# SCH__Atlas_2026-06-27.net
KiCad netlist of a schematic drawn in EasyEDA
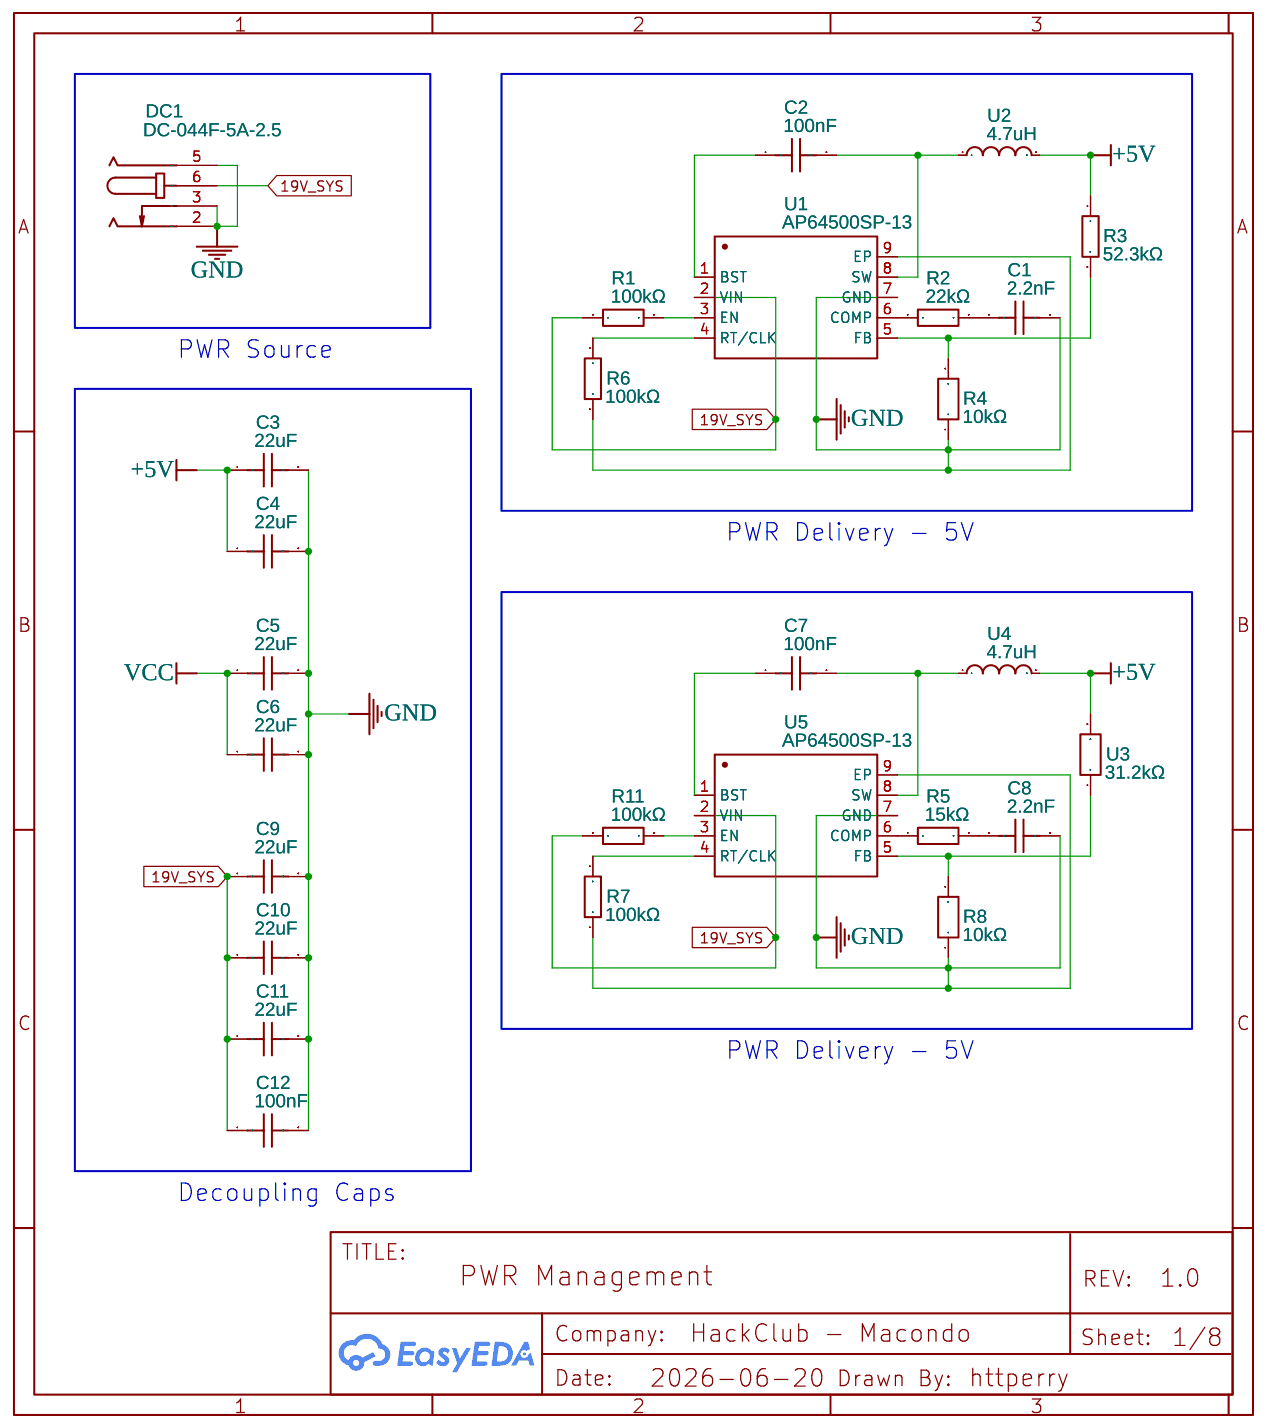
[diagram p0: PWR_Management]
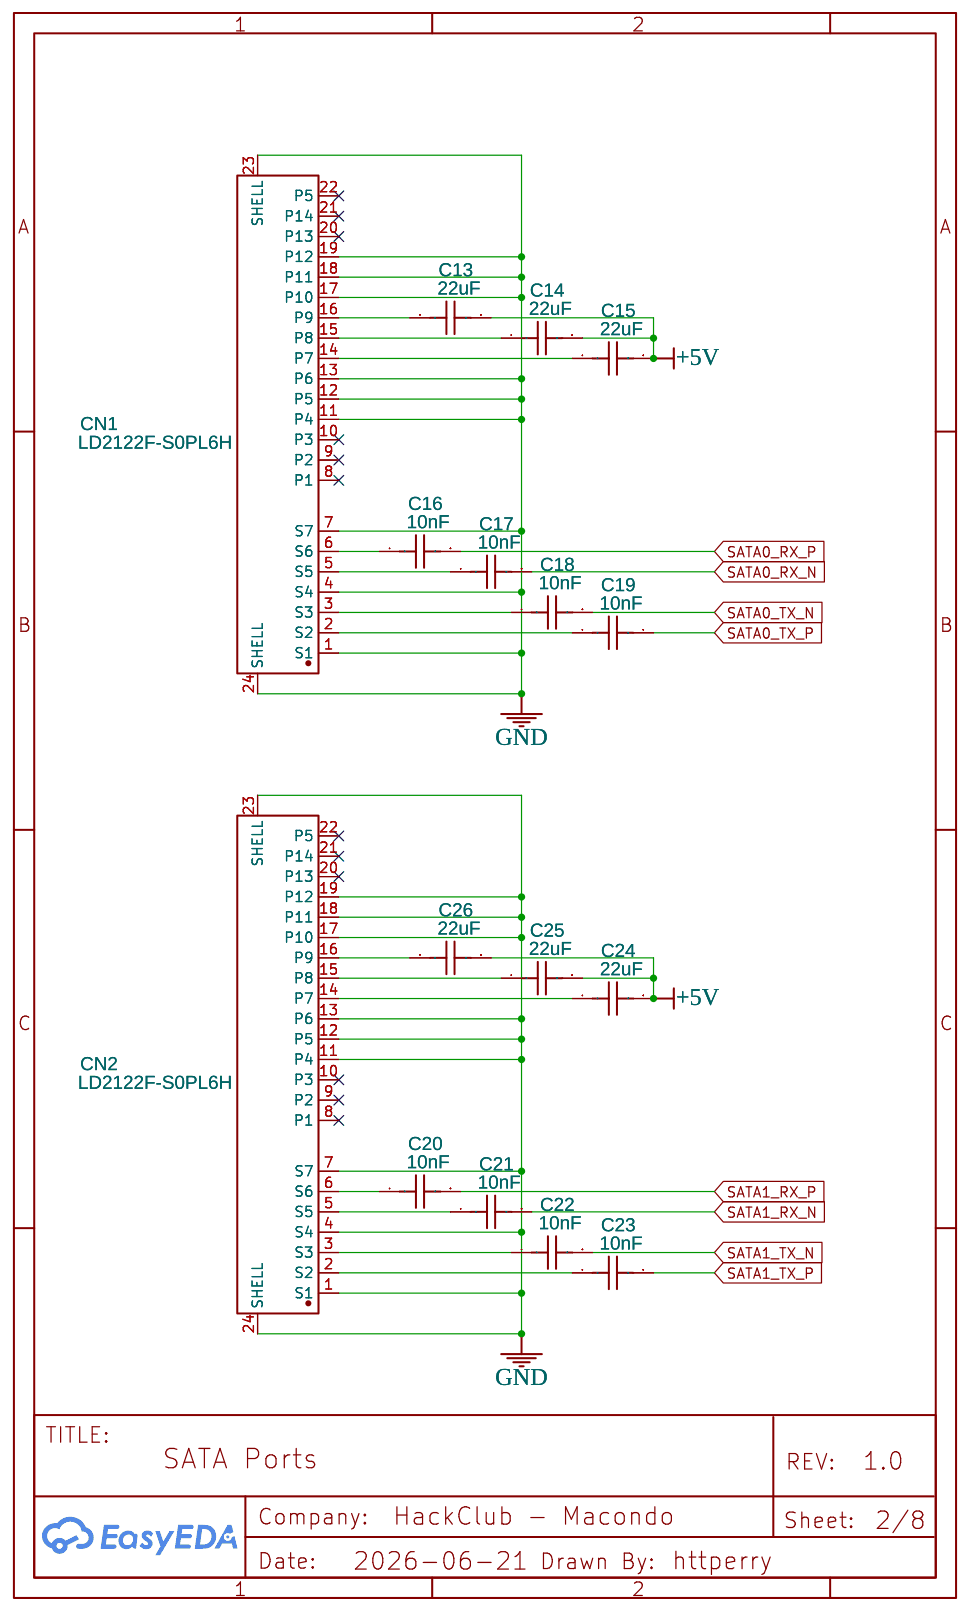
[diagram p1: SATA_Ports]
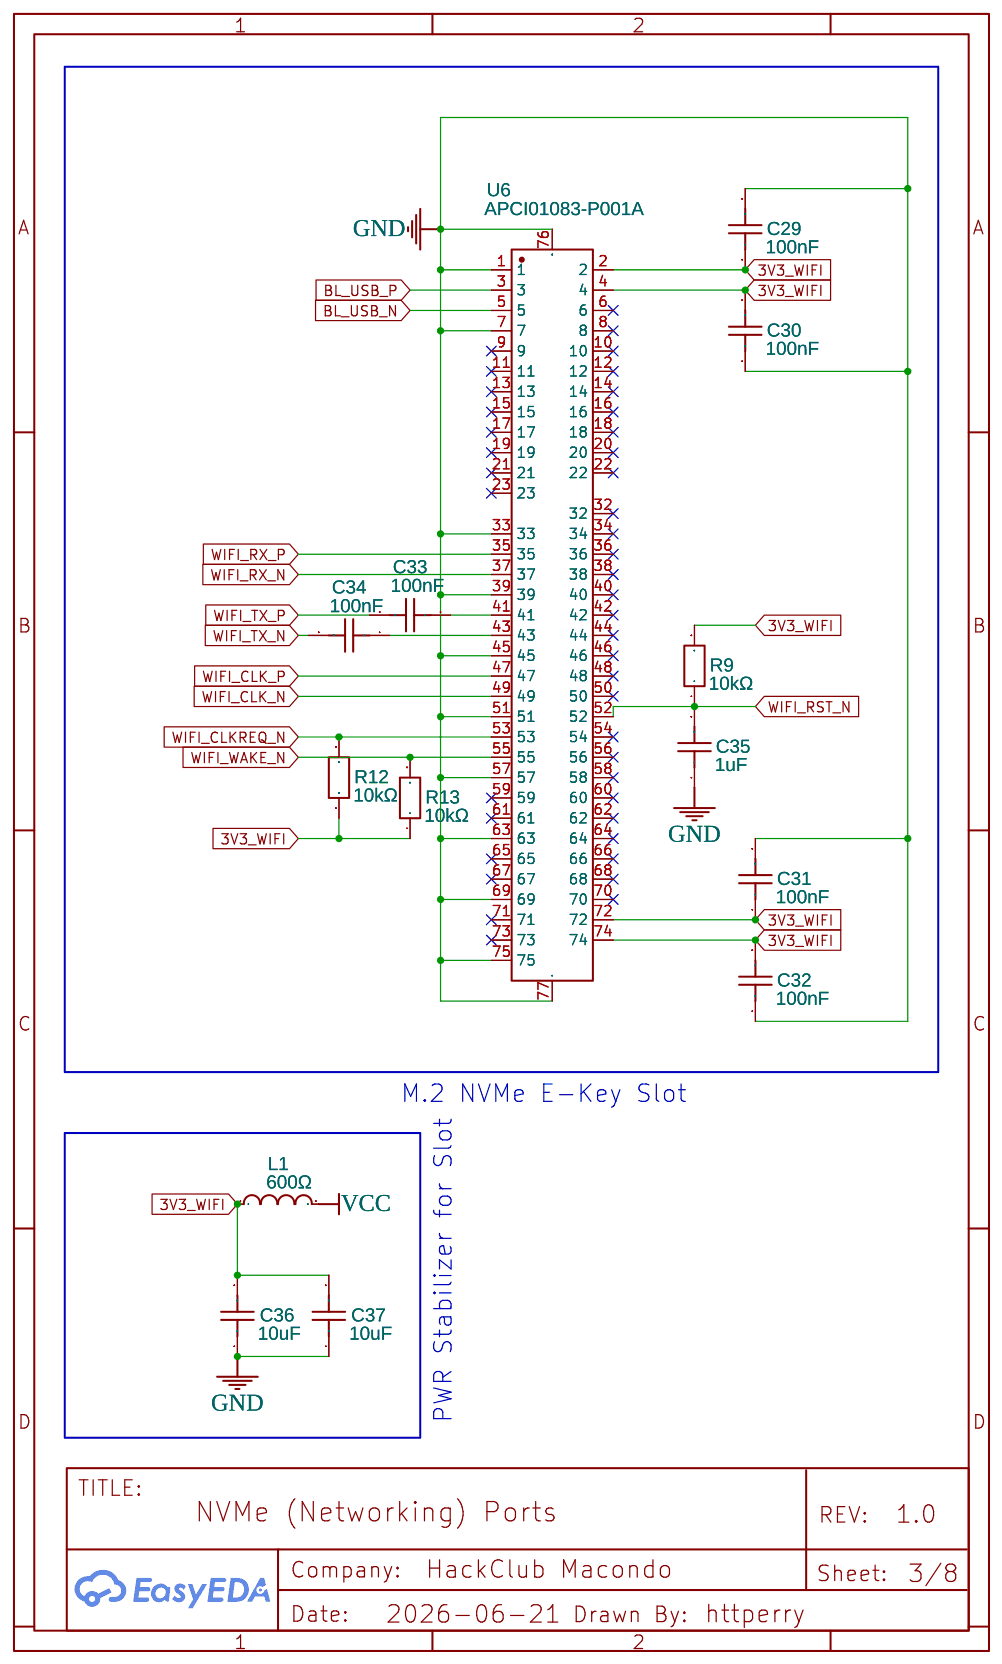
[diagram p2: NVMe_(Networking)_Ports]
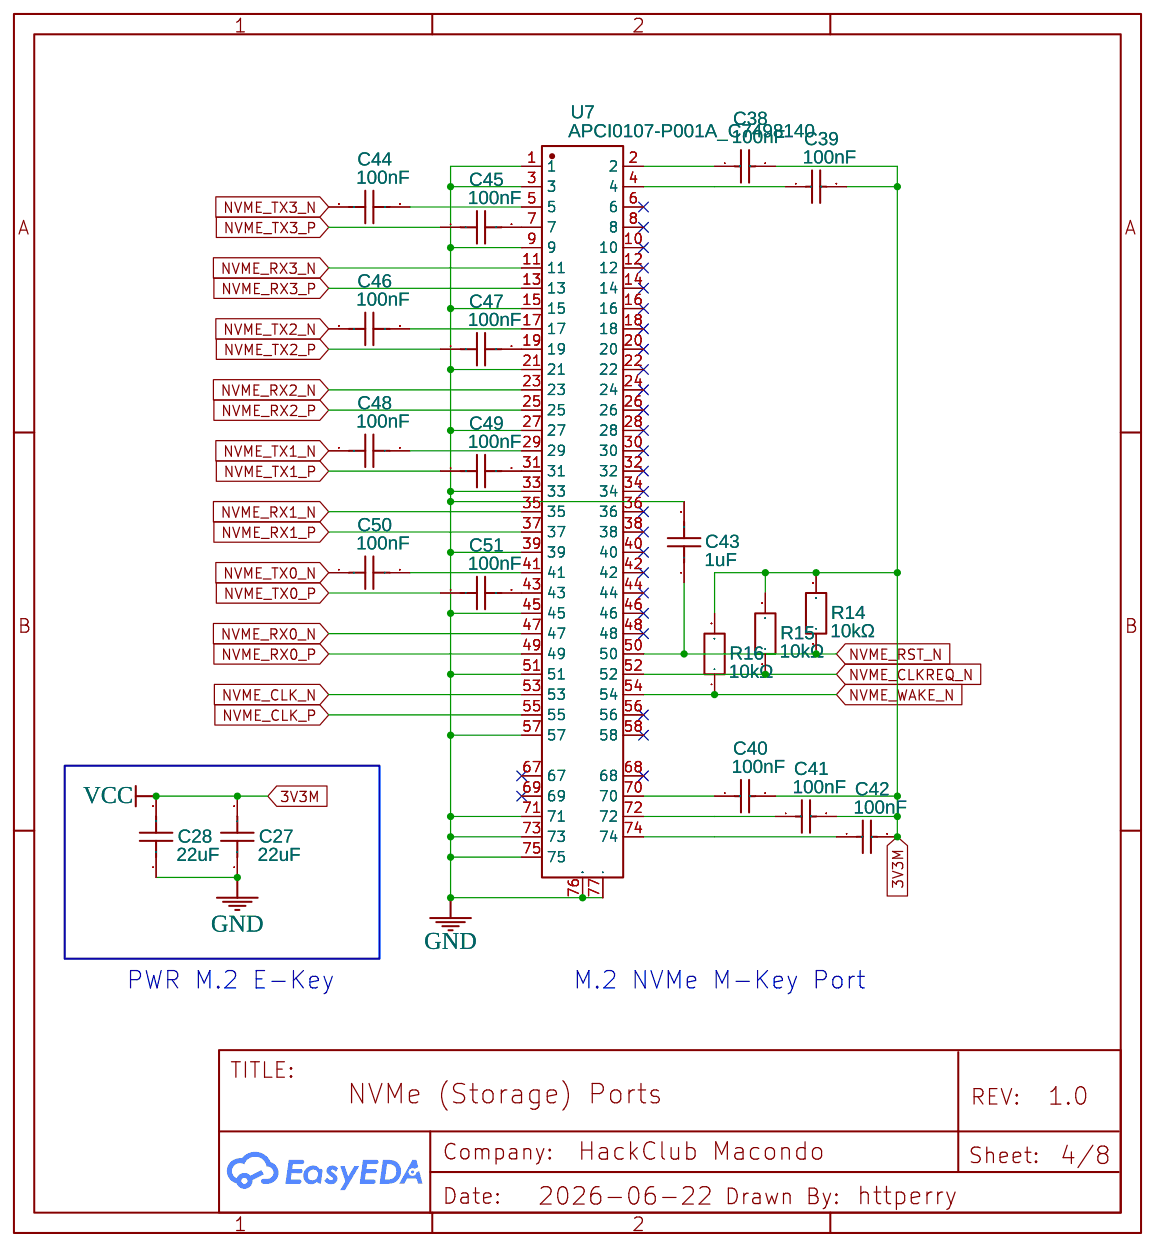
[diagram p3: NVMe_(Storage)_Ports]
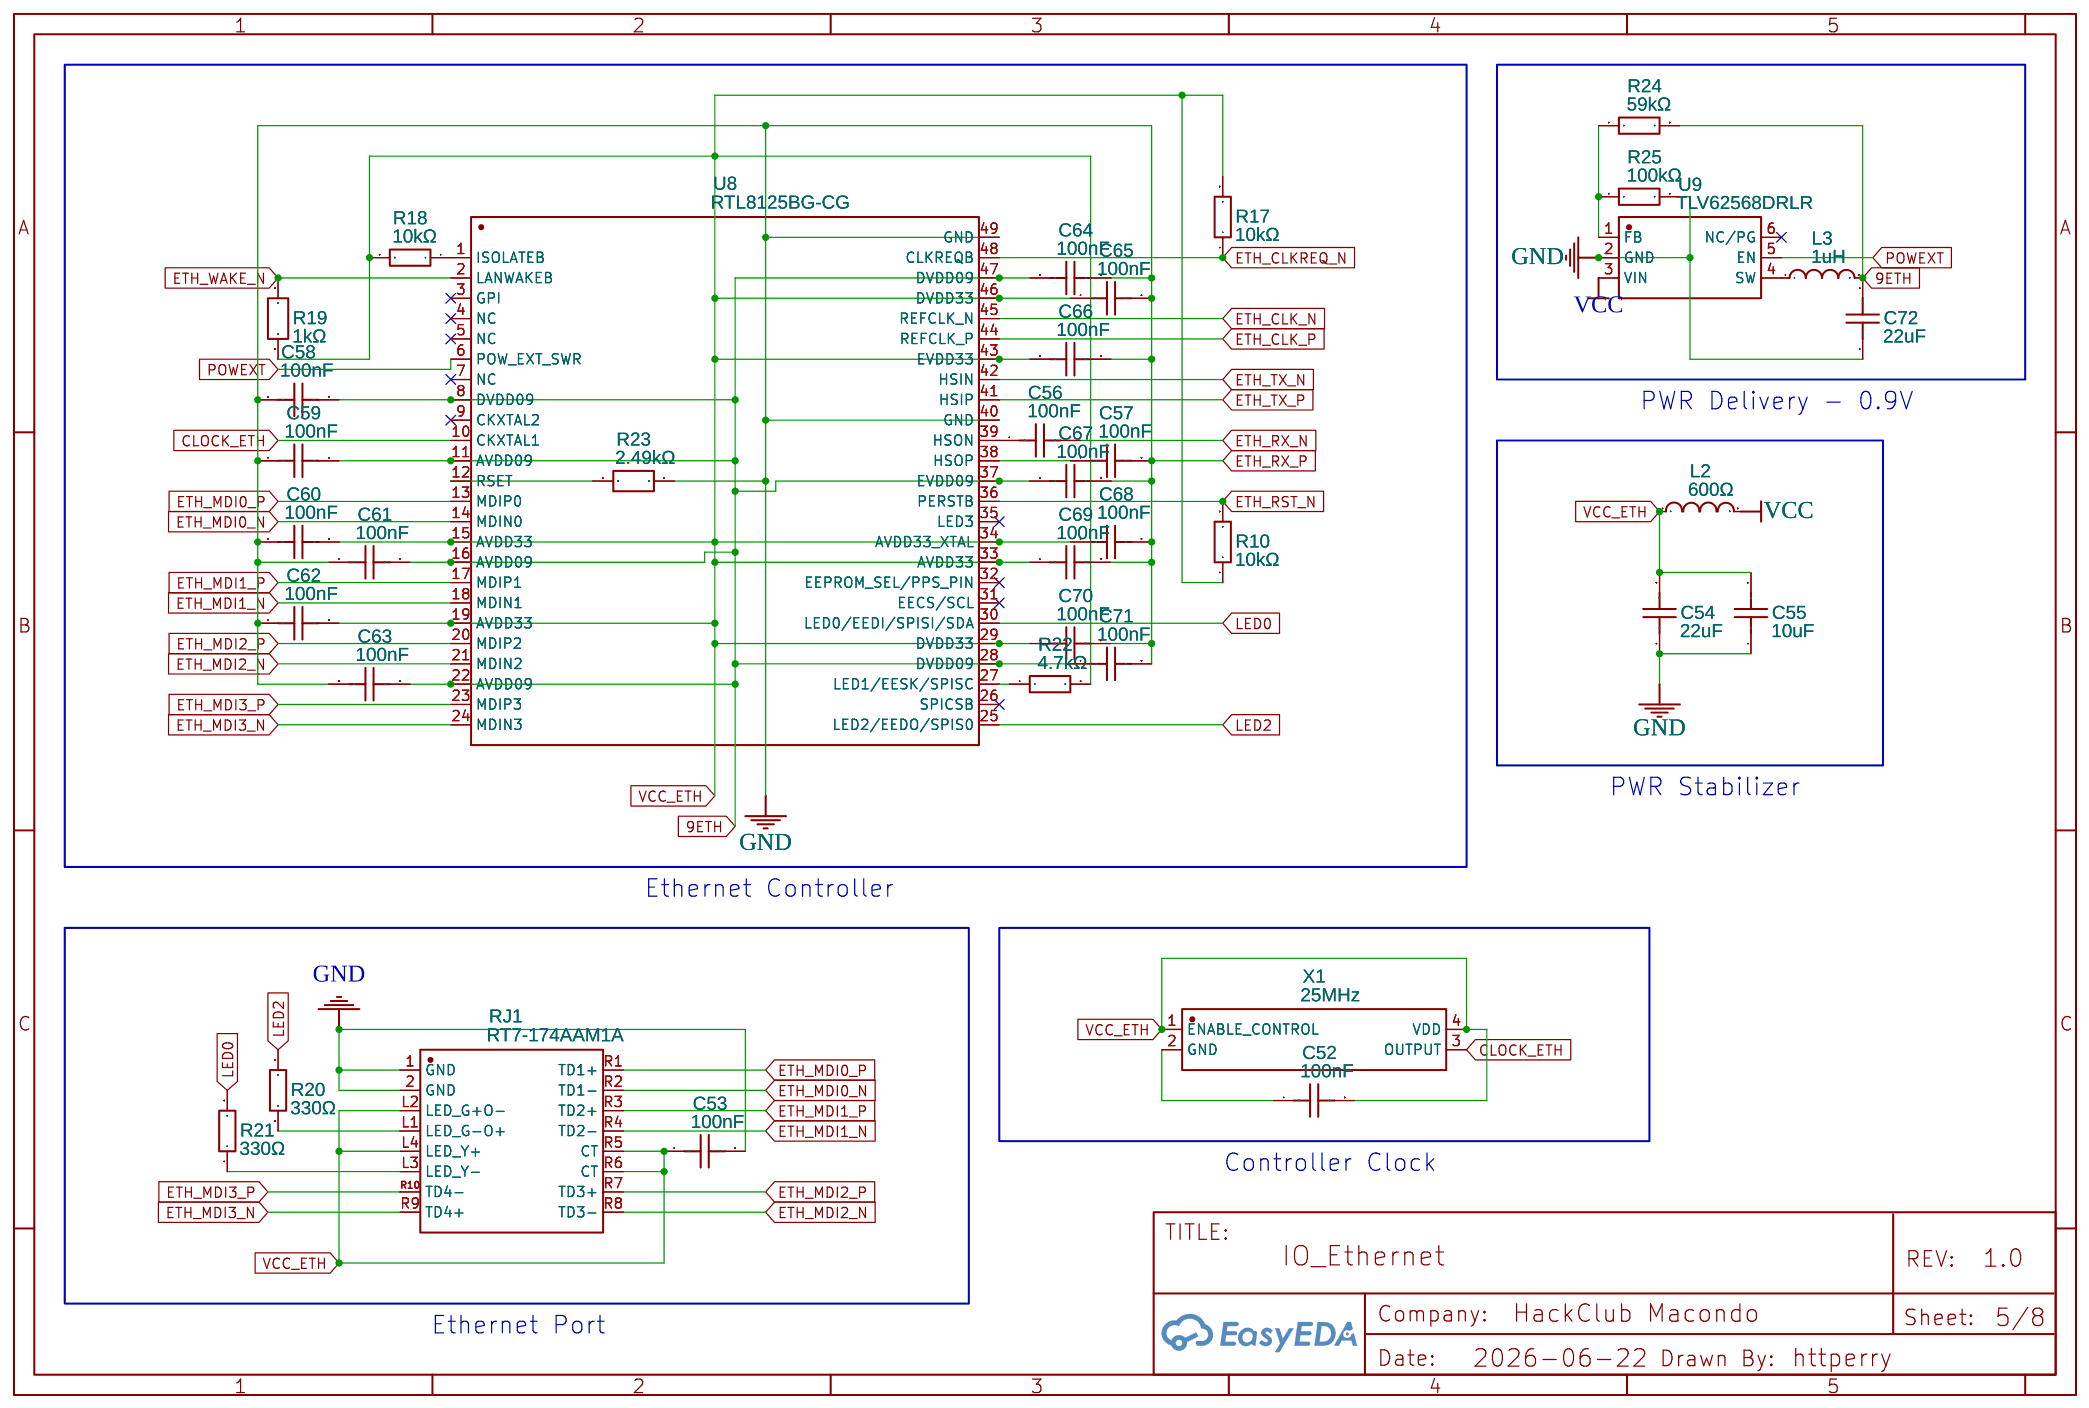
[diagram p4: IO_Ethernet]
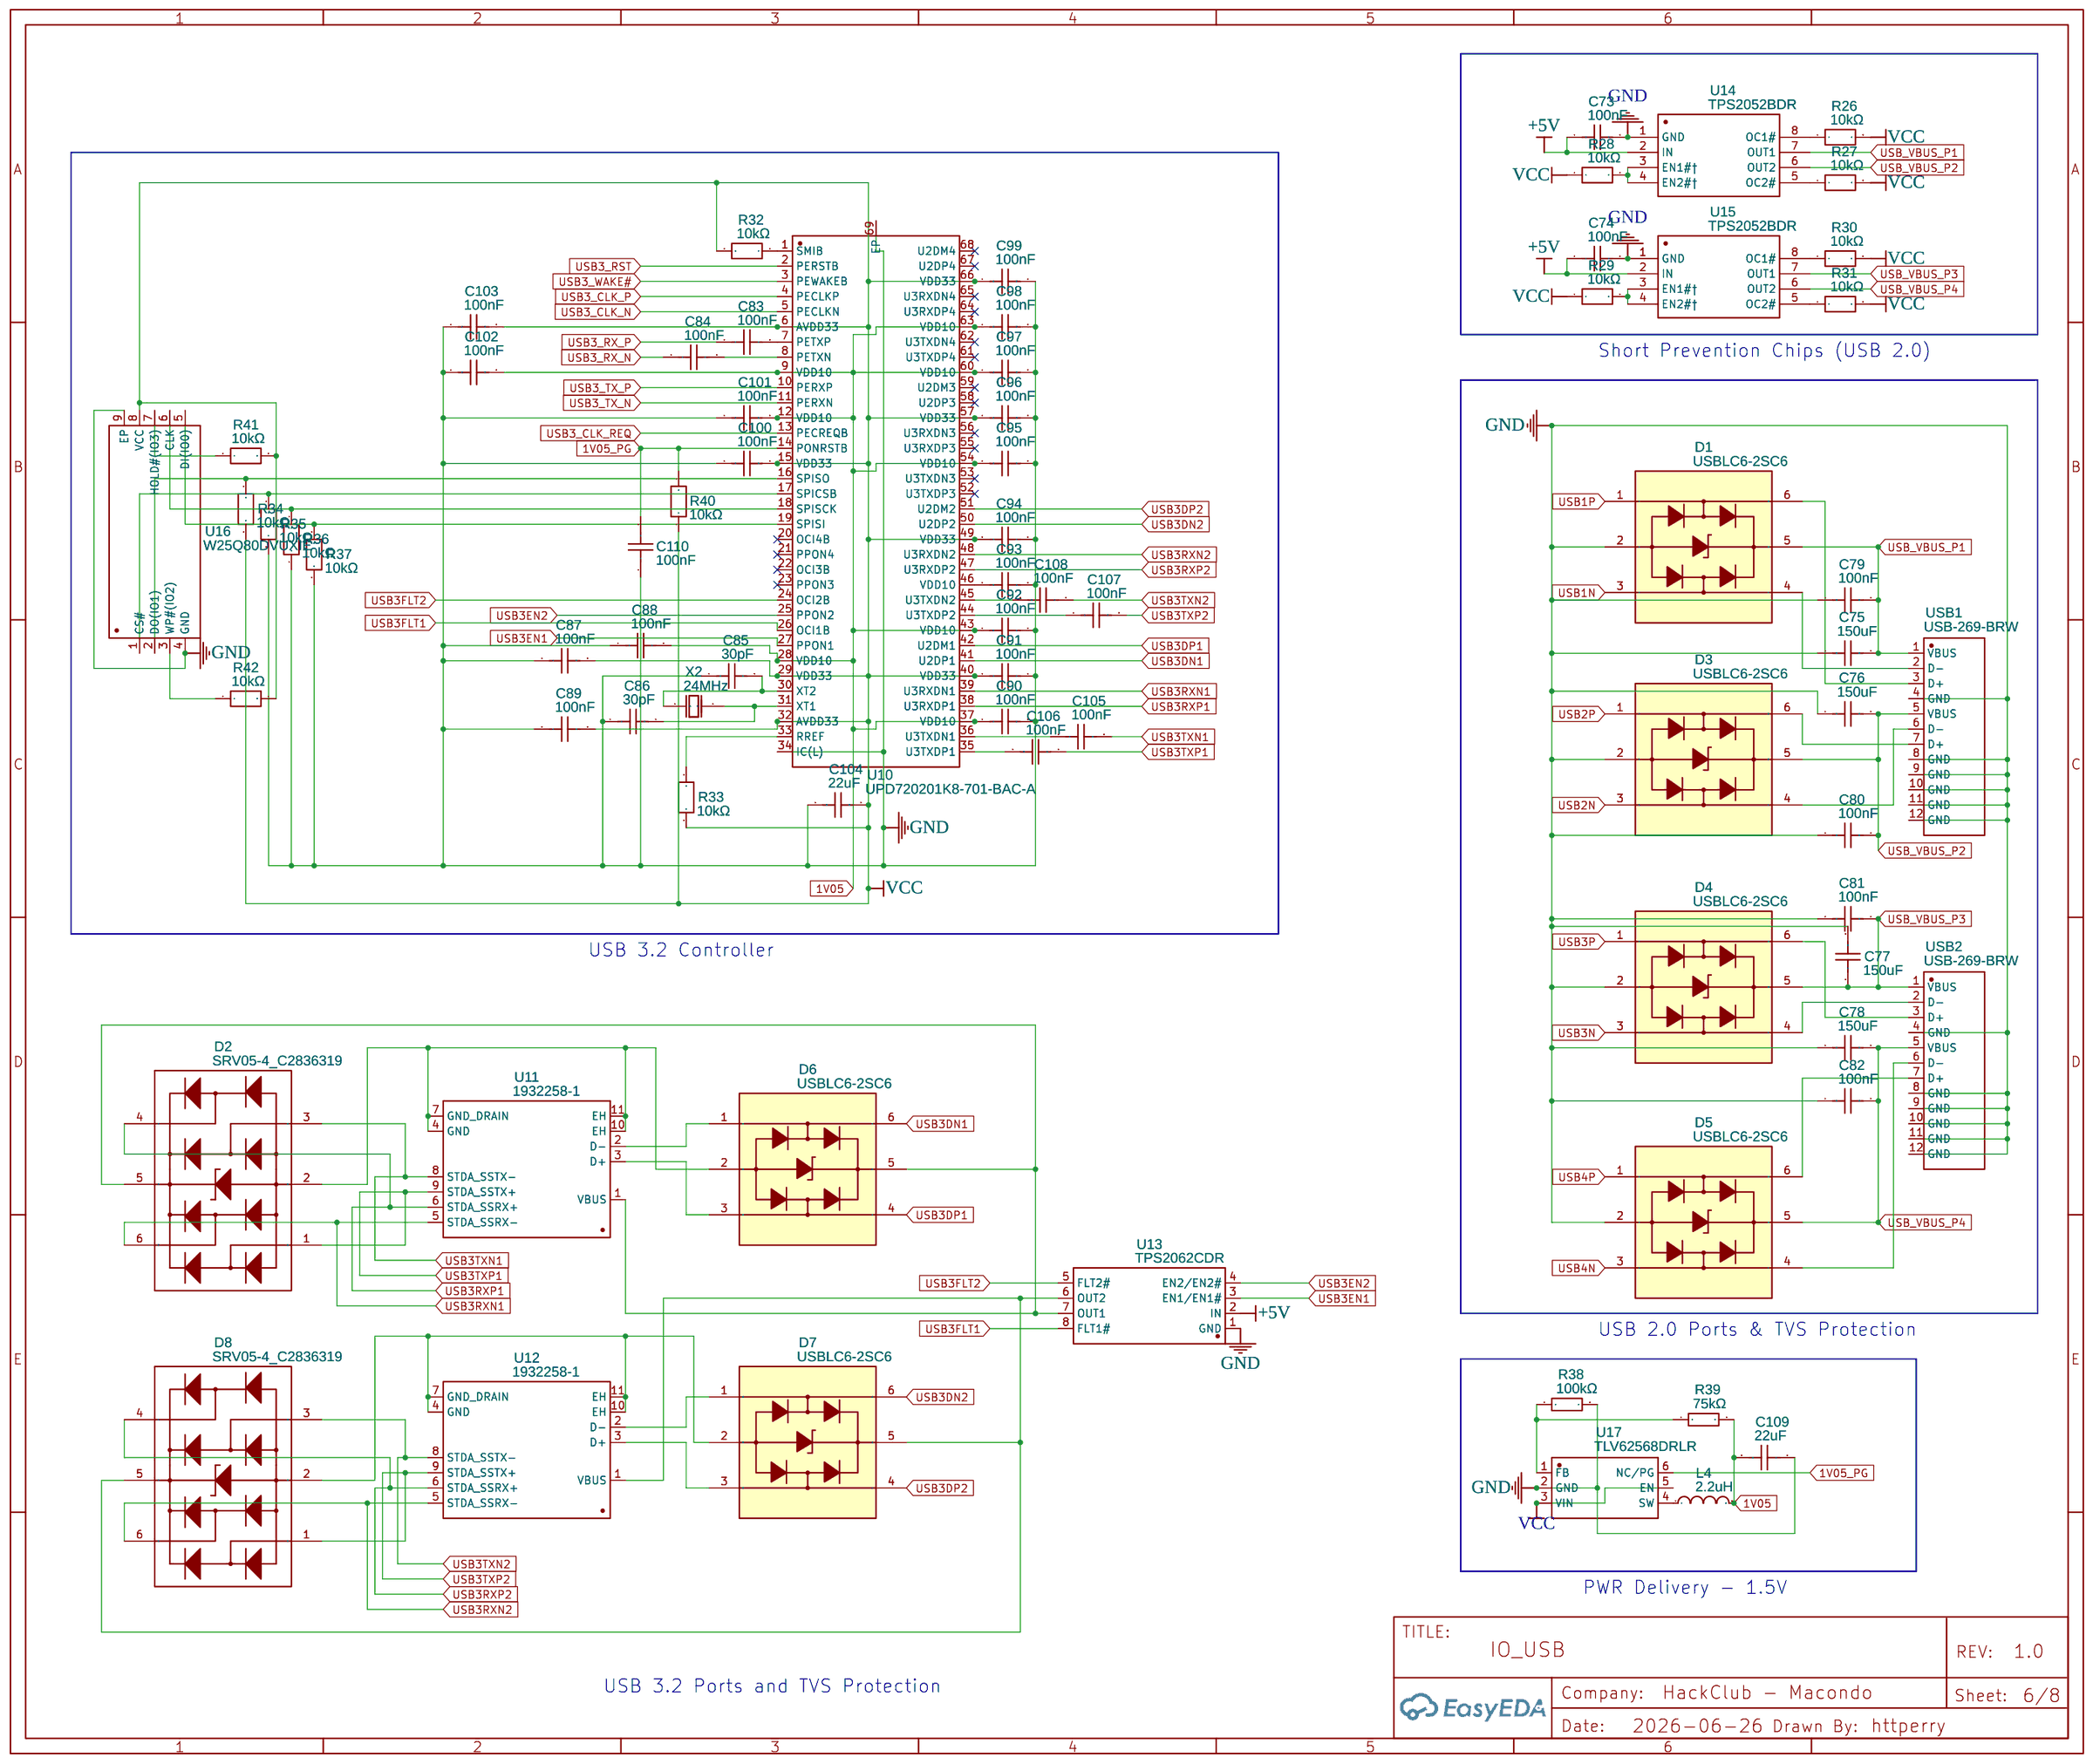
[diagram p5: IO_USB]
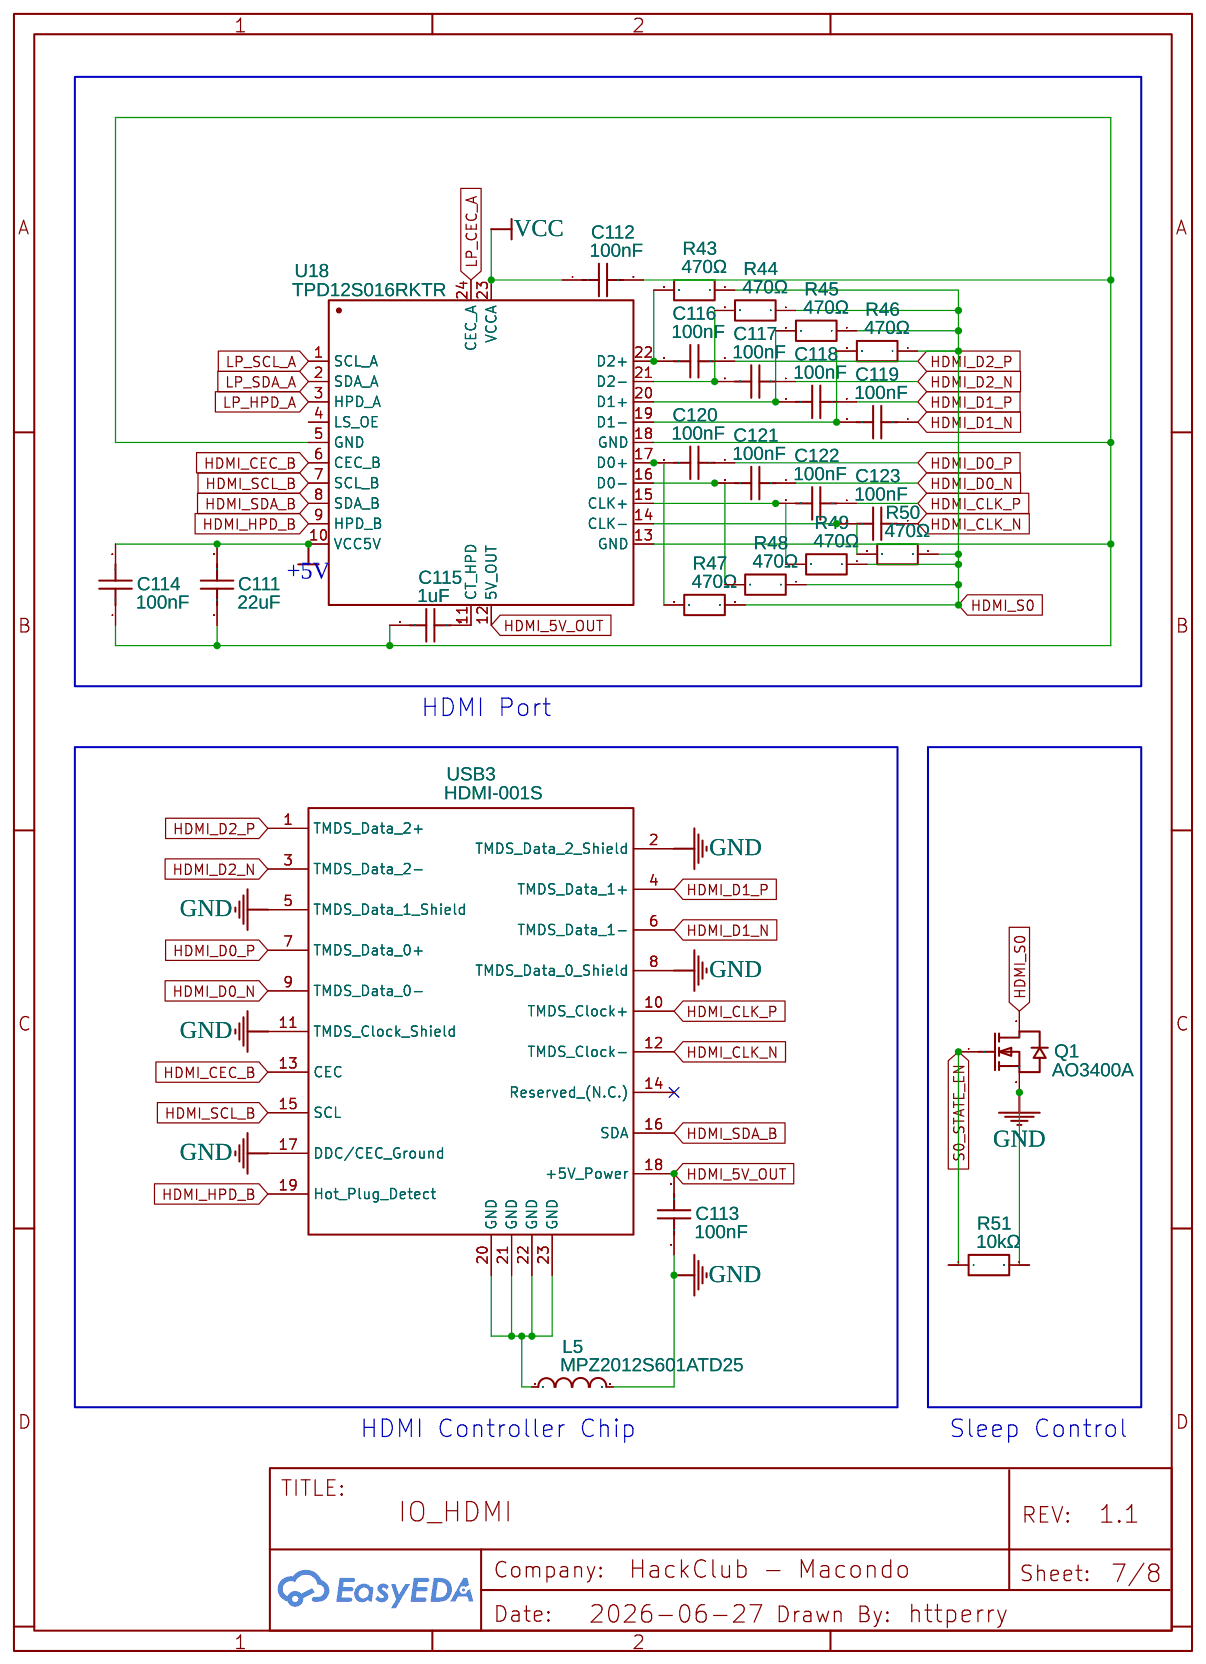
[diagram p6: IO_HDMI]
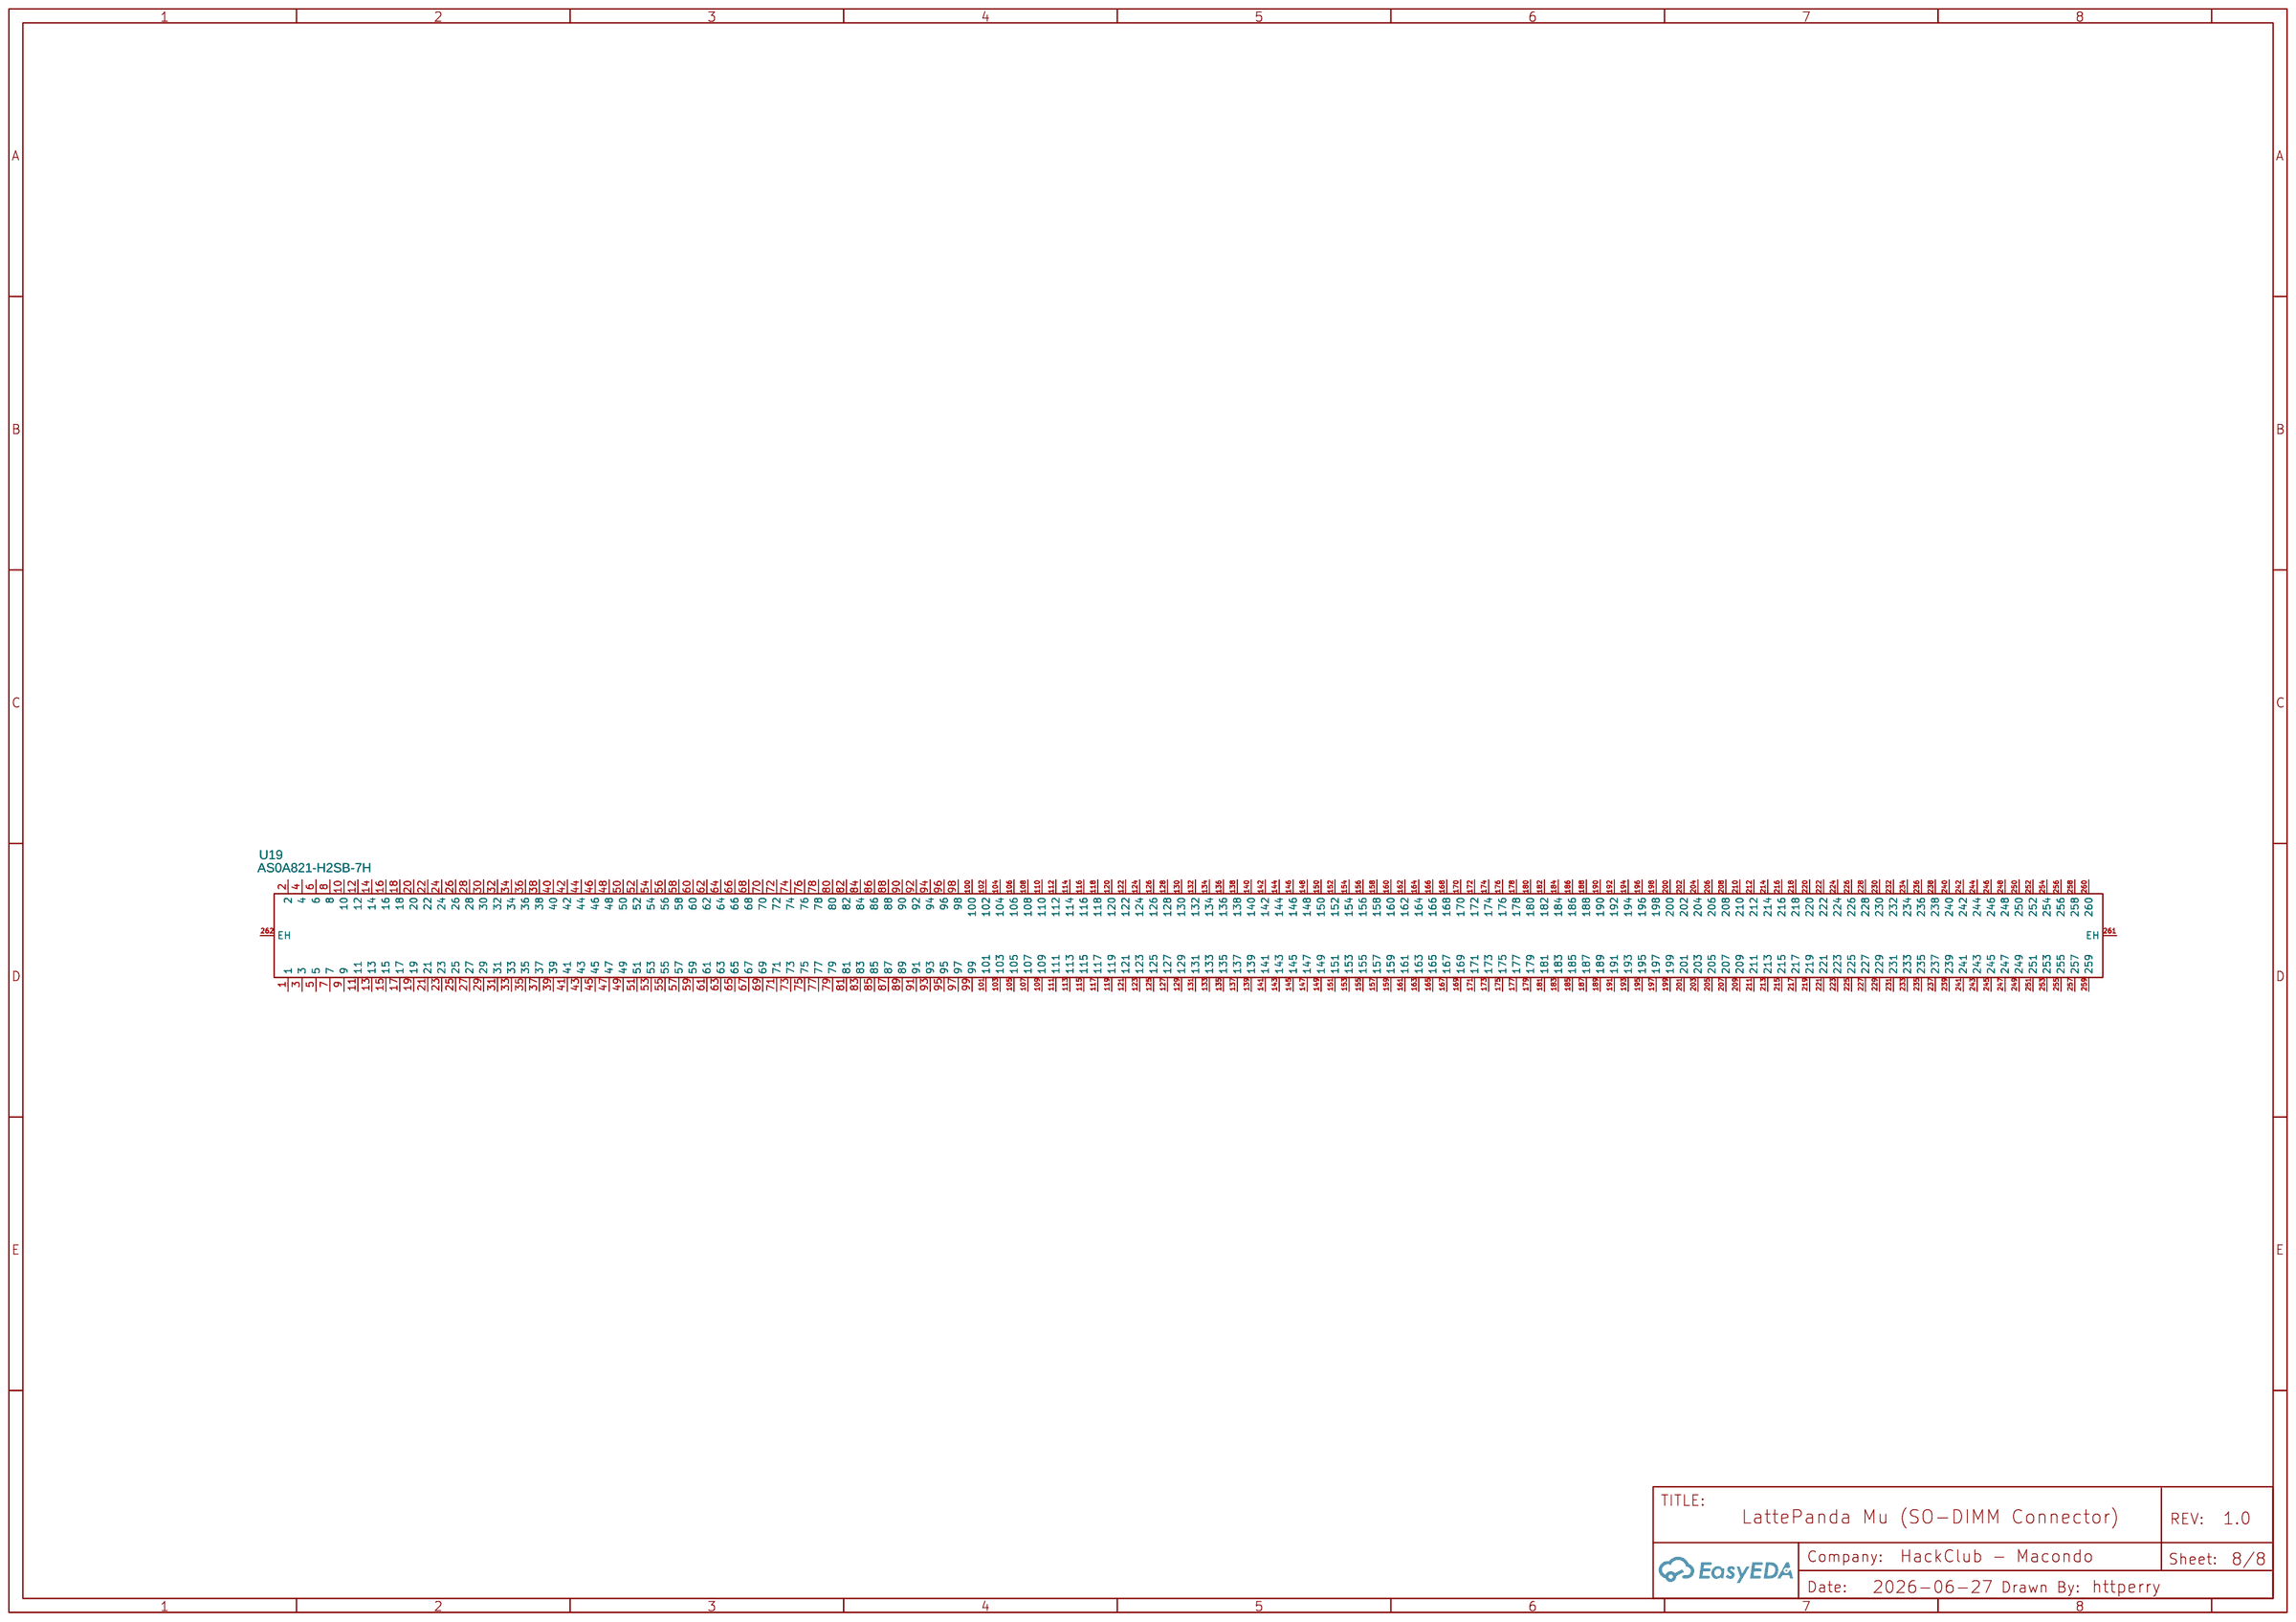
[diagram p7: SoM_SODIMM]

(export (version "E")
  (design (tool "Eeschema 10.0.6"))
  (components
    (comp (ref "C1")
      (value "2.2nF")
      (fields
        (field (name "Manufacturer Part") "FCC0603B222K500CT")
        (field (name "Manufacturer") "FOJAN(富捷)")
      )
      (libsource (lib "") (part "FCC0603B222K500CT"))
    )
    (comp (ref "C2")
      (value "100nF")
      (fields
        (field (name "Manufacturer Part") "GRM188R71H104KA93D")
        (field (name "Manufacturer") "muRata(村田)")
      )
      (libsource (lib "") (part "GRM188R71H104KA93D"))
    )
    (comp (ref "C3")
      (value "22uF")
      (fields
        (field (name "Manufacturer Part") "HGC0603R5226M160NTHJ")
        (field (name "Manufacturer") "Chinocera(华瓷)")
      )
      (libsource (lib "") (part "HGC0603R5226M160NTHJ"))
    )
    (comp (ref "C4")
      (value "22uF")
      (fields
        (field (name "Manufacturer Part") "HGC0603R5226M160NTHJ")
        (field (name "Manufacturer") "Chinocera(华瓷)")
      )
      (libsource (lib "") (part "HGC0603R5226M160NTHJ"))
    )
    (comp (ref "C5")
      (value "22uF")
      (fields
        (field (name "Manufacturer Part") "HGC0603R5226M160NTHJ")
        (field (name "Manufacturer") "Chinocera(华瓷)")
      )
      (libsource (lib "") (part "HGC0603R5226M160NTHJ"))
    )
    (comp (ref "C6")
      (value "22uF")
      (fields
        (field (name "Manufacturer Part") "HGC0603R5226M160NTHJ")
        (field (name "Manufacturer") "Chinocera(华瓷)")
      )
      (libsource (lib "") (part "HGC0603R5226M160NTHJ"))
    )
    (comp (ref "C7")
      (value "100nF")
      (fields
        (field (name "Manufacturer Part") "GRM188R71H104KA93D")
        (field (name "Manufacturer") "muRata(村田)")
      )
      (libsource (lib "") (part "GRM188R71H104KA93D"))
    )
    (comp (ref "C8")
      (value "2.2nF")
      (fields
        (field (name "Manufacturer Part") "FCC0603B222K500CT")
        (field (name "Manufacturer") "FOJAN(富捷)")
      )
      (libsource (lib "") (part "FCC0603B222K500CT"))
    )
    (comp (ref "C9")
      (value "22uF")
      (fields
        (field (name "Manufacturer Part") "KCM55QR71H226KH13K")
        (field (name "Manufacturer") "muRata(村田)")
      )
      (libsource (lib "") (part "KCM55QR71H226KH13K"))
    )
    (comp (ref "C10")
      (value "22uF")
      (fields
        (field (name "Manufacturer Part") "KCM55QR71H226KH13K")
        (field (name "Manufacturer") "muRata(村田)")
      )
      (libsource (lib "") (part "KCM55QR71H226KH13K"))
    )
    (comp (ref "C11")
      (value "22uF")
      (fields
        (field (name "Manufacturer Part") "KCM55QR71H226KH13K")
        (field (name "Manufacturer") "muRata(村田)")
      )
      (libsource (lib "") (part "KCM55QR71H226KH13K"))
    )
    (comp (ref "C12")
      (value "100nF")
      (fields
        (field (name "Manufacturer Part") "GRM188R71H104KA93D")
        (field (name "Manufacturer") "muRata(村田)")
      )
      (libsource (lib "") (part "GRM188R71H104KA93D"))
    )
    (comp (ref "DC1")
      (value "DC-044F-5A-2.5")
      (fields (field (name "Manufacturer") "XKB Connection(中国星坤)"))
      (libsource (lib "") (part "DC-044F-5A-2.5"))
    )
    (comp (ref "R1")
      (value "100kΩ")
      (fields (field (name "Manufacturer Part") "RS-03K1003FT") (field (name "Manufacturer") "FH(风华)"))
      (libsource (lib "") (part "RS-03K1003FT_C115320"))
    )
    (comp (ref "R2")
      (value "22kΩ")
      (fields (field (name "Manufacturer Part") "RS-03K2202FT") (field (name "Manufacturer") "FH(风华)"))
      (libsource (lib "") (part "RS-03K2202FT"))
    )
    (comp (ref "R3")
      (value "52.3kΩ")
      (fields (field (name "Manufacturer Part") "RS-03K5232FT") (field (name "Manufacturer") "FH(风华)"))
      (libsource (lib "") (part "RS-03K5232FT"))
    )
    (comp (ref "R4")
      (value "10kΩ")
      (fields (field (name "Manufacturer Part") "AR03BTS1002") (field (name "Manufacturer") "Viking(光颉)"))
      (libsource (lib "") (part "AR03BTS1002"))
    )
    (comp (ref "R5")
      (value "15kΩ")
      (fields (field (name "Manufacturer Part") "CR0603FA1502G") (field (name "Manufacturer") "LIZ(丽智电子)"))
      (libsource (lib "") (part "CR0603FA1502G"))
    )
    (comp (ref "R6")
      (value "100kΩ")
      (fields (field (name "Manufacturer Part") "RS-03K1003FT") (field (name "Manufacturer") "FH(风华)"))
      (libsource (lib "") (part "RS-03K1003FT_C115320_1"))
    )
    (comp (ref "R7")
      (value "100kΩ")
      (fields (field (name "Manufacturer Part") "RS-03K1003FT") (field (name "Manufacturer") "FH(风华)"))
      (libsource (lib "") (part "RS-03K1003FT_C115320_1"))
    )
    (comp (ref "R8")
      (value "10kΩ")
      (fields (field (name "Manufacturer Part") "AR03BTS1002") (field (name "Manufacturer") "Viking(光颉)"))
      (libsource (lib "") (part "AR03BTS1002"))
    )
    (comp (ref "R11")
      (value "100kΩ")
      (fields (field (name "Manufacturer Part") "RS-03K1003FT") (field (name "Manufacturer") "FH(风华)"))
      (libsource (lib "") (part "RS-03K1003FT_C115320"))
    )
    (comp (ref "U1")
      (value "AP64500SP-13")
      (fields (field (name "Manufacturer") "DIODES(美台)"))
      (libsource (lib "") (part "AP64500SP-13"))
    )
    (comp (ref "U2")
      (value "4.7uH")
      (fields (field (name "Manufacturer Part") "APH0630T4R7M") (field (name "Manufacturer") "APV(爱普微)"))
      (libsource (lib "") (part "APH0630T4R7M"))
    )
    (comp (ref "U3")
      (value "31.2kΩ")
      (fields (field (name "Manufacturer Part") "RT0603DRE0731K2L") (field (name "Manufacturer") "YAGEO(国巨)"))
      (libsource (lib "") (part "RT0603DRE0731K2L"))
    )
    (comp (ref "U4")
      (value "4.7uH")
      (fields (field (name "Manufacturer Part") "APH0630T4R7M") (field (name "Manufacturer") "APV(爱普微)"))
      (libsource (lib "") (part "APH0630T4R7M"))
    )
    (comp (ref "U5")
      (value "AP64500SP-13")
      (fields (field (name "Manufacturer") "DIODES(美台)"))
      (libsource (lib "") (part "AP64500SP-13"))
    )
    (comp (ref "C13")
      (value "22uF")
      (fields
        (field (name "Manufacturer Part") "HGC0603R5226M160NTHJ")
        (field (name "Manufacturer") "Chinocera(华瓷)")
      )
      (libsource (lib "") (part "HGC0603R5226M160NTHJ"))
    )
    (comp (ref "C14")
      (value "22uF")
      (fields
        (field (name "Manufacturer Part") "HGC0603R5226M160NTHJ")
        (field (name "Manufacturer") "Chinocera(华瓷)")
      )
      (libsource (lib "") (part "HGC0603R5226M160NTHJ"))
    )
    (comp (ref "C15")
      (value "22uF")
      (fields
        (field (name "Manufacturer Part") "HGC0603R5226M160NTHJ")
        (field (name "Manufacturer") "Chinocera(华瓷)")
      )
      (libsource (lib "") (part "HGC0603R5226M160NTHJ"))
    )
    (comp (ref "C16")
      (value "10nF")
      (fields
        (field (name "Manufacturer Part") "FCC0402B103K500AT")
        (field (name "Manufacturer") "FOJAN(富捷)")
      )
      (libsource (lib "") (part "FCC0402B103K500AT"))
    )
    (comp (ref "C17")
      (value "10nF")
      (fields
        (field (name "Manufacturer Part") "FCC0402B103K500AT")
        (field (name "Manufacturer") "FOJAN(富捷)")
      )
      (libsource (lib "") (part "FCC0402B103K500AT"))
    )
    (comp (ref "C18")
      (value "10nF")
      (fields
        (field (name "Manufacturer Part") "FCC0402B103K500AT")
        (field (name "Manufacturer") "FOJAN(富捷)")
      )
      (libsource (lib "") (part "FCC0402B103K500AT"))
    )
    (comp (ref "C19")
      (value "10nF")
      (fields
        (field (name "Manufacturer Part") "FCC0402B103K500AT")
        (field (name "Manufacturer") "FOJAN(富捷)")
      )
      (libsource (lib "") (part "FCC0402B103K500AT"))
    )
    (comp (ref "C20")
      (value "10nF")
      (fields
        (field (name "Manufacturer Part") "FCC0402B103K500AT")
        (field (name "Manufacturer") "FOJAN(富捷)")
      )
      (libsource (lib "") (part "FCC0402B103K500AT"))
    )
    (comp (ref "C21")
      (value "10nF")
      (fields
        (field (name "Manufacturer Part") "FCC0402B103K500AT")
        (field (name "Manufacturer") "FOJAN(富捷)")
      )
      (libsource (lib "") (part "FCC0402B103K500AT"))
    )
    (comp (ref "C22")
      (value "10nF")
      (fields
        (field (name "Manufacturer Part") "FCC0402B103K500AT")
        (field (name "Manufacturer") "FOJAN(富捷)")
      )
      (libsource (lib "") (part "FCC0402B103K500AT"))
    )
    (comp (ref "C23")
      (value "10nF")
      (fields
        (field (name "Manufacturer Part") "FCC0402B103K500AT")
        (field (name "Manufacturer") "FOJAN(富捷)")
      )
      (libsource (lib "") (part "FCC0402B103K500AT"))
    )
    (comp (ref "C24")
      (value "22uF")
      (fields
        (field (name "Manufacturer Part") "HGC0603R5226M160NTHJ")
        (field (name "Manufacturer") "Chinocera(华瓷)")
      )
      (libsource (lib "") (part "HGC0603R5226M160NTHJ"))
    )
    (comp (ref "C25")
      (value "22uF")
      (fields
        (field (name "Manufacturer Part") "HGC0603R5226M160NTHJ")
        (field (name "Manufacturer") "Chinocera(华瓷)")
      )
      (libsource (lib "") (part "HGC0603R5226M160NTHJ"))
    )
    (comp (ref "C26")
      (value "22uF")
      (fields
        (field (name "Manufacturer Part") "HGC0603R5226M160NTHJ")
        (field (name "Manufacturer") "Chinocera(华瓷)")
      )
      (libsource (lib "") (part "HGC0603R5226M160NTHJ"))
    )
    (comp (ref "CN1")
      (value "LD2122F-S0PL6H")
      (fields (field (name "Manufacturer") "FOXCONN(富士康)"))
      (libsource (lib "") (part "LD2122F-S0PL6H"))
    )
    (comp (ref "CN2")
      (value "LD2122F-S0PL6H")
      (fields (field (name "Manufacturer") "FOXCONN(富士康)"))
      (libsource (lib "") (part "LD2122F-S0PL6H"))
    )
    (comp (ref "C29")
      (value "100nF")
      (fields
        (field (name "Manufacturer Part") "CC0402KRX5R6BB104")
        (field (name "Manufacturer") "YAGEO(国巨)")
      )
      (libsource (lib "") (part "CC0402KRX5R6BB104"))
    )
    (comp (ref "C30")
      (value "100nF")
      (fields
        (field (name "Manufacturer Part") "CC0402KRX5R6BB104")
        (field (name "Manufacturer") "YAGEO(国巨)")
      )
      (libsource (lib "") (part "CC0402KRX5R6BB104"))
    )
    (comp (ref "C31")
      (value "100nF")
      (fields
        (field (name "Manufacturer Part") "CC0402KRX5R6BB104")
        (field (name "Manufacturer") "YAGEO(国巨)")
      )
      (libsource (lib "") (part "CC0402KRX5R6BB104"))
    )
    (comp (ref "C32")
      (value "100nF")
      (fields
        (field (name "Manufacturer Part") "CC0402KRX5R6BB104")
        (field (name "Manufacturer") "YAGEO(国巨)")
      )
      (libsource (lib "") (part "CC0402KRX5R6BB104"))
    )
    (comp (ref "C33")
      (value "100nF")
      (fields
        (field (name "Manufacturer Part") "CC0402KRX5R6BB104")
        (field (name "Manufacturer") "YAGEO(国巨)")
      )
      (libsource (lib "") (part "CC0402KRX5R6BB104_1"))
    )
    (comp (ref "C34")
      (value "100nF")
      (fields
        (field (name "Manufacturer Part") "CC0402KRX5R6BB104")
        (field (name "Manufacturer") "YAGEO(国巨)")
      )
      (libsource (lib "") (part "CC0402KRX5R6BB104_1"))
    )
    (comp (ref "C35")
      (value "1uF")
      (fields
        (field (name "Manufacturer Part") "TCC0402X5R105K160AT")
        (field (name "Manufacturer") "CCTC(三环)")
      )
      (libsource (lib "") (part "TCC0402X5R105K160AT"))
    )
    (comp (ref "C36")
      (value "10uF")
      (fields
        (field (name "Manufacturer Part") "CGA0805X5R106K500MT")
        (field (name "Manufacturer") "HRE(芯声)")
      )
      (libsource (lib "") (part "CGA0805X5R106K500MT"))
    )
    (comp (ref "C37")
      (value "10uF")
      (fields
        (field (name "Manufacturer Part") "CGA0805X5R106K500MT")
        (field (name "Manufacturer") "HRE(芯声)")
      )
      (libsource (lib "") (part "CGA0805X5R106K500MT"))
    )
    (comp (ref "L1")
      (value "600Ω")
      (fields (field (name "Manufacturer Part") "MPZ2012S601AT000") (field (name "Manufacturer") "TDK"))
      (libsource (lib "") (part "MPZ2012S601AT000"))
    )
    (comp (ref "R9")
      (value "10kΩ")
      (fields (field (name "Manufacturer Part") "FRC0402F1002TS") (field (name "Manufacturer") "FOJAN(富捷)"))
      (libsource (lib "") (part "FRC0402F1002TS"))
    )
    (comp (ref "R12")
      (value "10kΩ")
      (fields (field (name "Manufacturer Part") "FRC0402F1002TS") (field (name "Manufacturer") "FOJAN(富捷)"))
      (libsource (lib "") (part "FRC0402F1002TS"))
    )
    (comp (ref "R13")
      (value "10kΩ")
      (fields (field (name "Manufacturer Part") "FRC0402F1002TS") (field (name "Manufacturer") "FOJAN(富捷)"))
      (libsource (lib "") (part "FRC0402F1002TS"))
    )
    (comp (ref "U6")
      (value "APCI01083-P001A")
      (fields (field (name "Manufacturer") "LX(连欣科技)"))
      (libsource (lib "") (part "APCI01083-P001A"))
    )
    (comp (ref "C27")
      (value "22uF")
      (fields
        (field (name "Manufacturer Part") "CL21A226MAYNNNE")
        (field (name "Manufacturer") "SAMSUNG(三星)")
      )
      (libsource (lib "") (part "CL21A226MAYNNNE"))
    )
    (comp (ref "C28")
      (value "22uF")
      (fields
        (field (name "Manufacturer Part") "CL21A226MAYNNNE")
        (field (name "Manufacturer") "SAMSUNG(三星)")
      )
      (libsource (lib "") (part "CL21A226MAYNNNE"))
    )
    (comp (ref "C38")
      (value "100nF")
      (fields
        (field (name "Manufacturer Part") "CC0402KRX5R8BB104")
        (field (name "Manufacturer") "YAGEO(国巨)")
      )
      (libsource (lib "") (part "CC0402KRX5R8BB104"))
    )
    (comp (ref "C39")
      (value "100nF")
      (fields
        (field (name "Manufacturer Part") "CC0402KRX5R8BB104")
        (field (name "Manufacturer") "YAGEO(国巨)")
      )
      (libsource (lib "") (part "CC0402KRX5R8BB104"))
    )
    (comp (ref "C40")
      (value "100nF")
      (fields
        (field (name "Manufacturer Part") "CC0402KRX5R8BB104")
        (field (name "Manufacturer") "YAGEO(国巨)")
      )
      (libsource (lib "") (part "CC0402KRX5R8BB104"))
    )
    (comp (ref "C41")
      (value "100nF")
      (fields
        (field (name "Manufacturer Part") "CC0402KRX5R8BB104")
        (field (name "Manufacturer") "YAGEO(国巨)")
      )
      (libsource (lib "") (part "CC0402KRX5R8BB104"))
    )
    (comp (ref "C42")
      (value "100nF")
      (fields
        (field (name "Manufacturer Part") "CC0402KRX5R8BB104")
        (field (name "Manufacturer") "YAGEO(国巨)")
      )
      (libsource (lib "") (part "CC0402KRX5R8BB104"))
    )
    (comp (ref "C43")
      (value "1uF")
      (fields
        (field (name "Manufacturer Part") "HGC0402R5105K500NTEJ")
        (field (name "Manufacturer") "Chinocera(华瓷)")
      )
      (libsource (lib "") (part "HGC0402R5105K500NTEJ"))
    )
    (comp (ref "C44")
      (value "100nF")
      (fields
        (field (name "Manufacturer Part") "GRM155R71H104KE14J")
        (field (name "Manufacturer") "muRata(村田)")
      )
      (libsource (lib "") (part "GRM155R71H104KE14J"))
    )
    (comp (ref "C45")
      (value "100nF")
      (fields
        (field (name "Manufacturer Part") "GRM155R71H104KE14J")
        (field (name "Manufacturer") "muRata(村田)")
      )
      (libsource (lib "") (part "GRM155R71H104KE14J"))
    )
    (comp (ref "C46")
      (value "100nF")
      (fields
        (field (name "Manufacturer Part") "GRM155R71H104KE14J")
        (field (name "Manufacturer") "muRata(村田)")
      )
      (libsource (lib "") (part "GRM155R71H104KE14J"))
    )
    (comp (ref "C47")
      (value "100nF")
      (fields
        (field (name "Manufacturer Part") "GRM155R71H104KE14J")
        (field (name "Manufacturer") "muRata(村田)")
      )
      (libsource (lib "") (part "GRM155R71H104KE14J"))
    )
    (comp (ref "C48")
      (value "100nF")
      (fields
        (field (name "Manufacturer Part") "GRM155R71H104KE14J")
        (field (name "Manufacturer") "muRata(村田)")
      )
      (libsource (lib "") (part "GRM155R71H104KE14J"))
    )
    (comp (ref "C49")
      (value "100nF")
      (fields
        (field (name "Manufacturer Part") "GRM155R71H104KE14J")
        (field (name "Manufacturer") "muRata(村田)")
      )
      (libsource (lib "") (part "GRM155R71H104KE14J"))
    )
    (comp (ref "C50")
      (value "100nF")
      (fields
        (field (name "Manufacturer Part") "GRM155R71H104KE14J")
        (field (name "Manufacturer") "muRata(村田)")
      )
      (libsource (lib "") (part "GRM155R71H104KE14J"))
    )
    (comp (ref "C51")
      (value "100nF")
      (fields
        (field (name "Manufacturer Part") "GRM155R71H104KE14J")
        (field (name "Manufacturer") "muRata(村田)")
      )
      (libsource (lib "") (part "GRM155R71H104KE14J"))
    )
    (comp (ref "R14")
      (value "10kΩ")
      (fields (field (name "Manufacturer Part") "FRC0402F1002TS") (field (name "Manufacturer") "FOJAN(富捷)"))
      (libsource (lib "") (part "FRC0402F1002TS"))
    )
    (comp (ref "R15")
      (value "10kΩ")
      (fields (field (name "Manufacturer Part") "FRC0402F1002TS") (field (name "Manufacturer") "FOJAN(富捷)"))
      (libsource (lib "") (part "FRC0402F1002TS"))
    )
    (comp (ref "R16")
      (value "10kΩ")
      (fields (field (name "Manufacturer Part") "FRC0402F1002TS") (field (name "Manufacturer") "FOJAN(富捷)"))
      (libsource (lib "") (part "FRC0402F1002TS"))
    )
    (comp (ref "U7")
      (value "APCI0107-P001A_C7498140")
      (fields (field (name "Manufacturer Part") "APCI0107-P001A") (field (name "Manufacturer") "LX(连欣科技)"))
      (libsource (lib "") (part "APCI0107-P001A_C7498140"))
    )
    (comp (ref "C52")
      (value "100nF")
      (fields
        (field (name "Manufacturer Part") "GRM155R71H104KE14J")
        (field (name "Manufacturer") "muRata(村田)")
      )
      (libsource (lib "") (part "GRM155R71H104KE14J"))
    )
    (comp (ref "C53")
      (value "100nF")
      (fields
        (field (name "Manufacturer Part") "GRM155R71H104KE14J")
        (field (name "Manufacturer") "muRata(村田)")
      )
      (libsource (lib "") (part "GRM155R71H104KE14J"))
    )
    (comp (ref "C54")
      (value "22uF")
      (fields
        (field (name "Manufacturer Part") "GRT21BR61E226ME13L")
        (field (name "Manufacturer") "muRata(村田)")
      )
      (libsource (lib "") (part "GRT21BR61E226ME13L"))
    )
    (comp (ref "C55")
      (value "10uF")
      (fields
        (field (name "Manufacturer Part") "TCC0805X5R106K250FT")
        (field (name "Manufacturer") "CCTC(三环)")
      )
      (libsource (lib "") (part "TCC0805X5R106K250FT"))
    )
    (comp (ref "C56")
      (value "100nF")
      (fields
        (field (name "Manufacturer Part") "GRM155R71H104KE14J")
        (field (name "Manufacturer") "muRata(村田)")
      )
      (libsource (lib "") (part "GRM155R71H104KE14J"))
    )
    (comp (ref "C57")
      (value "100nF")
      (fields
        (field (name "Manufacturer Part") "GRM155R71H104KE14J")
        (field (name "Manufacturer") "muRata(村田)")
      )
      (libsource (lib "") (part "GRM155R71H104KE14J"))
    )
    (comp (ref "C58")
      (value "100nF")
      (fields
        (field (name "Manufacturer Part") "GRM155R71H104KE14J")
        (field (name "Manufacturer") "muRata(村田)")
      )
      (libsource (lib "") (part "GRM155R71H104KE14J_1"))
    )
    (comp (ref "C59")
      (value "100nF")
      (fields
        (field (name "Manufacturer Part") "GRM155R71H104KE14J")
        (field (name "Manufacturer") "muRata(村田)")
      )
      (libsource (lib "") (part "GRM155R71H104KE14J"))
    )
    (comp (ref "C60")
      (value "100nF")
      (fields
        (field (name "Manufacturer Part") "GRM155R71H104KE14J")
        (field (name "Manufacturer") "muRata(村田)")
      )
      (libsource (lib "") (part "GRM155R71H104KE14J"))
    )
    (comp (ref "C61")
      (value "100nF")
      (fields
        (field (name "Manufacturer Part") "GRM155R71H104KE14J")
        (field (name "Manufacturer") "muRata(村田)")
      )
      (libsource (lib "") (part "GRM155R71H104KE14J"))
    )
    (comp (ref "C62")
      (value "100nF")
      (fields
        (field (name "Manufacturer Part") "GRM155R71H104KE14J")
        (field (name "Manufacturer") "muRata(村田)")
      )
      (libsource (lib "") (part "GRM155R71H104KE14J"))
    )
    (comp (ref "C63")
      (value "100nF")
      (fields
        (field (name "Manufacturer Part") "GRM155R71H104KE14J")
        (field (name "Manufacturer") "muRata(村田)")
      )
      (libsource (lib "") (part "GRM155R71H104KE14J"))
    )
    (comp (ref "C64")
      (value "100nF")
      (fields
        (field (name "Manufacturer Part") "GRM155R71H104KE14J")
        (field (name "Manufacturer") "muRata(村田)")
      )
      (libsource (lib "") (part "GRM155R71H104KE14J"))
    )
    (comp (ref "C65")
      (value "100nF")
      (fields
        (field (name "Manufacturer Part") "GRM155R71H104KE14J")
        (field (name "Manufacturer") "muRata(村田)")
      )
      (libsource (lib "") (part "GRM155R71H104KE14J"))
    )
    (comp (ref "C66")
      (value "100nF")
      (fields
        (field (name "Manufacturer Part") "GRM155R71H104KE14J")
        (field (name "Manufacturer") "muRata(村田)")
      )
      (libsource (lib "") (part "GRM155R71H104KE14J"))
    )
    (comp (ref "C67")
      (value "100nF")
      (fields
        (field (name "Manufacturer Part") "GRM155R71H104KE14J")
        (field (name "Manufacturer") "muRata(村田)")
      )
      (libsource (lib "") (part "GRM155R71H104KE14J"))
    )
    (comp (ref "C68")
      (value "100nF")
      (fields
        (field (name "Manufacturer Part") "GRM155R71H104KE14J")
        (field (name "Manufacturer") "muRata(村田)")
      )
      (libsource (lib "") (part "GRM155R71H104KE14J"))
    )
    (comp (ref "C69")
      (value "100nF")
      (fields
        (field (name "Manufacturer Part") "GRM155R71H104KE14J")
        (field (name "Manufacturer") "muRata(村田)")
      )
      (libsource (lib "") (part "GRM155R71H104KE14J"))
    )
    (comp (ref "C70")
      (value "100nF")
      (fields
        (field (name "Manufacturer Part") "GRM155R71H104KE14J")
        (field (name "Manufacturer") "muRata(村田)")
      )
      (libsource (lib "") (part "GRM155R71H104KE14J"))
    )
    (comp (ref "C71")
      (value "100nF")
      (fields
        (field (name "Manufacturer Part") "GRM155R71H104KE14J")
        (field (name "Manufacturer") "muRata(村田)")
      )
      (libsource (lib "") (part "GRM155R71H104KE14J"))
    )
    (comp (ref "C72")
      (value "22uF")
      (fields
        (field (name "Manufacturer Part") "GRT21BR61E226ME13L")
        (field (name "Manufacturer") "muRata(村田)")
      )
      (libsource (lib "") (part "GRT21BR61E226ME13L"))
    )
    (comp (ref "L2")
      (value "600Ω")
      (fields (field (name "Manufacturer Part") "MPZ2012S601AT000") (field (name "Manufacturer") "TDK"))
      (libsource (lib "") (part "MPZ2012S601AT000"))
    )
    (comp (ref "L3")
      (value "1uH")
      (fields (field (name "Manufacturer Part") "XRIM201612S1R0MBCA") (field (name "Manufacturer") "XR(祥如)"))
      (libsource (lib "") (part "XRIM201612S1R0MBCA"))
    )
    (comp (ref "R10")
      (value "10kΩ")
      (fields (field (name "Manufacturer Part") "ERA2AEB103X") (field (name "Manufacturer") "PANASONIC(松下)"))
      (libsource (lib "") (part "ERA2AEB103X_1"))
    )
    (comp (ref "R17")
      (value "10kΩ")
      (fields (field (name "Manufacturer Part") "ERA2AEB103X") (field (name "Manufacturer") "PANASONIC(松下)"))
      (libsource (lib "") (part "ERA2AEB103X_1"))
    )
    (comp (ref "R18")
      (value "10kΩ")
      (fields (field (name "Manufacturer Part") "ERA2AEB103X") (field (name "Manufacturer") "PANASONIC(松下)"))
      (libsource (lib "") (part "ERA2AEB103X"))
    )
    (comp (ref "R19")
      (value "1kΩ")
      (fields (field (name "Manufacturer Part") "RT0402BRD071KL") (field (name "Manufacturer") "YAGEO(国巨)"))
      (libsource (lib "") (part "RT0402BRD071KL"))
    )
    (comp (ref "R20")
      (value "330Ω")
      (fields (field (name "Manufacturer Part") "RC0402JR-07330RL") (field (name "Manufacturer") "YAGEO(国巨)"))
      (libsource (lib "") (part "RC0402JR-07330RL_1"))
    )
    (comp (ref "R21")
      (value "330Ω")
      (fields (field (name "Manufacturer Part") "RC0402JR-07330RL") (field (name "Manufacturer") "YAGEO(国巨)"))
      (libsource (lib "") (part "RC0402JR-07330RL"))
    )
    (comp (ref "R22")
      (value "4.7kΩ")
      (fields (field (name "Manufacturer Part") "RC0402FR-074K7L") (field (name "Manufacturer") "YAGEO(国巨)"))
      (libsource (lib "") (part "RC0402FR-074K7L"))
    )
    (comp (ref "R23")
      (value "2.49kΩ")
      (fields (field (name "Manufacturer Part") "FRC0402F2491TS") (field (name "Manufacturer") "FOJAN(富捷)"))
      (libsource (lib "") (part "FRC0402F2491TS"))
    )
    (comp (ref "R24")
      (value "59kΩ")
      (fields (field (name "Manufacturer Part") "RS-03K5902FT") (field (name "Manufacturer") "FH(风华)"))
      (libsource (lib "") (part "RS-03K5902FT"))
    )
    (comp (ref "R25")
      (value "100kΩ")
      (fields (field (name "Manufacturer Part") "RS-03K1003FT") (field (name "Manufacturer") "FH(风华)"))
      (libsource (lib "") (part "RS-03K1003FT_C115320"))
    )
    (comp (ref "RJ1")
      (value "RT7-174AAM1A")
      (fields (field (name "Manufacturer") "UDE(涌德电子)"))
      (libsource (lib "") (part "RT7-174AAM1A"))
    )
    (comp (ref "U8")
      (value "RTL8125BG-CG")
      (fields (field (name "Manufacturer") "REALTEK(瑞昱)"))
      (libsource (lib "") (part "RTL8125BG-CG"))
    )
    (comp (ref "U9")
      (value "TLV62568DRLR")
      (fields (field (name "Manufacturer") "TI(德州仪器)"))
      (libsource (lib "") (part "TLV62568DRLR"))
    )
    (comp (ref "X1")
      (value "25MHz")
      (fields
        (field (name "Manufacturer Part") "SX3M25.000B10G40TNN")
        (field (name "Manufacturer") "SCTF(星通时频)")
      )
      (libsource (lib "") (part "SX3M25.000B10G40TNN"))
    )
    (comp (ref "C73")
      (value "100nF")
      (fields
        (field (name "Manufacturer Part") "GRM155R71H104KE14J")
        (field (name "Manufacturer") "muRata(村田)")
      )
      (libsource (lib "") (part "GRM155R71H104KE14J"))
    )
    (comp (ref "C74")
      (value "100nF")
      (fields
        (field (name "Manufacturer Part") "GRM155R71H104KE14J")
        (field (name "Manufacturer") "muRata(村田)")
      )
      (libsource (lib "") (part "GRM155R71H104KE14J"))
    )
    (comp (ref "C75")
      (value "150uF")
      (fields
        (field (name "Manufacturer Part") "GRM31CR60J157ME11L")
        (field (name "Manufacturer") "muRata(村田)")
      )
      (libsource (lib "") (part "GRM31CR60J157ME11L_1"))
    )
    (comp (ref "C76")
      (value "150uF")
      (fields
        (field (name "Manufacturer Part") "GRM31CR60J157ME11L")
        (field (name "Manufacturer") "muRata(村田)")
      )
      (libsource (lib "") (part "GRM31CR60J157ME11L_1"))
    )
    (comp (ref "C77")
      (value "150uF")
      (fields
        (field (name "Manufacturer Part") "GRM31CR60J157ME11L")
        (field (name "Manufacturer") "muRata(村田)")
      )
      (libsource (lib "") (part "GRM31CR60J157ME11L"))
    )
    (comp (ref "C78")
      (value "150uF")
      (fields
        (field (name "Manufacturer Part") "GRM31CR60J157ME11L")
        (field (name "Manufacturer") "muRata(村田)")
      )
      (libsource (lib "") (part "GRM31CR60J157ME11L_1"))
    )
    (comp (ref "C79")
      (value "100nF")
      (fields
        (field (name "Manufacturer Part") "GRM155R71H104KE14J")
        (field (name "Manufacturer") "muRata(村田)")
      )
      (libsource (lib "") (part "GRM155R71H104KE14J"))
    )
    (comp (ref "C80")
      (value "100nF")
      (fields
        (field (name "Manufacturer Part") "GRM155R71H104KE14J")
        (field (name "Manufacturer") "muRata(村田)")
      )
      (libsource (lib "") (part "GRM155R71H104KE14J"))
    )
    (comp (ref "C81")
      (value "100nF")
      (fields
        (field (name "Manufacturer Part") "GRM155R71H104KE14J")
        (field (name "Manufacturer") "muRata(村田)")
      )
      (libsource (lib "") (part "GRM155R71H104KE14J"))
    )
    (comp (ref "C82")
      (value "100nF")
      (fields
        (field (name "Manufacturer Part") "GRM155R71H104KE14J")
        (field (name "Manufacturer") "muRata(村田)")
      )
      (libsource (lib "") (part "GRM155R71H104KE14J"))
    )
    (comp (ref "C83")
      (value "100nF")
      (fields
        (field (name "Manufacturer Part") "GRM155R71H104KE14J")
        (field (name "Manufacturer") "muRata(村田)")
      )
      (libsource (lib "") (part "GRM155R71H104KE14J"))
    )
    (comp (ref "C84")
      (value "100nF")
      (fields
        (field (name "Manufacturer Part") "GRM155R71H104KE14J")
        (field (name "Manufacturer") "muRata(村田)")
      )
      (libsource (lib "") (part "GRM155R71H104KE14J"))
    )
    (comp (ref "C85")
      (value "30pF")
      (fields
        (field (name "Manufacturer Part") "TCC0402COG300J500AT")
        (field (name "Manufacturer") "CCTC(三环)")
      )
      (libsource (lib "") (part "TCC0402COG300J500AT"))
    )
    (comp (ref "C86")
      (value "30pF")
      (fields
        (field (name "Manufacturer Part") "TCC0402COG300J500AT")
        (field (name "Manufacturer") "CCTC(三环)")
      )
      (libsource (lib "") (part "TCC0402COG300J500AT"))
    )
    (comp (ref "C87")
      (value "100nF")
      (fields
        (field (name "Manufacturer Part") "GRM155R71H104KE14J")
        (field (name "Manufacturer") "muRata(村田)")
      )
      (libsource (lib "") (part "GRM155R71H104KE14J"))
    )
    (comp (ref "C88")
      (value "100nF")
      (fields
        (field (name "Manufacturer Part") "GRM155R71H104KE14J")
        (field (name "Manufacturer") "muRata(村田)")
      )
      (libsource (lib "") (part "GRM155R71H104KE14J"))
    )
    (comp (ref "C89")
      (value "100nF")
      (fields
        (field (name "Manufacturer Part") "GRM155R71H104KE14J")
        (field (name "Manufacturer") "muRata(村田)")
      )
      (libsource (lib "") (part "GRM155R71H104KE14J"))
    )
    (comp (ref "C90")
      (value "100nF")
      (fields
        (field (name "Manufacturer Part") "GRM155R71H104KE14J")
        (field (name "Manufacturer") "muRata(村田)")
      )
      (libsource (lib "") (part "GRM155R71H104KE14J"))
    )
    (comp (ref "C91")
      (value "100nF")
      (fields
        (field (name "Manufacturer Part") "GRM155R71H104KE14J")
        (field (name "Manufacturer") "muRata(村田)")
      )
      (libsource (lib "") (part "GRM155R71H104KE14J"))
    )
    (comp (ref "C92")
      (value "100nF")
      (fields
        (field (name "Manufacturer Part") "GRM155R71H104KE14J")
        (field (name "Manufacturer") "muRata(村田)")
      )
      (libsource (lib "") (part "GRM155R71H104KE14J"))
    )
    (comp (ref "C93")
      (value "100nF")
      (fields
        (field (name "Manufacturer Part") "GRM155R71H104KE14J")
        (field (name "Manufacturer") "muRata(村田)")
      )
      (libsource (lib "") (part "GRM155R71H104KE14J"))
    )
    (comp (ref "C94")
      (value "100nF")
      (fields
        (field (name "Manufacturer Part") "GRM155R71H104KE14J")
        (field (name "Manufacturer") "muRata(村田)")
      )
      (libsource (lib "") (part "GRM155R71H104KE14J"))
    )
    (comp (ref "C95")
      (value "100nF")
      (fields
        (field (name "Manufacturer Part") "GRM155R71H104KE14J")
        (field (name "Manufacturer") "muRata(村田)")
      )
      (libsource (lib "") (part "GRM155R71H104KE14J"))
    )
    (comp (ref "C96")
      (value "100nF")
      (fields
        (field (name "Manufacturer Part") "GRM155R71H104KE14J")
        (field (name "Manufacturer") "muRata(村田)")
      )
      (libsource (lib "") (part "GRM155R71H104KE14J"))
    )
    (comp (ref "C97")
      (value "100nF")
      (fields
        (field (name "Manufacturer Part") "GRM155R71H104KE14J")
        (field (name "Manufacturer") "muRata(村田)")
      )
      (libsource (lib "") (part "GRM155R71H104KE14J"))
    )
    (comp (ref "C98")
      (value "100nF")
      (fields
        (field (name "Manufacturer Part") "GRM155R71H104KE14J")
        (field (name "Manufacturer") "muRata(村田)")
      )
      (libsource (lib "") (part "GRM155R71H104KE14J"))
    )
    (comp (ref "C99")
      (value "100nF")
      (fields
        (field (name "Manufacturer Part") "GRM155R71H104KE14J")
        (field (name "Manufacturer") "muRata(村田)")
      )
      (libsource (lib "") (part "GRM155R71H104KE14J"))
    )
    (comp (ref "C100")
      (value "100nF")
      (fields
        (field (name "Manufacturer Part") "GRM155R71H104KE14J")
        (field (name "Manufacturer") "muRata(村田)")
      )
      (libsource (lib "") (part "GRM155R71H104KE14J"))
    )
    (comp (ref "C101")
      (value "100nF")
      (fields
        (field (name "Manufacturer Part") "GRM155R71H104KE14J")
        (field (name "Manufacturer") "muRata(村田)")
      )
      (libsource (lib "") (part "GRM155R71H104KE14J"))
    )
    (comp (ref "C102")
      (value "100nF")
      (fields
        (field (name "Manufacturer Part") "GRM155R71H104KE14J")
        (field (name "Manufacturer") "muRata(村田)")
      )
      (libsource (lib "") (part "GRM155R71H104KE14J"))
    )
    (comp (ref "C103")
      (value "100nF")
      (fields
        (field (name "Manufacturer Part") "GRM155R71H104KE14J")
        (field (name "Manufacturer") "muRata(村田)")
      )
      (libsource (lib "") (part "GRM155R71H104KE14J"))
    )
    (comp (ref "C104")
      (value "22uF")
      (fields
        (field (name "Manufacturer Part") "GRT21BR61E226ME13L")
        (field (name "Manufacturer") "muRata(村田)")
      )
      (libsource (lib "") (part "GRT21BR61E226ME13L"))
    )
    (comp (ref "C105")
      (value "100nF")
      (fields
        (field (name "Manufacturer Part") "GRM155R71H104KE14J")
        (field (name "Manufacturer") "muRata(村田)")
      )
      (libsource (lib "") (part "GRM155R71H104KE14J"))
    )
    (comp (ref "C106")
      (value "100nF")
      (fields
        (field (name "Manufacturer Part") "GRM155R71H104KE14J")
        (field (name "Manufacturer") "muRata(村田)")
      )
      (libsource (lib "") (part "GRM155R71H104KE14J"))
    )
    (comp (ref "C107")
      (value "100nF")
      (fields
        (field (name "Manufacturer Part") "GRM155R71H104KE14J")
        (field (name "Manufacturer") "muRata(村田)")
      )
      (libsource (lib "") (part "GRM155R71H104KE14J"))
    )
    (comp (ref "C108")
      (value "100nF")
      (fields
        (field (name "Manufacturer Part") "GRM155R71H104KE14J")
        (field (name "Manufacturer") "muRata(村田)")
      )
      (libsource (lib "") (part "GRM155R71H104KE14J"))
    )
    (comp (ref "C109")
      (value "22uF")
      (fields
        (field (name "Manufacturer Part") "GRT21BR61E226ME13L")
        (field (name "Manufacturer") "muRata(村田)")
      )
      (libsource (lib "") (part "GRT21BR61E226ME13L"))
    )
    (comp (ref "C110")
      (value "100nF")
      (fields
        (field (name "Manufacturer Part") "GRM155R71H104KE14J")
        (field (name "Manufacturer") "muRata(村田)")
      )
      (libsource (lib "") (part "GRM155R71H104KE14J_1"))
    )
    (comp (ref "D1")
      (value "USBLC6-2SC6")
      (fields (field (name "Manufacturer") "ST(意法半导体)"))
      (libsource (lib "") (part "USBLC6-2SC6"))
    )
    (comp (ref "D2")
      (value "SRV05-4_C2836319")
      (fields (field (name "Manufacturer Part") "SRV05-4") (field (name "Manufacturer") "MSKSEMI(美森科)"))
      (libsource (lib "") (part "SRV05-4_C2836319"))
    )
    (comp (ref "D3")
      (value "USBLC6-2SC6")
      (fields (field (name "Manufacturer") "ST(意法半导体)"))
      (libsource (lib "") (part "USBLC6-2SC6"))
    )
    (comp (ref "D4")
      (value "USBLC6-2SC6")
      (fields (field (name "Manufacturer") "ST(意法半导体)"))
      (libsource (lib "") (part "USBLC6-2SC6"))
    )
    (comp (ref "D5")
      (value "USBLC6-2SC6")
      (fields (field (name "Manufacturer") "ST(意法半导体)"))
      (libsource (lib "") (part "USBLC6-2SC6"))
    )
    (comp (ref "D6")
      (value "USBLC6-2SC6")
      (fields (field (name "Manufacturer") "ST(意法半导体)"))
      (libsource (lib "") (part "USBLC6-2SC6"))
    )
    (comp (ref "D7")
      (value "USBLC6-2SC6")
      (fields (field (name "Manufacturer") "ST(意法半导体)"))
      (libsource (lib "") (part "USBLC6-2SC6"))
    )
    (comp (ref "D8")
      (value "SRV05-4_C2836319")
      (fields (field (name "Manufacturer Part") "SRV05-4") (field (name "Manufacturer") "MSKSEMI(美森科)"))
      (libsource (lib "") (part "SRV05-4_C2836319"))
    )
    (comp (ref "L4")
      (value "2.2uH")
      (fields (field (name "Manufacturer Part") "MLP2012H2R2MT0S1") (field (name "Manufacturer") "TDK"))
      (libsource (lib "") (part "MLP2012H2R2MT0S1"))
    )
    (comp (ref "R26")
      (value "10kΩ")
      (fields (field (name "Manufacturer Part") "FRC0402F1002TS") (field (name "Manufacturer") "FOJAN(富捷)"))
      (libsource (lib "") (part "FRC0402F1002TS_1"))
    )
    (comp (ref "R27")
      (value "10kΩ")
      (fields (field (name "Manufacturer Part") "FRC0402F1002TS") (field (name "Manufacturer") "FOJAN(富捷)"))
      (libsource (lib "") (part "FRC0402F1002TS_1"))
    )
    (comp (ref "R28")
      (value "10kΩ")
      (fields (field (name "Manufacturer Part") "FRC0402F1002TS") (field (name "Manufacturer") "FOJAN(富捷)"))
      (libsource (lib "") (part "FRC0402F1002TS_1"))
    )
    (comp (ref "R29")
      (value "10kΩ")
      (fields (field (name "Manufacturer Part") "FRC0402F1002TS") (field (name "Manufacturer") "FOJAN(富捷)"))
      (libsource (lib "") (part "FRC0402F1002TS_1"))
    )
    (comp (ref "R30")
      (value "10kΩ")
      (fields (field (name "Manufacturer Part") "FRC0402F1002TS") (field (name "Manufacturer") "FOJAN(富捷)"))
      (libsource (lib "") (part "FRC0402F1002TS_1"))
    )
    (comp (ref "R31")
      (value "10kΩ")
      (fields (field (name "Manufacturer Part") "FRC0402F1002TS") (field (name "Manufacturer") "FOJAN(富捷)"))
      (libsource (lib "") (part "FRC0402F1002TS_1"))
    )
    (comp (ref "R32")
      (value "10kΩ")
      (fields (field (name "Manufacturer Part") "FRC0402F1002TS") (field (name "Manufacturer") "FOJAN(富捷)"))
      (libsource (lib "") (part "FRC0402F1002TS_2"))
    )
    (comp (ref "R33")
      (value "10kΩ")
      (fields (field (name "Manufacturer Part") "FRC0402F1002TS") (field (name "Manufacturer") "FOJAN(富捷)"))
      (libsource (lib "") (part "FRC0402F1002TS"))
    )
    (comp (ref "R34")
      (value "10kΩ")
      (fields (field (name "Manufacturer Part") "FRC0402F1002TS") (field (name "Manufacturer") "FOJAN(富捷)"))
      (libsource (lib "") (part "FRC0402F1002TS"))
    )
    (comp (ref "R35")
      (value "10kΩ")
      (fields (field (name "Manufacturer Part") "FRC0402F1002TS") (field (name "Manufacturer") "FOJAN(富捷)"))
      (libsource (lib "") (part "FRC0402F1002TS"))
    )
    (comp (ref "R36")
      (value "10kΩ")
      (fields (field (name "Manufacturer Part") "FRC0402F1002TS") (field (name "Manufacturer") "FOJAN(富捷)"))
      (libsource (lib "") (part "FRC0402F1002TS"))
    )
    (comp (ref "R37")
      (value "10kΩ")
      (fields (field (name "Manufacturer Part") "FRC0402F1002TS") (field (name "Manufacturer") "FOJAN(富捷)"))
      (libsource (lib "") (part "FRC0402F1002TS"))
    )
    (comp (ref "R38")
      (value "100kΩ")
      (fields (field (name "Manufacturer Part") "RS-03K1003FT") (field (name "Manufacturer") "FH(风华)"))
      (libsource (lib "") (part "RS-03K1003FT_C115320"))
    )
    (comp (ref "R39")
      (value "75kΩ")
      (fields (field (name "Manufacturer Part") "RS-03K7502FT") (field (name "Manufacturer") "FH(风华)"))
      (libsource (lib "") (part "RS-03K7502FT"))
    )
    (comp (ref "R40")
      (value "10kΩ")
      (fields (field (name "Manufacturer Part") "FRC0402F1002TS") (field (name "Manufacturer") "FOJAN(富捷)"))
      (libsource (lib "") (part "FRC0402F1002TS"))
    )
    (comp (ref "R41")
      (value "10kΩ")
      (fields (field (name "Manufacturer Part") "FRC0402F1002TS") (field (name "Manufacturer") "FOJAN(富捷)"))
      (libsource (lib "") (part "FRC0402F1002TS_1"))
    )
    (comp (ref "R42")
      (value "10kΩ")
      (fields (field (name "Manufacturer Part") "FRC0402F1002TS") (field (name "Manufacturer") "FOJAN(富捷)"))
      (libsource (lib "") (part "FRC0402F1002TS_1"))
    )
    (comp (ref "U10")
      (value "UPD720201K8-701-BAC-A")
      (fields (field (name "Manufacturer") "RENESAS(瑞萨)/IDT"))
      (libsource (lib "") (part "UPD720201K8-701-BAC-A"))
    )
    (comp (ref "U11")
      (value "1932258-1")
      (fields (field (name "Manufacturer") "TE Connectivity(泰科电子)"))
      (libsource (lib "") (part "1932258-1"))
    )
    (comp (ref "U12")
      (value "1932258-1")
      (fields (field (name "Manufacturer") "TE Connectivity(泰科电子)"))
      (libsource (lib "") (part "1932258-1"))
    )
    (comp (ref "U13")
      (value "TPS2062CDR")
      (fields (field (name "Manufacturer") "TI(德州仪器)"))
      (libsource (lib "") (part "TPS2062CDR"))
    )
    (comp (ref "U14")
      (value "TPS2052BDR")
      (fields (field (name "Manufacturer") "TI(德州仪器)"))
      (libsource (lib "") (part "TPS2052BDR"))
    )
    (comp (ref "U15")
      (value "TPS2052BDR")
      (fields (field (name "Manufacturer") "TI(德州仪器)"))
      (libsource (lib "") (part "TPS2052BDR"))
    )
    (comp (ref "U16")
      (value "W25Q80DVUXIE")
      (fields (field (name "Manufacturer") "Winbond(华邦)"))
      (libsource (lib "") (part "W25Q80DVUXIE"))
    )
    (comp (ref "U17")
      (value "TLV62568DRLR")
      (fields (field (name "Manufacturer") "TI(德州仪器)"))
      (libsource (lib "") (part "TLV62568DRLR"))
    )
    (comp (ref "USB1")
      (value "USB-269-BRW")
      (fields (field (name "Manufacturer") "XUNPU(讯普)"))
      (libsource (lib "") (part "USB-269-BRW"))
    )
    (comp (ref "USB2")
      (value "USB-269-BRW")
      (fields (field (name "Manufacturer") "XUNPU(讯普)"))
      (libsource (lib "") (part "USB-269-BRW"))
    )
    (comp (ref "X2")
      (value "24MHz")
      (fields
        (field (name "Manufacturer Part") "ABM7-24.000MHZ-D2Y-T")
        (field (name "Manufacturer") "ABRACON")
      )
      (libsource (lib "") (part "ABM7-24.000MHZ-D2Y-T"))
    )
    (comp (ref "C111")
      (value "22uF")
      (fields
        (field (name "Manufacturer Part") "GRT21BR61E226ME13L")
        (field (name "Manufacturer") "muRata(村田)")
      )
      (libsource (lib "") (part "GRT21BR61E226ME13L"))
    )
    (comp (ref "C112")
      (value "100nF")
      (fields
        (field (name "Manufacturer Part") "GRM155R71H104KE14J")
        (field (name "Manufacturer") "muRata(村田)")
      )
      (libsource (lib "") (part "GRM155R71H104KE14J_1"))
    )
    (comp (ref "C113")
      (value "100nF")
      (fields
        (field (name "Manufacturer Part") "GRM155R71H104KE14J")
        (field (name "Manufacturer") "muRata(村田)")
      )
      (libsource (lib "") (part "GRM155R71H104KE14J_2"))
    )
    (comp (ref "C114")
      (value "100nF")
      (fields
        (field (name "Manufacturer Part") "GRM155R71H104KE14J")
        (field (name "Manufacturer") "muRata(村田)")
      )
      (libsource (lib "") (part "GRM155R71H104KE14J_2"))
    )
    (comp (ref "C115")
      (value "1uF")
      (fields
        (field (name "Manufacturer Part") "MSASU105CB5105KFNA01")
        (field (name "Manufacturer") "TAIYO YUDEN(太诱)")
      )
      (libsource (lib "") (part "MSASU105CB5105KFNA01"))
    )
    (comp (ref "C116")
      (value "100nF")
      (fields
        (field (name "Manufacturer Part") "GRM155R71H104KE14J")
        (field (name "Manufacturer") "muRata(村田)")
      )
      (libsource (lib "") (part "GRM155R71H104KE14J"))
    )
    (comp (ref "C117")
      (value "100nF")
      (fields
        (field (name "Manufacturer Part") "GRM155R71H104KE14J")
        (field (name "Manufacturer") "muRata(村田)")
      )
      (libsource (lib "") (part "GRM155R71H104KE14J"))
    )
    (comp (ref "C118")
      (value "100nF")
      (fields
        (field (name "Manufacturer Part") "GRM155R71H104KE14J")
        (field (name "Manufacturer") "muRata(村田)")
      )
      (libsource (lib "") (part "GRM155R71H104KE14J"))
    )
    (comp (ref "C119")
      (value "100nF")
      (fields
        (field (name "Manufacturer Part") "GRM155R71H104KE14J")
        (field (name "Manufacturer") "muRata(村田)")
      )
      (libsource (lib "") (part "GRM155R71H104KE14J"))
    )
    (comp (ref "C120")
      (value "100nF")
      (fields
        (field (name "Manufacturer Part") "GRM155R71H104KE14J")
        (field (name "Manufacturer") "muRata(村田)")
      )
      (libsource (lib "") (part "GRM155R71H104KE14J"))
    )
    (comp (ref "C121")
      (value "100nF")
      (fields
        (field (name "Manufacturer Part") "GRM155R71H104KE14J")
        (field (name "Manufacturer") "muRata(村田)")
      )
      (libsource (lib "") (part "GRM155R71H104KE14J"))
    )
    (comp (ref "C122")
      (value "100nF")
      (fields
        (field (name "Manufacturer Part") "GRM155R71H104KE14J")
        (field (name "Manufacturer") "muRata(村田)")
      )
      (libsource (lib "") (part "GRM155R71H104KE14J"))
    )
    (comp (ref "C123")
      (value "100nF")
      (fields
        (field (name "Manufacturer Part") "GRM155R71H104KE14J")
        (field (name "Manufacturer") "muRata(村田)")
      )
      (libsource (lib "") (part "GRM155R71H104KE14J"))
    )
    (comp (ref "L5")
      (value "MPZ2012S601ATD25")
      (fields (field (name "Manufacturer") "TDK"))
      (libsource (lib "") (part "MPZ2012S601ATD25"))
    )
    (comp (ref "Q1")
      (value "AO3400A")
      (fields (field (name "Manufacturer") "AOS"))
      (libsource (lib "") (part "AO3400A"))
    )
    (comp (ref "R43")
      (value "470Ω")
      (fields (field (name "Manufacturer Part") "FRC0402F4700TS") (field (name "Manufacturer") "FOJAN(富捷)"))
      (libsource (lib "") (part "FRC0402F4700TS"))
    )
    (comp (ref "R44")
      (value "470Ω")
      (fields (field (name "Manufacturer Part") "FRC0402F4700TS") (field (name "Manufacturer") "FOJAN(富捷)"))
      (libsource (lib "") (part "FRC0402F4700TS"))
    )
    (comp (ref "R45")
      (value "470Ω")
      (fields (field (name "Manufacturer Part") "FRC0402F4700TS") (field (name "Manufacturer") "FOJAN(富捷)"))
      (libsource (lib "") (part "FRC0402F4700TS"))
    )
    (comp (ref "R46")
      (value "470Ω")
      (fields (field (name "Manufacturer Part") "FRC0402F4700TS") (field (name "Manufacturer") "FOJAN(富捷)"))
      (libsource (lib "") (part "FRC0402F4700TS"))
    )
    (comp (ref "R47")
      (value "470Ω")
      (fields (field (name "Manufacturer Part") "FRC0402F4700TS") (field (name "Manufacturer") "FOJAN(富捷)"))
      (libsource (lib "") (part "FRC0402F4700TS"))
    )
    (comp (ref "R48")
      (value "470Ω")
      (fields (field (name "Manufacturer Part") "FRC0402F4700TS") (field (name "Manufacturer") "FOJAN(富捷)"))
      (libsource (lib "") (part "FRC0402F4700TS"))
    )
    (comp (ref "R49")
      (value "470Ω")
      (fields (field (name "Manufacturer Part") "FRC0402F4700TS") (field (name "Manufacturer") "FOJAN(富捷)"))
      (libsource (lib "") (part "FRC0402F4700TS"))
    )
    (comp (ref "R50")
      (value "470Ω")
      (fields (field (name "Manufacturer Part") "FRC0402F4700TS") (field (name "Manufacturer") "FOJAN(富捷)"))
      (libsource (lib "") (part "FRC0402F4700TS"))
    )
    (comp (ref "R51")
      (value "10kΩ")
      (fields (field (name "Manufacturer Part") "FRC0402F1002TS") (field (name "Manufacturer") "FOJAN(富捷)"))
      (libsource (lib "") (part "FRC0402F1002TS"))
    )
    (comp (ref "U18")
      (value "TPD12S016RKTR")
      (fields (field (name "Manufacturer") "TI(德州仪器)"))
      (libsource (lib "") (part "TPD12S016RKTR"))
    )
    (comp (ref "USB3")
      (value "HDMI-001S")
      (fields (field (name "Manufacturer") "XUNPU(讯普)"))
      (libsource (lib "") (part "HDMI-001S"))
    )
    (comp (ref "U19")
      (value "AS0A821-H2SB-7H")
      (fields (field (name "Manufacturer") "FOXCONN(富士康)"))
      (libsource (lib "") (part "AS0A821-H2SB-7H"))
    )
  )
  (nets
    (net (code "1") (name "+5V") (class "Default")
      (node (ref "C111") (pin "2") (pinfunction "2_2") (pintype "unspecified"))
      (node (ref "C114") (pin "2") (pinfunction "2_2") (pintype "unspecified"))
      (node (ref "C13") (pin "2") (pinfunction "2_2") (pintype "unspecified"))
      (node (ref "C14") (pin "2") (pinfunction "2_2") (pintype "unspecified"))
      (node (ref "C15") (pin "2") (pinfunction "2_2") (pintype "unspecified"))
      (node (ref "C24") (pin "2") (pinfunction "2_2") (pintype "unspecified"))
      (node (ref "C25") (pin "2") (pinfunction "2_2") (pintype "unspecified"))
      (node (ref "C26") (pin "2") (pinfunction "2_2") (pintype "unspecified"))
      (node (ref "C3") (pin "1") (pinfunction "1_1") (pintype "unspecified"))
      (node (ref "C4") (pin "1") (pinfunction "1_1") (pintype "unspecified"))
      (node (ref "C73") (pin "1") (pinfunction "1_1") (pintype "unspecified"))
      (node (ref "C74") (pin "1") (pinfunction "1_1") (pintype "unspecified"))
      (node (ref "R3") (pin "1") (pinfunction "1_1") (pintype "unspecified"))
      (node (ref "U13") (pin "2") (pinfunction "IN_2") (pintype "unspecified"))
      (node (ref "U14") (pin "2") (pinfunction "IN_2") (pintype "input"))
      (node (ref "U15") (pin "2") (pinfunction "IN_2") (pintype "input"))
      (node (ref "U18") (pin "10") (pinfunction "VCC5V_10") (pintype "unspecified"))
      (node (ref "U2") (pin "2") (pinfunction "2_2") (pintype "unspecified"))
      (node (ref "U3") (pin "2") (pinfunction "2_2") (pintype "unspecified"))
      (node (ref "U4") (pin "2") (pinfunction "2_2") (pintype "unspecified"))
    )
    (net (code "2") (name "1V05") (class "Default")
      (node (ref "C101") (pin "2") (pinfunction "2_2") (pintype "unspecified"))
      (node (ref "C102") (pin "2") (pinfunction "2_2") (pintype "unspecified"))
      (node (ref "C109") (pin "1") (pinfunction "1_1") (pintype "unspecified"))
      (node (ref "C88") (pin "2") (pinfunction "2_2") (pintype "unspecified"))
      (node (ref "C90") (pin "1") (pinfunction "1_1") (pintype "unspecified"))
      (node (ref "C92") (pin "1") (pinfunction "1_1") (pintype "unspecified"))
      (node (ref "C95") (pin "1") (pinfunction "1_1") (pintype "unspecified"))
      (node (ref "C97") (pin "1") (pinfunction "1_1") (pintype "unspecified"))
      (node (ref "C98") (pin "1") (pinfunction "1_1") (pintype "unspecified"))
      (node (ref "L4") (pin "2") (pinfunction "2_2") (pintype "unspecified"))
      (node (ref "R39") (pin "2") (pinfunction "2_2") (pintype "input"))
      (node (ref "U10") (pin "12") (pinfunction "VDD10_12") (pintype "unspecified"))
      (node (ref "U10") (pin "28") (pinfunction "VDD10_28") (pintype "unspecified"))
      (node (ref "U10") (pin "37") (pinfunction "VDD10_37") (pintype "unspecified"))
      (node (ref "U10") (pin "43") (pinfunction "VDD10_43") (pintype "unspecified"))
      (node (ref "U10") (pin "54") (pinfunction "VDD10_54") (pintype "unspecified"))
      (node (ref "U10") (pin "60") (pinfunction "VDD10_60") (pintype "unspecified"))
      (node (ref "U10") (pin "63") (pinfunction "VDD10_63") (pintype "unspecified"))
      (node (ref "U10") (pin "9") (pinfunction "VDD10_9") (pintype "unspecified"))
    )
    (net (code "3") (name "1V05_PG") (class "Default")
      (node (ref "C110") (pin "2") (pinfunction "2_2") (pintype "unspecified"))
      (node (ref "R40") (pin "1") (pinfunction "1_1") (pintype "unspecified"))
      (node (ref "U10") (pin "14") (pinfunction "PONRSTB_14") (pintype "unspecified"))
      (node (ref "U17") (pin "6") (pinfunction "NC/PG_6") (pintype "unspecified"))
    )
    (net (code "4") (name "3V3M") (class "Default")
      (node (ref "C100") (pin "2") (pinfunction "2_2") (pintype "unspecified"))
      (node (ref "C103") (pin "2") (pinfunction "2_2") (pintype "unspecified"))
      (node (ref "C104") (pin "2") (pinfunction "2_2") (pintype "unspecified"))
      (node (ref "C112") (pin "1") (pinfunction "1_1") (pintype "unspecified"))
      (node (ref "C27") (pin "2") (pinfunction "2_2") (pintype "unspecified"))
      (node (ref "C28") (pin "2") (pinfunction "2_2") (pintype "unspecified"))
      (node (ref "C38") (pin "2") (pinfunction "2_2") (pintype "input"))
      (node (ref "C39") (pin "2") (pinfunction "2_2") (pintype "input"))
      (node (ref "C40") (pin "2") (pinfunction "2_2") (pintype "input"))
      (node (ref "C41") (pin "2") (pinfunction "2_2") (pintype "input"))
      (node (ref "C42") (pin "2") (pinfunction "2_2") (pintype "input"))
      (node (ref "C5") (pin "1") (pinfunction "1_1") (pintype "unspecified"))
      (node (ref "C6") (pin "1") (pinfunction "1_1") (pintype "unspecified"))
      (node (ref "C87") (pin "2") (pinfunction "2_2") (pintype "unspecified"))
      (node (ref "C89") (pin "2") (pinfunction "2_2") (pintype "unspecified"))
      (node (ref "C91") (pin "1") (pinfunction "1_1") (pintype "unspecified"))
      (node (ref "C94") (pin "1") (pinfunction "1_1") (pintype "unspecified"))
      (node (ref "C96") (pin "1") (pinfunction "1_1") (pintype "unspecified"))
      (node (ref "C99") (pin "1") (pinfunction "1_1") (pintype "unspecified"))
      (node (ref "L1") (pin "2") (pinfunction "2_2") (pintype "unspecified"))
      (node (ref "L2") (pin "2") (pinfunction "2_2") (pintype "unspecified"))
      (node (ref "R14") (pin "2") (pinfunction "2_2") (pintype "unspecified"))
      (node (ref "R15") (pin "2") (pinfunction "2_2") (pintype "unspecified"))
      (node (ref "R16") (pin "2") (pinfunction "2_2") (pintype "unspecified"))
      (node (ref "R26") (pin "2") (pinfunction "2_2") (pintype "unspecified"))
      (node (ref "R27") (pin "2") (pinfunction "2_2") (pintype "unspecified"))
      (node (ref "R28") (pin "1") (pinfunction "1_1") (pintype "unspecified"))
      (node (ref "R29") (pin "1") (pinfunction "1_1") (pintype "unspecified"))
      (node (ref "R30") (pin "2") (pinfunction "2_2") (pintype "unspecified"))
      (node (ref "R31") (pin "2") (pinfunction "2_2") (pintype "unspecified"))
      (node (ref "R32") (pin "2") (pinfunction "2_2") (pintype "unspecified"))
      (node (ref "R33") (pin "2") (pinfunction "2_2") (pintype "unspecified"))
      (node (ref "R34") (pin "2") (pinfunction "2_2") (pintype "unspecified"))
      (node (ref "R40") (pin "2") (pinfunction "2_2") (pintype "unspecified"))
      (node (ref "R41") (pin "2") (pinfunction "2_2") (pintype "unspecified"))
      (node (ref "R42") (pin "2") (pinfunction "2_2") (pintype "unspecified"))
      (node (ref "U10") (pin "15") (pinfunction "VDD33_15") (pintype "unspecified"))
      (node (ref "U10") (pin "29") (pinfunction "VDD33_29") (pintype "unspecified"))
      (node (ref "U10") (pin "32") (pinfunction "AVDD33_32") (pintype "unspecified"))
      (node (ref "U10") (pin "40") (pinfunction "VDD33_40") (pintype "unspecified"))
      (node (ref "U10") (pin "49") (pinfunction "VDD33_49") (pintype "unspecified"))
      (node (ref "U10") (pin "57") (pinfunction "VDD33_57") (pintype "unspecified"))
      (node (ref "U10") (pin "6") (pinfunction "AVDD33_6") (pintype "unspecified"))
      (node (ref "U10") (pin "66") (pinfunction "VDD33_66") (pintype "unspecified"))
      (node (ref "U16") (pin "8") (pinfunction "VCC_8") (pintype "unspecified"))
      (node (ref "U17") (pin "3") (pinfunction "VIN_3") (pintype "unspecified"))
      (node (ref "U17") (pin "5") (pinfunction "EN_5") (pintype "unspecified"))
      (node (ref "U18") (pin "23") (pinfunction "VCCA_23") (pintype "unspecified"))
      (node (ref "U9") (pin "3") (pinfunction "VIN_3") (pintype "unspecified"))
    )
    (net (code "5") (name "3V3_WIFI") (class "Default")
      (node (ref "C29") (pin "1") (pinfunction "1_1") (pintype "unspecified"))
      (node (ref "C30") (pin "2") (pinfunction "2_2") (pintype "unspecified"))
      (node (ref "C31") (pin "1") (pinfunction "1_1") (pintype "unspecified"))
      (node (ref "C32") (pin "2") (pinfunction "2_2") (pintype "unspecified"))
      (node (ref "C36") (pin "2") (pinfunction "2_2") (pintype "unspecified"))
      (node (ref "C37") (pin "2") (pinfunction "2_2") (pintype "unspecified"))
      (node (ref "L1") (pin "1") (pinfunction "1_1") (pintype "unspecified"))
      (node (ref "R12") (pin "1") (pinfunction "1_1") (pintype "unspecified"))
      (node (ref "R13") (pin "1") (pinfunction "1_1") (pintype "unspecified"))
      (node (ref "R9") (pin "2") (pinfunction "2_2") (pintype "unspecified"))
      (node (ref "U6") (pin "2") (pinfunction "2_2") (pintype "unspecified"))
      (node (ref "U6") (pin "4") (pinfunction "4_4") (pintype "unspecified"))
      (node (ref "U6") (pin "72") (pinfunction "72_72") (pintype "unspecified"))
      (node (ref "U6") (pin "74") (pinfunction "74_74") (pintype "unspecified"))
    )
    (net (code "6") (name "9ETH") (class "Default")
      (node (ref "C58") (pin "1") (pinfunction "1_1") (pintype "unspecified"))
      (node (ref "C59") (pin "2") (pinfunction "2_2") (pintype "unspecified"))
      (node (ref "C61") (pin "2") (pinfunction "2_2") (pintype "unspecified"))
      (node (ref "C63") (pin "2") (pinfunction "2_2") (pintype "unspecified"))
      (node (ref "C64") (pin "1") (pinfunction "1_1") (pintype "unspecified"))
      (node (ref "C67") (pin "1") (pinfunction "1_1") (pintype "unspecified"))
      (node (ref "C71") (pin "1") (pinfunction "1_1") (pintype "unspecified"))
      (node (ref "C72") (pin "2") (pinfunction "2_2") (pintype "unspecified"))
      (node (ref "L3") (pin "2") (pinfunction "2_2") (pintype "unspecified"))
      (node (ref "R24") (pin "2") (pinfunction "2_2") (pintype "unspecified"))
      (node (ref "U8") (pin "11") (pinfunction "AVDD09_11") (pintype "unspecified"))
      (node (ref "U8") (pin "16") (pinfunction "AVDD09_16") (pintype "unspecified"))
      (node (ref "U8") (pin "22") (pinfunction "AVDD09_22") (pintype "unspecified"))
      (node (ref "U8") (pin "28") (pinfunction "DVDD09_28") (pintype "unspecified"))
      (node (ref "U8") (pin "37") (pinfunction "EVDD09_37") (pintype "unspecified"))
      (node (ref "U8") (pin "47") (pinfunction "DVDD09_47") (pintype "unspecified"))
      (node (ref "U8") (pin "8") (pinfunction "DVDD09_8") (pintype "unspecified"))
    )
    (net (code "7") (name "19V_SYS") (class "Default")
      (node (ref "C10") (pin "1") (pinfunction "1_1") (pintype "unspecified"))
      (node (ref "C11") (pin "1") (pinfunction "1_1") (pintype "unspecified"))
      (node (ref "C12") (pin "1") (pinfunction "1_1") (pintype "unspecified"))
      (node (ref "C9") (pin "1") (pinfunction "1_1") (pintype "unspecified"))
      (node (ref "DC1") (pin "6") (pinfunction "6_6") (pintype "unspecified"))
      (node (ref "R1") (pin "1") (pinfunction "1_1") (pintype "unspecified"))
      (node (ref "R11") (pin "1") (pinfunction "1_1") (pintype "unspecified"))
      (node (ref "U1") (pin "2") (pinfunction "VIN_2") (pintype "unspecified"))
      (node (ref "U5") (pin "2") (pinfunction "VIN_2") (pintype "unspecified"))
    )
    (net (code "8") (name "BL_USB_N") (class "Default")
      (node (ref "U6") (pin "5") (pinfunction "5_5") (pintype "unspecified"))
    )
    (net (code "9") (name "BL_USB_P") (class "Default")
      (node (ref "U6") (pin "3") (pinfunction "3_3") (pintype "unspecified"))
    )
    (net (code "10") (name "CLOCK_ETH") (class "Default")
      (node (ref "U8") (pin "10") (pinfunction "CKXTAL1_10") (pintype "unspecified"))
      (node (ref "X1") (pin "3") (pinfunction "OUTPUT_3") (pintype "unspecified"))
    )
    (net (code "11") (name "ETH_CLKREQ_N") (class "Default")
      (node (ref "R17") (pin "1") (pinfunction "1_1") (pintype "input"))
      (node (ref "U8") (pin "48") (pinfunction "CLKREQB_48") (pintype "unspecified"))
    )
    (net (code "12") (name "ETH_CLK_N") (class "Default")
      (node (ref "U8") (pin "45") (pinfunction "REFCLK_N_45") (pintype "unspecified"))
    )
    (net (code "13") (name "ETH_CLK_P") (class "Default")
      (node (ref "U8") (pin "44") (pinfunction "REFCLK_P_44") (pintype "unspecified"))
    )
    (net (code "14") (name "ETH_MDI0_N") (class "Default")
      (node (ref "RJ1") (pin "R2") (pinfunction "TD1-_R2") (pintype "unspecified"))
      (node (ref "U8") (pin "14") (pinfunction "MDIN0_14") (pintype "unspecified"))
    )
    (net (code "15") (name "ETH_MDI0_P") (class "Default")
      (node (ref "RJ1") (pin "R1") (pinfunction "TD1+_R1") (pintype "unspecified"))
      (node (ref "U8") (pin "13") (pinfunction "MDIP0_13") (pintype "unspecified"))
    )
    (net (code "16") (name "ETH_MDI1_N") (class "Default")
      (node (ref "RJ1") (pin "R4") (pinfunction "TD2-_R4") (pintype "unspecified"))
      (node (ref "U8") (pin "18") (pinfunction "MDIN1_18") (pintype "unspecified"))
    )
    (net (code "17") (name "ETH_MDI1_P") (class "Default")
      (node (ref "RJ1") (pin "R3") (pinfunction "TD2+_R3") (pintype "unspecified"))
      (node (ref "U8") (pin "17") (pinfunction "MDIP1_17") (pintype "unspecified"))
    )
    (net (code "18") (name "ETH_MDI2_N") (class "Default")
      (node (ref "RJ1") (pin "R8") (pinfunction "TD3-_R8") (pintype "unspecified"))
      (node (ref "U8") (pin "21") (pinfunction "MDIN2_21") (pintype "unspecified"))
    )
    (net (code "19") (name "ETH_MDI2_P") (class "Default")
      (node (ref "RJ1") (pin "R7") (pinfunction "TD3+_R7") (pintype "unspecified"))
      (node (ref "U8") (pin "20") (pinfunction "MDIP2_20") (pintype "unspecified"))
    )
    (net (code "20") (name "ETH_MDI3_N") (class "Default")
      (node (ref "RJ1") (pin "R9") (pinfunction "TD4+_R9") (pintype "unspecified"))
      (node (ref "U8") (pin "24") (pinfunction "MDIN3_24") (pintype "unspecified"))
    )
    (net (code "21") (name "ETH_MDI3_P") (class "Default")
      (node (ref "RJ1") (pin "R10") (pinfunction "TD4-_R10") (pintype "unspecified"))
      (node (ref "U8") (pin "23") (pinfunction "MDIP3_23") (pintype "unspecified"))
    )
    (net (code "22") (name "ETH_RST_N") (class "Default")
      (node (ref "R10") (pin "2") (pinfunction "2_2") (pintype "input"))
      (node (ref "U8") (pin "36") (pinfunction "PERSTB_36") (pintype "unspecified"))
    )
    (net (code "23") (name "ETH_RX_N") (class "Default")
      (node (ref "C56") (pin "2") (pinfunction "2_2") (pintype "unspecified"))
    )
    (net (code "24") (name "ETH_RX_P") (class "Default")
      (node (ref "C1") (pin "2") (pinfunction "2_2") (pintype "unspecified"))
      (node (ref "C10") (pin "2") (pinfunction "2_2") (pintype "unspecified"))
      (node (ref "C100") (pin "1") (pinfunction "1_1") (pintype "unspecified"))
      (node (ref "C101") (pin "1") (pinfunction "1_1") (pintype "unspecified"))
      (node (ref "C102") (pin "1") (pinfunction "1_1") (pintype "unspecified"))
      (node (ref "C103") (pin "1") (pinfunction "1_1") (pintype "unspecified"))
      (node (ref "C104") (pin "1") (pinfunction "1_1") (pintype "unspecified"))
      (node (ref "C109") (pin "2") (pinfunction "2_2") (pintype "unspecified"))
      (node (ref "C11") (pin "2") (pinfunction "2_2") (pintype "unspecified"))
      (node (ref "C110") (pin "1") (pinfunction "1_1") (pintype "unspecified"))
      (node (ref "C113") (pin "1") (pinfunction "1_1") (pintype "unspecified"))
      (node (ref "C12") (pin "2") (pinfunction "2_2") (pintype "unspecified"))
      (node (ref "C27") (pin "1") (pinfunction "1_1") (pintype "unspecified"))
      (node (ref "C28") (pin "1") (pinfunction "1_1") (pintype "unspecified"))
      (node (ref "C29") (pin "2") (pinfunction "2_2") (pintype "unspecified"))
      (node (ref "C3") (pin "2") (pinfunction "2_2") (pintype "unspecified"))
      (node (ref "C30") (pin "1") (pinfunction "1_1") (pintype "unspecified"))
      (node (ref "C31") (pin "2") (pinfunction "2_2") (pintype "unspecified"))
      (node (ref "C32") (pin "1") (pinfunction "1_1") (pintype "unspecified"))
      (node (ref "C35") (pin "1") (pinfunction "1_1") (pintype "unspecified"))
      (node (ref "C36") (pin "1") (pinfunction "1_1") (pintype "unspecified"))
      (node (ref "C37") (pin "1") (pinfunction "1_1") (pintype "unspecified"))
      (node (ref "C4") (pin "2") (pinfunction "2_2") (pintype "unspecified"))
      (node (ref "C43") (pin "2") (pinfunction "2_2") (pintype "unspecified"))
      (node (ref "C5") (pin "2") (pinfunction "2_2") (pintype "unspecified"))
      (node (ref "C53") (pin "2") (pinfunction "2_2") (pintype "unspecified"))
      (node (ref "C54") (pin "1") (pinfunction "1_1") (pintype "unspecified"))
      (node (ref "C55") (pin "1") (pinfunction "1_1") (pintype "unspecified"))
      (node (ref "C57") (pin "2") (pinfunction "2_2") (pintype "unspecified"))
      (node (ref "C58") (pin "2") (pinfunction "2_2") (pintype "unspecified"))
      (node (ref "C59") (pin "1") (pinfunction "1_1") (pintype "unspecified"))
      (node (ref "C6") (pin "2") (pinfunction "2_2") (pintype "unspecified"))
      (node (ref "C60") (pin "1") (pinfunction "1_1") (pintype "unspecified"))
      (node (ref "C61") (pin "1") (pinfunction "1_1") (pintype "unspecified"))
      (node (ref "C62") (pin "1") (pinfunction "1_1") (pintype "unspecified"))
      (node (ref "C63") (pin "1") (pinfunction "1_1") (pintype "unspecified"))
      (node (ref "C64") (pin "2") (pinfunction "2_2") (pintype "unspecified"))
      (node (ref "C65") (pin "2") (pinfunction "2_2") (pintype "unspecified"))
      (node (ref "C66") (pin "2") (pinfunction "2_2") (pintype "unspecified"))
      (node (ref "C67") (pin "2") (pinfunction "2_2") (pintype "unspecified"))
      (node (ref "C68") (pin "2") (pinfunction "2_2") (pintype "unspecified"))
      (node (ref "C69") (pin "2") (pinfunction "2_2") (pintype "unspecified"))
      (node (ref "C70") (pin "2") (pinfunction "2_2") (pintype "unspecified"))
      (node (ref "C71") (pin "2") (pinfunction "2_2") (pintype "unspecified"))
      (node (ref "C72") (pin "1") (pinfunction "1_1") (pintype "unspecified"))
      (node (ref "C73") (pin "2") (pinfunction "2_2") (pintype "unspecified"))
      (node (ref "C74") (pin "2") (pinfunction "2_2") (pintype "unspecified"))
      (node (ref "C75") (pin "1") (pinfunction "1_1") (pintype "unspecified"))
      (node (ref "C76") (pin "1") (pinfunction "1_1") (pintype "unspecified"))
      (node (ref "C77") (pin "2") (pinfunction "2_2") (pintype "unspecified"))
      (node (ref "C78") (pin "1") (pinfunction "1_1") (pintype "unspecified"))
      (node (ref "C79") (pin "1") (pinfunction "1_1") (pintype "unspecified"))
      (node (ref "C8") (pin "2") (pinfunction "2_2") (pintype "unspecified"))
      (node (ref "C80") (pin "1") (pinfunction "1_1") (pintype "unspecified"))
      (node (ref "C81") (pin "1") (pinfunction "1_1") (pintype "unspecified"))
      (node (ref "C82") (pin "1") (pinfunction "1_1") (pintype "unspecified"))
      (node (ref "C85") (pin "1") (pinfunction "1_1") (pintype "unspecified"))
      (node (ref "C86") (pin "1") (pinfunction "1_1") (pintype "unspecified"))
      (node (ref "C87") (pin "1") (pinfunction "1_1") (pintype "unspecified"))
      (node (ref "C88") (pin "1") (pinfunction "1_1") (pintype "unspecified"))
      (node (ref "C89") (pin "1") (pinfunction "1_1") (pintype "unspecified"))
      (node (ref "C9") (pin "2") (pinfunction "2_2") (pintype "unspecified"))
      (node (ref "C90") (pin "2") (pinfunction "2_2") (pintype "unspecified"))
      (node (ref "C91") (pin "2") (pinfunction "2_2") (pintype "unspecified"))
      (node (ref "C92") (pin "2") (pinfunction "2_2") (pintype "unspecified"))
      (node (ref "C93") (pin "2") (pinfunction "2_2") (pintype "unspecified"))
      (node (ref "C94") (pin "2") (pinfunction "2_2") (pintype "unspecified"))
      (node (ref "C95") (pin "2") (pinfunction "2_2") (pintype "unspecified"))
      (node (ref "C96") (pin "2") (pinfunction "2_2") (pintype "unspecified"))
      (node (ref "C97") (pin "2") (pinfunction "2_2") (pintype "unspecified"))
      (node (ref "C98") (pin "2") (pinfunction "2_2") (pintype "unspecified"))
      (node (ref "C99") (pin "2") (pinfunction "2_2") (pintype "unspecified"))
      (node (ref "CN1") (pin "1") (pinfunction "S1_1") (pintype "unspecified"))
      (node (ref "CN1") (pin "11") (pinfunction "P4_11") (pintype "unspecified"))
      (node (ref "CN1") (pin "12") (pinfunction "P5_12") (pintype "unspecified"))
      (node (ref "CN1") (pin "13") (pinfunction "P6_13") (pintype "unspecified"))
      (node (ref "CN1") (pin "17") (pinfunction "P10_17") (pintype "unspecified"))
      (node (ref "CN1") (pin "18") (pinfunction "P11_18") (pintype "unspecified"))
      (node (ref "CN1") (pin "19") (pinfunction "P12_19") (pintype "unspecified"))
      (node (ref "CN1") (pin "23") (pinfunction "SHELL_23") (pintype "unspecified"))
      (node (ref "CN1") (pin "24") (pinfunction "SHELL_24") (pintype "unspecified"))
      (node (ref "CN1") (pin "4") (pinfunction "S4_4") (pintype "unspecified"))
      (node (ref "CN1") (pin "7") (pinfunction "S7_7") (pintype "unspecified"))
      (node (ref "CN2") (pin "1") (pinfunction "S1_1") (pintype "unspecified"))
      (node (ref "CN2") (pin "11") (pinfunction "P4_11") (pintype "unspecified"))
      (node (ref "CN2") (pin "12") (pinfunction "P5_12") (pintype "unspecified"))
      (node (ref "CN2") (pin "13") (pinfunction "P6_13") (pintype "unspecified"))
      (node (ref "CN2") (pin "17") (pinfunction "P10_17") (pintype "unspecified"))
      (node (ref "CN2") (pin "18") (pinfunction "P11_18") (pintype "unspecified"))
      (node (ref "CN2") (pin "19") (pinfunction "P12_19") (pintype "unspecified"))
      (node (ref "CN2") (pin "23") (pinfunction "SHELL_23") (pintype "unspecified"))
      (node (ref "CN2") (pin "24") (pinfunction "SHELL_24") (pintype "unspecified"))
      (node (ref "CN2") (pin "4") (pinfunction "S4_4") (pintype "unspecified"))
      (node (ref "CN2") (pin "7") (pinfunction "S7_7") (pintype "unspecified"))
      (node (ref "D1") (pin "2") (pinfunction "2_2") (pintype "input"))
      (node (ref "D3") (pin "2") (pinfunction "2_2") (pintype "input"))
      (node (ref "D4") (pin "2") (pinfunction "2_2") (pintype "input"))
      (node (ref "D5") (pin "2") (pinfunction "2_2") (pintype "input"))
      (node (ref "DC1") (pin "2") (pinfunction "2_2") (pintype "unspecified"))
      (node (ref "DC1") (pin "3") (pinfunction "3_3") (pintype "unspecified"))
      (node (ref "DC1") (pin "5") (pinfunction "5_5") (pintype "unspecified"))
      (node (ref "L5") (pin "2") (pinfunction "2_2") (pintype "unspecified"))
      (node (ref "Q1") (pin "2") (pinfunction "S_2") (pintype "unspecified"))
      (node (ref "R23") (pin "1") (pinfunction "1_1") (pintype "unspecified"))
      (node (ref "R25") (pin "2") (pinfunction "2_2") (pintype "unspecified"))
      (node (ref "R35") (pin "2") (pinfunction "2_2") (pintype "unspecified"))
      (node (ref "R36") (pin "2") (pinfunction "2_2") (pintype "unspecified"))
      (node (ref "R37") (pin "2") (pinfunction "2_2") (pintype "unspecified"))
      (node (ref "R38") (pin "2") (pinfunction "2_2") (pintype "unspecified"))
      (node (ref "R4") (pin "1") (pinfunction "1_1") (pintype "unspecified"))
      (node (ref "R51") (pin "2") (pinfunction "2_2") (pintype "unspecified"))
      (node (ref "R6") (pin "1") (pinfunction "1_1") (pintype "unspecified"))
      (node (ref "R7") (pin "1") (pinfunction "1_1") (pintype "unspecified"))
      (node (ref "R8") (pin "1") (pinfunction "1_1") (pintype "unspecified"))
      (node (ref "RJ1") (pin "1") (pinfunction "GND_1") (pintype "unspecified"))
      (node (ref "RJ1") (pin "2") (pinfunction "GND_2") (pintype "unspecified"))
      (node (ref "U1") (pin "7") (pinfunction "GND_7") (pintype "unspecified"))
      (node (ref "U1") (pin "9") (pinfunction "EP_9") (pintype "unspecified"))
      (node (ref "U10") (pin "34") (pinfunction "IC(L)_34") (pintype "unspecified"))
      (node (ref "U10") (pin "69") (pinfunction "EP_69") (pintype "unspecified"))
      (node (ref "U13") (pin "1") (pinfunction "GND_1") (pintype "unspecified"))
      (node (ref "U14") (pin "1") (pinfunction "GND_1") (pintype "unspecified"))
      (node (ref "U15") (pin "1") (pinfunction "GND_1") (pintype "unspecified"))
      (node (ref "U16") (pin "4") (pinfunction "GND_4") (pintype "unspecified"))
      (node (ref "U16") (pin "9") (pinfunction "EP_9") (pintype "unspecified"))
      (node (ref "U17") (pin "2") (pinfunction "GND_2") (pintype "unspecified"))
      (node (ref "U5") (pin "7") (pinfunction "GND_7") (pintype "unspecified"))
      (node (ref "U5") (pin "9") (pinfunction "EP_9") (pintype "unspecified"))
      (node (ref "U6") (pin "1") (pinfunction "1_1") (pintype "unspecified"))
      (node (ref "U6") (pin "33") (pinfunction "33_33") (pintype "unspecified"))
      (node (ref "U6") (pin "39") (pinfunction "39_39") (pintype "unspecified"))
      (node (ref "U6") (pin "45") (pinfunction "45_45") (pintype "unspecified"))
      (node (ref "U6") (pin "51") (pinfunction "51_51") (pintype "unspecified"))
      (node (ref "U6") (pin "57") (pinfunction "57_57") (pintype "unspecified"))
      (node (ref "U6") (pin "63") (pinfunction "63_63") (pintype "unspecified"))
      (node (ref "U6") (pin "69") (pinfunction "69_69") (pintype "unspecified"))
      (node (ref "U6") (pin "7") (pinfunction "7_7") (pintype "unspecified"))
      (node (ref "U6") (pin "75") (pinfunction "75_75") (pintype "unspecified"))
      (node (ref "U6") (pin "76") (pinfunction "76_76") (pintype "unspecified"))
      (node (ref "U6") (pin "77") (pinfunction "77_77") (pintype "unspecified"))
      (node (ref "U7") (pin "1") (pinfunction "1_1") (pintype "unspecified"))
      (node (ref "U7") (pin "15") (pinfunction "15_15") (pintype "unspecified"))
      (node (ref "U7") (pin "21") (pinfunction "21_21") (pintype "unspecified"))
      (node (ref "U7") (pin "27") (pinfunction "27_27") (pintype "unspecified"))
      (node (ref "U7") (pin "3") (pinfunction "3_3") (pintype "unspecified"))
      (node (ref "U7") (pin "33") (pinfunction "33_33") (pintype "unspecified"))
      (node (ref "U7") (pin "39") (pinfunction "39_39") (pintype "unspecified"))
      (node (ref "U7") (pin "45") (pinfunction "45_45") (pintype "unspecified"))
      (node (ref "U7") (pin "51") (pinfunction "51_51") (pintype "unspecified"))
      (node (ref "U7") (pin "57") (pinfunction "57_57") (pintype "unspecified"))
      (node (ref "U7") (pin "71") (pinfunction "71_71") (pintype "unspecified"))
      (node (ref "U7") (pin "73") (pinfunction "73_73") (pintype "unspecified"))
      (node (ref "U7") (pin "75") (pinfunction "75_75") (pintype "unspecified"))
      (node (ref "U7") (pin "76") (pinfunction "76_76") (pintype "unspecified"))
      (node (ref "U7") (pin "77") (pinfunction "77_77") (pintype "unspecified"))
      (node (ref "U7") (pin "9") (pinfunction "9_9") (pintype "unspecified"))
      (node (ref "U8") (pin "40") (pinfunction "GND_40") (pintype "unspecified"))
      (node (ref "U8") (pin "49") (pinfunction "GND_49") (pintype "unspecified"))
      (node (ref "U9") (pin "2") (pinfunction "GND_2") (pintype "unspecified"))
      (node (ref "USB1") (pin "10") (pinfunction "GND_10") (pintype "unspecified"))
      (node (ref "USB1") (pin "11") (pinfunction "GND_11") (pintype "unspecified"))
      (node (ref "USB1") (pin "12") (pinfunction "GND_12") (pintype "unspecified"))
      (node (ref "USB1") (pin "4") (pinfunction "GND_4") (pintype "unspecified"))
      (node (ref "USB1") (pin "8") (pinfunction "GND_8") (pintype "unspecified"))
      (node (ref "USB1") (pin "9") (pinfunction "GND_9") (pintype "unspecified"))
      (node (ref "USB2") (pin "10") (pinfunction "GND_10") (pintype "unspecified"))
      (node (ref "USB2") (pin "11") (pinfunction "GND_11") (pintype "unspecified"))
      (node (ref "USB2") (pin "12") (pinfunction "GND_12") (pintype "unspecified"))
      (node (ref "USB2") (pin "4") (pinfunction "GND_4") (pintype "unspecified"))
      (node (ref "USB2") (pin "8") (pinfunction "GND_8") (pintype "unspecified"))
      (node (ref "USB2") (pin "9") (pinfunction "GND_9") (pintype "unspecified"))
      (node (ref "USB3") (pin "11") (pinfunction "TMDS_Clock_Shield_11") (pintype "unspecified"))
      (node (ref "USB3") (pin "17") (pinfunction "DDC/CEC_Ground_17") (pintype "unspecified"))
      (node (ref "USB3") (pin "2") (pinfunction "TMDS_Data_2_Shield_2") (pintype "unspecified"))
      (node (ref "USB3") (pin "5") (pinfunction "TMDS_Data_1_Shield_5") (pintype "unspecified"))
      (node (ref "USB3") (pin "8") (pinfunction "TMDS_Data_0_Shield_8") (pintype "unspecified"))
    )
    (net (code "25") (name "ETH_TX_N") (class "Default")
      (node (ref "U8") (pin "42") (pinfunction "HSIN_42") (pintype "unspecified"))
    )
    (net (code "26") (name "ETH_TX_P") (class "Default")
      (node (ref "U8") (pin "41") (pinfunction "HSIP_41") (pintype "unspecified"))
    )
    (net (code "27") (name "ETH_WAKE_N") (class "Default")
      (node (ref "R19") (pin "2") (pinfunction "2_2") (pintype "unspecified"))
      (node (ref "U8") (pin "2") (pinfunction "LANWAKEB_2") (pintype "unspecified"))
    )
    (net (code "28") (name "HDMI_5V_OUT") (class "Default")
      (node (ref "C113") (pin "2") (pinfunction "2_2") (pintype "unspecified"))
      (node (ref "U18") (pin "12") (pinfunction "5V_OUT_12") (pintype "unspecified"))
      (node (ref "USB3") (pin "18") (pinfunction "+5V_Power_18") (pintype "unspecified"))
    )
    (net (code "29") (name "HDMI_CEC_B") (class "Default")
      (node (ref "U18") (pin "6") (pinfunction "CEC_B_6") (pintype "unspecified"))
      (node (ref "USB3") (pin "13") (pinfunction "CEC_13") (pintype "unspecified"))
    )
    (net (code "30") (name "HDMI_CLK_N") (class "Default")
      (node (ref "C123") (pin "1") (pinfunction "1_1") (pintype "unspecified"))
      (node (ref "USB3") (pin "12") (pinfunction "TMDS_Clock-_12") (pintype "unspecified"))
    )
    (net (code "31") (name "HDMI_CLK_P") (class "Default")
      (node (ref "C122") (pin "1") (pinfunction "1_1") (pintype "unspecified"))
      (node (ref "USB3") (pin "10") (pinfunction "TMDS_Clock+_10") (pintype "unspecified"))
    )
    (net (code "32") (name "HDMI_D0_N") (class "Default")
      (node (ref "C121") (pin "1") (pinfunction "1_1") (pintype "unspecified"))
      (node (ref "USB3") (pin "9") (pinfunction "TMDS_Data_0-_9") (pintype "unspecified"))
    )
    (net (code "33") (name "HDMI_D0_P") (class "Default")
      (node (ref "C120") (pin "1") (pinfunction "1_1") (pintype "unspecified"))
      (node (ref "USB3") (pin "7") (pinfunction "TMDS_Data_0+_7") (pintype "unspecified"))
    )
    (net (code "34") (name "HDMI_D1_N") (class "Default")
      (node (ref "C119") (pin "1") (pinfunction "1_1") (pintype "unspecified"))
      (node (ref "USB3") (pin "6") (pinfunction "TMDS_Data_1-_6") (pintype "unspecified"))
    )
    (net (code "35") (name "HDMI_D1_P") (class "Default")
      (node (ref "C118") (pin "1") (pinfunction "1_1") (pintype "unspecified"))
      (node (ref "USB3") (pin "4") (pinfunction "TMDS_Data_1+_4") (pintype "unspecified"))
    )
    (net (code "36") (name "HDMI_D2_N") (class "Default")
      (node (ref "C117") (pin "1") (pinfunction "1_1") (pintype "unspecified"))
      (node (ref "USB3") (pin "3") (pinfunction "TMDS_Data_2-_3") (pintype "unspecified"))
    )
    (net (code "37") (name "HDMI_D2_P") (class "Default")
      (node (ref "C116") (pin "1") (pinfunction "1_1") (pintype "unspecified"))
      (node (ref "USB3") (pin "1") (pinfunction "TMDS_Data_2+_1") (pintype "unspecified"))
    )
    (net (code "38") (name "HDMI_HPD_B") (class "Default")
      (node (ref "U18") (pin "9") (pinfunction "HPD_B_9") (pintype "unspecified"))
      (node (ref "USB3") (pin "19") (pinfunction "Hot_Plug_Detect_19") (pintype "unspecified"))
    )
    (net (code "39") (name "HDMI_S0") (class "Default")
      (node (ref "Q1") (pin "3") (pinfunction "D_3") (pintype "unspecified"))
      (node (ref "R43") (pin "1") (pinfunction "1_1") (pintype "unspecified"))
      (node (ref "R44") (pin "1") (pinfunction "1_1") (pintype "unspecified"))
      (node (ref "R45") (pin "1") (pinfunction "1_1") (pintype "unspecified"))
      (node (ref "R46") (pin "1") (pinfunction "1_1") (pintype "unspecified"))
      (node (ref "R47") (pin "1") (pinfunction "1_1") (pintype "unspecified"))
      (node (ref "R48") (pin "1") (pinfunction "1_1") (pintype "unspecified"))
      (node (ref "R49") (pin "1") (pinfunction "1_1") (pintype "unspecified"))
      (node (ref "R50") (pin "1") (pinfunction "1_1") (pintype "unspecified"))
    )
    (net (code "40") (name "HDMI_SCL_B") (class "Default")
      (node (ref "U18") (pin "7") (pinfunction "SCL_B_7") (pintype "unspecified"))
      (node (ref "USB3") (pin "15") (pinfunction "SCL_15") (pintype "unspecified"))
    )
    (net (code "41") (name "HDMI_SDA_B") (class "Default")
      (node (ref "U18") (pin "8") (pinfunction "SDA_B_8") (pintype "unspecified"))
      (node (ref "USB3") (pin "16") (pinfunction "SDA_16") (pintype "unspecified"))
    )
    (net (code "42") (name "LED0") (class "Default")
      (node (ref "R21") (pin "2") (pinfunction "2_2") (pintype "input"))
      (node (ref "U8") (pin "30") (pinfunction "LED0/EEDI/SPISI/SDA_30") (pintype "unspecified"))
    )
    (net (code "43") (name "LED2") (class "Default")
      (node (ref "R20") (pin "1") (pinfunction "1_1") (pintype "input"))
      (node (ref "U8") (pin "25") (pinfunction "LED2/EEDO/SPIS0_25") (pintype "unspecified"))
    )
    (net (code "44") (name "LP_CEC_A") (class "Default")
      (node (ref "U18") (pin "24") (pinfunction "CEC_A_24") (pintype "unspecified"))
    )
    (net (code "45") (name "LP_HPD_A") (class "Default")
      (node (ref "U18") (pin "3") (pinfunction "HPD_A_3") (pintype "unspecified"))
    )
    (net (code "46") (name "LP_SCL_A") (class "Default")
      (node (ref "U18") (pin "1") (pinfunction "SCL_A_1") (pintype "unspecified"))
    )
    (net (code "47") (name "LP_SDA_A") (class "Default")
      (node (ref "U18") (pin "2") (pinfunction "SDA_A_2") (pintype "unspecified"))
    )
    (net (code "48") (name "NVME_CLKREQ_N") (class "Default")
      (node (ref "R15") (pin "1") (pinfunction "1_1") (pintype "unspecified"))
      (node (ref "U7") (pin "52") (pinfunction "52_52") (pintype "unspecified"))
    )
    (net (code "49") (name "NVME_CLK_N") (class "Default")
      (node (ref "U7") (pin "53") (pinfunction "53_53") (pintype "unspecified"))
    )
    (net (code "50") (name "NVME_CLK_P") (class "Default")
      (node (ref "U7") (pin "55") (pinfunction "55_55") (pintype "unspecified"))
    )
    (net (code "51") (name "NVME_RST_N") (class "Default")
      (node (ref "C43") (pin "1") (pinfunction "1_1") (pintype "unspecified"))
      (node (ref "R14") (pin "1") (pinfunction "1_1") (pintype "unspecified"))
      (node (ref "U7") (pin "50") (pinfunction "50_50") (pintype "unspecified"))
    )
    (net (code "52") (name "NVME_RX0_N") (class "Default")
      (node (ref "U7") (pin "47") (pinfunction "47_47") (pintype "unspecified"))
    )
    (net (code "53") (name "NVME_RX0_P") (class "Default")
      (node (ref "U7") (pin "49") (pinfunction "49_49") (pintype "unspecified"))
    )
    (net (code "54") (name "NVME_RX1_N") (class "Default")
      (node (ref "U7") (pin "35") (pinfunction "35_35") (pintype "unspecified"))
    )
    (net (code "55") (name "NVME_RX1_P") (class "Default")
      (node (ref "U7") (pin "37") (pinfunction "37_37") (pintype "unspecified"))
    )
    (net (code "56") (name "NVME_RX2_N") (class "Default")
      (node (ref "U7") (pin "23") (pinfunction "23_23") (pintype "unspecified"))
    )
    (net (code "57") (name "NVME_RX2_P") (class "Default")
      (node (ref "U7") (pin "25") (pinfunction "25_25") (pintype "unspecified"))
    )
    (net (code "58") (name "NVME_RX3_N") (class "Default")
      (node (ref "U7") (pin "11") (pinfunction "11_11") (pintype "unspecified"))
    )
    (net (code "59") (name "NVME_RX3_P") (class "Default")
      (node (ref "U7") (pin "13") (pinfunction "13_13") (pintype "unspecified"))
    )
    (net (code "60") (name "NVME_TX0_N") (class "Default")
      (node (ref "C50") (pin "1") (pinfunction "1_1") (pintype "unspecified"))
    )
    (net (code "61") (name "NVME_TX0_P") (class "Default")
      (node (ref "C51") (pin "1") (pinfunction "1_1") (pintype "unspecified"))
    )
    (net (code "62") (name "NVME_TX1_N") (class "Default")
      (node (ref "C48") (pin "1") (pinfunction "1_1") (pintype "unspecified"))
    )
    (net (code "63") (name "NVME_TX1_P") (class "Default")
      (node (ref "C49") (pin "1") (pinfunction "1_1") (pintype "unspecified"))
    )
    (net (code "64") (name "NVME_TX2_N") (class "Default")
      (node (ref "C46") (pin "1") (pinfunction "1_1") (pintype "unspecified"))
    )
    (net (code "65") (name "NVME_TX2_P") (class "Default")
      (node (ref "C47") (pin "1") (pinfunction "1_1") (pintype "unspecified"))
    )
    (net (code "66") (name "NVME_TX3_N") (class "Default")
      (node (ref "C44") (pin "1") (pinfunction "1_1") (pintype "unspecified"))
    )
    (net (code "67") (name "NVME_TX3_P") (class "Default")
      (node (ref "C45") (pin "1") (pinfunction "1_1") (pintype "unspecified"))
    )
    (net (code "68") (name "NVME_WAKE_N") (class "Default")
      (node (ref "R16") (pin "1") (pinfunction "1_1") (pintype "unspecified"))
      (node (ref "U7") (pin "54") (pinfunction "54_54") (pintype "unspecified"))
    )
    (net (code "69") (name "Net-(C1-Pad1)") (class "Default")
      (node (ref "C1") (pin "1") (pinfunction "1_1") (pintype "unspecified"))
      (node (ref "R2") (pin "2") (pinfunction "2_2") (pintype "unspecified"))
    )
    (net (code "70") (name "Net-(C8-Pad1)") (class "Default")
      (node (ref "C8") (pin "1") (pinfunction "1_1") (pintype "unspecified"))
      (node (ref "R5") (pin "2") (pinfunction "2_2") (pintype "input"))
    )
    (net (code "71") (name "Net-(C33-Pad1)") (class "Default")
      (node (ref "C33") (pin "1") (pinfunction "1_1") (pintype "unspecified"))
      (node (ref "U6") (pin "41") (pinfunction "41_41") (pintype "unspecified"))
    )
    (net (code "72") (name "Net-(C34-Pad1)") (class "Default")
      (node (ref "C34") (pin "1") (pinfunction "1_1") (pintype "unspecified"))
      (node (ref "U6") (pin "43") (pinfunction "43_43") (pintype "unspecified"))
    )
    (net (code "73") (name "Net-(C38-Pad1)") (class "Default")
      (node (ref "C38") (pin "1") (pinfunction "1_1") (pintype "input"))
      (node (ref "U7") (pin "2") (pinfunction "2_2") (pintype "unspecified"))
    )
    (net (code "74") (name "Net-(C39-Pad1)") (class "Default")
      (node (ref "C39") (pin "1") (pinfunction "1_1") (pintype "input"))
      (node (ref "U7") (pin "4") (pinfunction "4_4") (pintype "unspecified"))
    )
    (net (code "75") (name "Net-(C40-Pad1)") (class "Default")
      (node (ref "C40") (pin "1") (pinfunction "1_1") (pintype "input"))
      (node (ref "U7") (pin "70") (pinfunction "70_70") (pintype "unspecified"))
    )
    (net (code "76") (name "Net-(C41-Pad1)") (class "Default")
      (node (ref "C41") (pin "1") (pinfunction "1_1") (pintype "input"))
      (node (ref "U7") (pin "72") (pinfunction "72_72") (pintype "unspecified"))
    )
    (net (code "77") (name "Net-(C42-Pad1)") (class "Default")
      (node (ref "C42") (pin "1") (pinfunction "1_1") (pintype "input"))
      (node (ref "U7") (pin "74") (pinfunction "74_74") (pintype "unspecified"))
    )
    (net (code "78") (name "Net-(C44-Pad2)") (class "Default")
      (node (ref "C44") (pin "2") (pinfunction "2_2") (pintype "unspecified"))
      (node (ref "U7") (pin "5") (pinfunction "5_5") (pintype "unspecified"))
    )
    (net (code "79") (name "Net-(C45-Pad2)") (class "Default")
      (node (ref "C45") (pin "2") (pinfunction "2_2") (pintype "unspecified"))
      (node (ref "U7") (pin "7") (pinfunction "7_7") (pintype "unspecified"))
    )
    (net (code "80") (name "Net-(C46-Pad2)") (class "Default")
      (node (ref "C46") (pin "2") (pinfunction "2_2") (pintype "unspecified"))
      (node (ref "U7") (pin "17") (pinfunction "17_17") (pintype "unspecified"))
    )
    (net (code "81") (name "Net-(C47-Pad2)") (class "Default")
      (node (ref "C47") (pin "2") (pinfunction "2_2") (pintype "unspecified"))
      (node (ref "U7") (pin "19") (pinfunction "19_19") (pintype "unspecified"))
    )
    (net (code "82") (name "Net-(C48-Pad2)") (class "Default")
      (node (ref "C48") (pin "2") (pinfunction "2_2") (pintype "unspecified"))
      (node (ref "U7") (pin "29") (pinfunction "29_29") (pintype "unspecified"))
    )
    (net (code "83") (name "Net-(C49-Pad2)") (class "Default")
      (node (ref "C49") (pin "2") (pinfunction "2_2") (pintype "unspecified"))
      (node (ref "U7") (pin "31") (pinfunction "31_31") (pintype "unspecified"))
    )
    (net (code "84") (name "Net-(C50-Pad2)") (class "Default")
      (node (ref "C50") (pin "2") (pinfunction "2_2") (pintype "unspecified"))
      (node (ref "U7") (pin "41") (pinfunction "41_41") (pintype "unspecified"))
    )
    (net (code "85") (name "Net-(C51-Pad2)") (class "Default")
      (node (ref "C51") (pin "2") (pinfunction "2_2") (pintype "unspecified"))
      (node (ref "U7") (pin "43") (pinfunction "43_43") (pintype "unspecified"))
    )
    (net (code "86") (name "Net-(C93-Pad1)") (class "Default")
      (node (ref "C93") (pin "1") (pinfunction "1_1") (pintype "unspecified"))
      (node (ref "U10") (pin "46") (pinfunction "VDD10_46") (pintype "unspecified"))
    )
    (net (code "87") (name "Net-(C111-Pad1)") (class "Default")
      (node (ref "C111") (pin "1") (pinfunction "1_1") (pintype "unspecified"))
      (node (ref "C112") (pin "2") (pinfunction "2_2") (pintype "unspecified"))
      (node (ref "C114") (pin "1") (pinfunction "1_1") (pintype "unspecified"))
      (node (ref "C115") (pin "2") (pinfunction "2_2") (pintype "unspecified"))
      (node (ref "U18") (pin "13") (pinfunction "GND_13") (pintype "unspecified"))
      (node (ref "U18") (pin "18") (pinfunction "GND_18") (pintype "unspecified"))
      (node (ref "U18") (pin "5") (pinfunction "GND_5") (pintype "unspecified"))
    )
    (net (code "88") (name "Net-(CN1-P7)") (class "Default")
      (node (ref "C15") (pin "1") (pinfunction "1_1") (pintype "unspecified"))
      (node (ref "CN1") (pin "14") (pinfunction "P7_14") (pintype "unspecified"))
    )
    (net (code "89") (name "Net-(CN1-P8)") (class "Default")
      (node (ref "C14") (pin "1") (pinfunction "1_1") (pintype "unspecified"))
      (node (ref "CN1") (pin "15") (pinfunction "P8_15") (pintype "unspecified"))
    )
    (net (code "90") (name "Net-(CN1-P9)") (class "Default")
      (node (ref "C13") (pin "1") (pinfunction "1_1") (pintype "unspecified"))
      (node (ref "CN1") (pin "16") (pinfunction "P9_16") (pintype "unspecified"))
    )
    (net (code "91") (name "Net-(CN1-S2)") (class "Default")
      (node (ref "C19") (pin "1") (pinfunction "1_1") (pintype "unspecified"))
      (node (ref "CN1") (pin "2") (pinfunction "S2_2") (pintype "unspecified"))
    )
    (net (code "92") (name "Net-(CN1-S3)") (class "Default")
      (node (ref "C18") (pin "1") (pinfunction "1_1") (pintype "unspecified"))
      (node (ref "CN1") (pin "3") (pinfunction "S3_3") (pintype "unspecified"))
    )
    (net (code "93") (name "Net-(CN1-S5)") (class "Default")
      (node (ref "C17") (pin "1") (pinfunction "1_1") (pintype "unspecified"))
      (node (ref "CN1") (pin "5") (pinfunction "S5_5") (pintype "unspecified"))
    )
    (net (code "94") (name "Net-(CN1-S6)") (class "Default")
      (node (ref "C16") (pin "1") (pinfunction "1_1") (pintype "unspecified"))
      (node (ref "CN1") (pin "6") (pinfunction "S6_6") (pintype "unspecified"))
    )
    (net (code "95") (name "Net-(CN2-P7)") (class "Default")
      (node (ref "C24") (pin "1") (pinfunction "1_1") (pintype "unspecified"))
      (node (ref "CN2") (pin "14") (pinfunction "P7_14") (pintype "unspecified"))
    )
    (net (code "96") (name "Net-(CN2-P8)") (class "Default")
      (node (ref "C25") (pin "1") (pinfunction "1_1") (pintype "unspecified"))
      (node (ref "CN2") (pin "15") (pinfunction "P8_15") (pintype "unspecified"))
    )
    (net (code "97") (name "Net-(CN2-P9)") (class "Default")
      (node (ref "C26") (pin "1") (pinfunction "1_1") (pintype "unspecified"))
      (node (ref "CN2") (pin "16") (pinfunction "P9_16") (pintype "unspecified"))
    )
    (net (code "98") (name "Net-(CN2-S2)") (class "Default")
      (node (ref "C23") (pin "1") (pinfunction "1_1") (pintype "unspecified"))
      (node (ref "CN2") (pin "2") (pinfunction "S2_2") (pintype "unspecified"))
    )
    (net (code "99") (name "Net-(CN2-S3)") (class "Default")
      (node (ref "C22") (pin "1") (pinfunction "1_1") (pintype "unspecified"))
      (node (ref "CN2") (pin "3") (pinfunction "S3_3") (pintype "unspecified"))
    )
    (net (code "100") (name "Net-(CN2-S5)") (class "Default")
      (node (ref "C21") (pin "1") (pinfunction "1_1") (pintype "unspecified"))
      (node (ref "CN2") (pin "5") (pinfunction "S5_5") (pintype "unspecified"))
    )
    (net (code "101") (name "Net-(CN2-S6)") (class "Default")
      (node (ref "C20") (pin "1") (pinfunction "1_1") (pintype "unspecified"))
      (node (ref "CN2") (pin "6") (pinfunction "S6_6") (pintype "unspecified"))
    )
    (net (code "102") (name "Net-(D1-Pad4)") (class "Default")
      (node (ref "D1") (pin "4") (pinfunction "4_4") (pintype "input"))
      (node (ref "USB1") (pin "2") (pinfunction "D-_2") (pintype "unspecified"))
    )
    (net (code "103") (name "Net-(D1-Pad6)") (class "Default")
      (node (ref "D1") (pin "6") (pinfunction "6_6") (pintype "input"))
      (node (ref "USB1") (pin "3") (pinfunction "D+_3") (pintype "unspecified"))
    )
    (net (code "104") (name "Net-(D3-Pad4)") (class "Default")
      (node (ref "D3") (pin "4") (pinfunction "4_4") (pintype "input"))
      (node (ref "USB1") (pin "6") (pinfunction "D-_6") (pintype "unspecified"))
    )
    (net (code "105") (name "Net-(D3-Pad6)") (class "Default")
      (node (ref "D3") (pin "6") (pinfunction "6_6") (pintype "input"))
      (node (ref "USB1") (pin "7") (pinfunction "D+_7") (pintype "unspecified"))
    )
    (net (code "106") (name "Net-(D4-Pad4)") (class "Default")
      (node (ref "D4") (pin "4") (pinfunction "4_4") (pintype "input"))
      (node (ref "USB2") (pin "2") (pinfunction "D-_2") (pintype "unspecified"))
    )
    (net (code "107") (name "Net-(D4-Pad6)") (class "Default")
      (node (ref "D4") (pin "6") (pinfunction "6_6") (pintype "input"))
      (node (ref "USB2") (pin "3") (pinfunction "D+_3") (pintype "unspecified"))
    )
    (net (code "108") (name "Net-(D5-Pad4)") (class "Default")
      (node (ref "D5") (pin "4") (pinfunction "4_4") (pintype "input"))
      (node (ref "USB2") (pin "6") (pinfunction "D-_6") (pintype "unspecified"))
    )
    (net (code "109") (name "Net-(D5-Pad6)") (class "Default")
      (node (ref "D5") (pin "6") (pinfunction "6_6") (pintype "input"))
      (node (ref "USB2") (pin "7") (pinfunction "D+_7") (pintype "unspecified"))
    )
    (net (code "110") (name "Net-(L5-Pad1)") (class "Default")
      (node (ref "L5") (pin "1") (pinfunction "1_1") (pintype "unspecified"))
      (node (ref "USB3") (pin "20") (pinfunction "GND_20") (pintype "unspecified"))
      (node (ref "USB3") (pin "21") (pinfunction "GND_21") (pintype "unspecified"))
      (node (ref "USB3") (pin "22") (pinfunction "GND_22") (pintype "unspecified"))
      (node (ref "USB3") (pin "23") (pinfunction "GND_23") (pintype "unspecified"))
    )
    (net (code "111") (name "Net-(RJ1-LED_G-O+)") (class "Default")
      (node (ref "R20") (pin "2") (pinfunction "2_2") (pintype "input"))
      (node (ref "RJ1") (pin "L1") (pinfunction "LED_G-O+_L1") (pintype "unspecified"))
    )
    (net (code "112") (name "Net-(RJ1-LED_Y-)") (class "Default")
      (node (ref "R21") (pin "1") (pinfunction "1_1") (pintype "input"))
      (node (ref "RJ1") (pin "L3") (pinfunction "LED_Y-_L3") (pintype "unspecified"))
    )
    (net (code "113") (name "Net-(U1-BST)") (class "Default")
      (node (ref "C2") (pin "1") (pinfunction "1_1") (pintype "unspecified"))
      (node (ref "U1") (pin "1") (pinfunction "BST_1") (pintype "unspecified"))
    )
    (net (code "114") (name "Net-(U1-COMP)") (class "Default")
      (node (ref "R2") (pin "1") (pinfunction "1_1") (pintype "unspecified"))
      (node (ref "U1") (pin "6") (pinfunction "COMP_6") (pintype "unspecified"))
    )
    (net (code "115") (name "Net-(U1-EN)") (class "Default")
      (node (ref "R1") (pin "2") (pinfunction "2_2") (pintype "unspecified"))
      (node (ref "U1") (pin "3") (pinfunction "EN_3") (pintype "unspecified"))
    )
    (net (code "116") (name "Net-(U1-FB)") (class "Default")
      (node (ref "R3") (pin "2") (pinfunction "2_2") (pintype "unspecified"))
      (node (ref "R4") (pin "2") (pinfunction "2_2") (pintype "unspecified"))
      (node (ref "U1") (pin "5") (pinfunction "FB_5") (pintype "unspecified"))
    )
    (net (code "117") (name "Net-(U1-RT{slash}CLK)") (class "Default")
      (node (ref "R6") (pin "2") (pinfunction "2_2") (pintype "unspecified"))
      (node (ref "U1") (pin "4") (pinfunction "RT/CLK_4") (pintype "unspecified"))
    )
    (net (code "118") (name "Net-(U1-SW)") (class "Default")
      (node (ref "C2") (pin "2") (pinfunction "2_2") (pintype "unspecified"))
      (node (ref "U1") (pin "8") (pinfunction "SW_8") (pintype "unspecified"))
      (node (ref "U2") (pin "1") (pinfunction "1_1") (pintype "unspecified"))
    )
    (net (code "119") (name "Net-(U5-BST)") (class "Default")
      (node (ref "C7") (pin "1") (pinfunction "1_1") (pintype "unspecified"))
      (node (ref "U5") (pin "1") (pinfunction "BST_1") (pintype "unspecified"))
    )
    (net (code "120") (name "Net-(U5-COMP)") (class "Default")
      (node (ref "R5") (pin "1") (pinfunction "1_1") (pintype "input"))
      (node (ref "U5") (pin "6") (pinfunction "COMP_6") (pintype "unspecified"))
    )
    (net (code "121") (name "Net-(U5-EN)") (class "Default")
      (node (ref "R11") (pin "2") (pinfunction "2_2") (pintype "unspecified"))
      (node (ref "U5") (pin "3") (pinfunction "EN_3") (pintype "unspecified"))
    )
    (net (code "122") (name "Net-(U5-FB)") (class "Default")
      (node (ref "R8") (pin "2") (pinfunction "2_2") (pintype "unspecified"))
      (node (ref "U3") (pin "1") (pinfunction "1_1") (pintype "unspecified"))
      (node (ref "U5") (pin "5") (pinfunction "FB_5") (pintype "unspecified"))
    )
    (net (code "123") (name "Net-(U5-RT{slash}CLK)") (class "Default")
      (node (ref "R7") (pin "2") (pinfunction "2_2") (pintype "unspecified"))
      (node (ref "U5") (pin "4") (pinfunction "RT/CLK_4") (pintype "unspecified"))
    )
    (net (code "124") (name "Net-(U5-SW)") (class "Default")
      (node (ref "C7") (pin "2") (pinfunction "2_2") (pintype "unspecified"))
      (node (ref "U4") (pin "1") (pinfunction "1_1") (pintype "unspecified"))
      (node (ref "U5") (pin "8") (pinfunction "SW_8") (pintype "unspecified"))
    )
    (net (code "125") (name "Net-(U8-HSON)") (class "Default")
      (node (ref "C56") (pin "1") (pinfunction "1_1") (pintype "unspecified"))
      (node (ref "U8") (pin "39") (pinfunction "HSON_39") (pintype "unspecified"))
    )
    (net (code "126") (name "Net-(U8-HSOP)") (class "Default")
      (node (ref "C57") (pin "1") (pinfunction "1_1") (pintype "unspecified"))
      (node (ref "U8") (pin "38") (pinfunction "HSOP_38") (pintype "unspecified"))
    )
    (net (code "127") (name "Net-(U8-ISOLATEB)") (class "Default")
      (node (ref "R18") (pin "1") (pinfunction "1_1") (pintype "input"))
      (node (ref "U8") (pin "1") (pinfunction "ISOLATEB_1") (pintype "unspecified"))
    )
    (net (code "128") (name "Net-(U8-LED1{slash}EESK{slash}SPISC)") (class "Default")
      (node (ref "R22") (pin "1") (pinfunction "1_1") (pintype "input"))
      (node (ref "U8") (pin "27") (pinfunction "LED1/EESK/SPISC_27") (pintype "unspecified"))
    )
    (net (code "129") (name "Net-(U8-RSET)") (class "Default")
      (node (ref "R23") (pin "2") (pinfunction "2_2") (pintype "unspecified"))
      (node (ref "U8") (pin "12") (pinfunction "RSET_12") (pintype "unspecified"))
    )
    (net (code "130") (name "Net-(U9-FB)") (class "Default")
      (node (ref "R24") (pin "1") (pinfunction "1_1") (pintype "unspecified"))
      (node (ref "R25") (pin "1") (pinfunction "1_1") (pintype "unspecified"))
      (node (ref "U9") (pin "1") (pinfunction "FB_1") (pintype "unspecified"))
    )
    (net (code "131") (name "Net-(U9-SW)") (class "Default")
      (node (ref "L3") (pin "1") (pinfunction "1_1") (pintype "unspecified"))
      (node (ref "U9") (pin "4") (pinfunction "SW_4") (pintype "unspecified"))
    )
    (net (code "132") (name "Net-(U10-PETXN)") (class "Default")
      (node (ref "C84") (pin "2") (pinfunction "2_2") (pintype "unspecified"))
      (node (ref "U10") (pin "8") (pinfunction "PETXN_8") (pintype "unspecified"))
    )
    (net (code "133") (name "Net-(U10-PETXP)") (class "Default")
      (node (ref "C83") (pin "2") (pinfunction "2_2") (pintype "unspecified"))
      (node (ref "U10") (pin "7") (pinfunction "PETXP_7") (pintype "unspecified"))
    )
    (net (code "134") (name "Net-(U10-RREF)") (class "Default")
      (node (ref "R33") (pin "1") (pinfunction "1_1") (pintype "unspecified"))
      (node (ref "U10") (pin "33") (pinfunction "RREF_33") (pintype "unspecified"))
    )
    (net (code "135") (name "Net-(U10-SMIB)") (class "Default")
      (node (ref "R32") (pin "1") (pinfunction "1_1") (pintype "unspecified"))
      (node (ref "U10") (pin "1") (pinfunction "SMIB_1") (pintype "unspecified"))
    )
    (net (code "136") (name "Net-(U10-SPICSB)") (class "Default")
      (node (ref "R35") (pin "1") (pinfunction "1_1") (pintype "unspecified"))
      (node (ref "U10") (pin "17") (pinfunction "SPICSB_17") (pintype "unspecified"))
      (node (ref "U16") (pin "1") (pinfunction "CS#_1") (pintype "unspecified"))
    )
    (net (code "137") (name "Net-(U10-SPISCK)") (class "Default")
      (node (ref "R36") (pin "1") (pinfunction "1_1") (pintype "unspecified"))
      (node (ref "U10") (pin "18") (pinfunction "SPISCK_18") (pintype "unspecified"))
      (node (ref "U16") (pin "6") (pinfunction "CLK_6") (pintype "unspecified"))
    )
    (net (code "138") (name "Net-(U10-SPISI)") (class "Default")
      (node (ref "R37") (pin "1") (pinfunction "1_1") (pintype "unspecified"))
      (node (ref "U10") (pin "19") (pinfunction "SPISI_19") (pintype "unspecified"))
      (node (ref "U16") (pin "5") (pinfunction "DI(IO0)_5") (pintype "unspecified"))
    )
    (net (code "139") (name "Net-(U10-SPISO)") (class "Default")
      (node (ref "R34") (pin "1") (pinfunction "1_1") (pintype "unspecified"))
      (node (ref "U10") (pin "16") (pinfunction "SPISO_16") (pintype "unspecified"))
      (node (ref "U16") (pin "2") (pinfunction "DO(IO1)_2") (pintype "unspecified"))
    )
    (net (code "140") (name "Net-(U10-U3TXDN1)") (class "Default")
      (node (ref "C105") (pin "1") (pinfunction "1_1") (pintype "unspecified"))
      (node (ref "U10") (pin "36") (pinfunction "U3TXDN1_36") (pintype "unspecified"))
    )
    (net (code "141") (name "Net-(U10-U3TXDN2)") (class "Default")
      (node (ref "C108") (pin "1") (pinfunction "1_1") (pintype "unspecified"))
      (node (ref "U10") (pin "45") (pinfunction "U3TXDN2_45") (pintype "unspecified"))
    )
    (net (code "142") (name "Net-(U10-U3TXDP1)") (class "Default")
      (node (ref "C106") (pin "1") (pinfunction "1_1") (pintype "unspecified"))
      (node (ref "U10") (pin "35") (pinfunction "U3TXDP1_35") (pintype "unspecified"))
    )
    (net (code "143") (name "Net-(U10-U3TXDP2)") (class "Default")
      (node (ref "C107") (pin "1") (pinfunction "1_1") (pintype "unspecified"))
      (node (ref "U10") (pin "44") (pinfunction "U3TXDP2_44") (pintype "unspecified"))
    )
    (net (code "144") (name "Net-(U10-XT1)") (class "Default")
      (node (ref "C86") (pin "2") (pinfunction "2_2") (pintype "unspecified"))
      (node (ref "U10") (pin "31") (pinfunction "XT1_31") (pintype "unspecified"))
      (node (ref "X2") (pin "2") (pinfunction "OSC2_2") (pintype "input"))
    )
    (net (code "145") (name "Net-(U10-XT2)") (class "Default")
      (node (ref "C85") (pin "2") (pinfunction "2_2") (pintype "unspecified"))
      (node (ref "U10") (pin "30") (pinfunction "XT2_30") (pintype "unspecified"))
      (node (ref "X2") (pin "1") (pinfunction "OSC1_1") (pintype "input"))
    )
    (net (code "146") (name "Net-(U11-D+)") (class "Default")
      (node (ref "D6") (pin "3") (pinfunction "3_3") (pintype "input"))
      (node (ref "U11") (pin "3") (pinfunction "D+_3") (pintype "unspecified"))
    )
    (net (code "147") (name "Net-(U11-D-)") (class "Default")
      (node (ref "D6") (pin "1") (pinfunction "1_1") (pintype "input"))
      (node (ref "U11") (pin "2") (pinfunction "D-_2") (pintype "unspecified"))
    )
    (net (code "148") (name "Net-(U11-GND)") (class "Default")
      (node (ref "D2") (pin "2") (pinfunction "2_2") (pintype "input"))
      (node (ref "D6") (pin "2") (pinfunction "2_2") (pintype "input"))
      (node (ref "U11") (pin "10") (pinfunction "EH_10") (pintype "unspecified"))
      (node (ref "U11") (pin "11") (pinfunction "EH_11") (pintype "unspecified"))
      (node (ref "U11") (pin "4") (pinfunction "GND_4") (pintype "unspecified"))
      (node (ref "U11") (pin "7") (pinfunction "GND_DRAIN_7") (pintype "unspecified"))
    )
    (net (code "149") (name "Net-(U11-VBUS)") (class "Default")
      (node (ref "D2") (pin "5") (pinfunction "5_5") (pintype "input"))
      (node (ref "D6") (pin "5") (pinfunction "5_5") (pintype "input"))
      (node (ref "U11") (pin "1") (pinfunction "VBUS_1") (pintype "unspecified"))
      (node (ref "U13") (pin "7") (pinfunction "OUT1_7") (pintype "unspecified"))
    )
    (net (code "150") (name "Net-(U12-D+)") (class "Default")
      (node (ref "D7") (pin "3") (pinfunction "3_3") (pintype "input"))
      (node (ref "U12") (pin "3") (pinfunction "D+_3") (pintype "unspecified"))
    )
    (net (code "151") (name "Net-(U12-D-)") (class "Default")
      (node (ref "D7") (pin "1") (pinfunction "1_1") (pintype "input"))
      (node (ref "U12") (pin "2") (pinfunction "D-_2") (pintype "unspecified"))
    )
    (net (code "152") (name "Net-(U12-GND)") (class "Default")
      (node (ref "D7") (pin "2") (pinfunction "2_2") (pintype "input"))
      (node (ref "D8") (pin "2") (pinfunction "2_2") (pintype "input"))
      (node (ref "U12") (pin "10") (pinfunction "EH_10") (pintype "unspecified"))
      (node (ref "U12") (pin "11") (pinfunction "EH_11") (pintype "unspecified"))
      (node (ref "U12") (pin "4") (pinfunction "GND_4") (pintype "unspecified"))
      (node (ref "U12") (pin "7") (pinfunction "GND_DRAIN_7") (pintype "unspecified"))
    )
    (net (code "153") (name "Net-(U12-VBUS)") (class "Default")
      (node (ref "D7") (pin "5") (pinfunction "5_5") (pintype "input"))
      (node (ref "D8") (pin "5") (pinfunction "5_5") (pintype "input"))
      (node (ref "U12") (pin "1") (pinfunction "VBUS_1") (pintype "unspecified"))
      (node (ref "U13") (pin "6") (pinfunction "OUT2_6") (pintype "unspecified"))
    )
    (net (code "154") (name "Net-(U14-EN1#†)") (class "Default")
      (node (ref "R28") (pin "2") (pinfunction "2_2") (pintype "unspecified"))
      (node (ref "U14") (pin "3") (pinfunction "EN1#†_3") (pintype "input"))
      (node (ref "U14") (pin "4") (pinfunction "EN2#†_4") (pintype "input"))
    )
    (net (code "155") (name "Net-(U14-OC1#)") (class "Default")
      (node (ref "R26") (pin "1") (pinfunction "1_1") (pintype "unspecified"))
      (node (ref "U14") (pin "8") (pinfunction "OC1#_8") (pintype "output"))
    )
    (net (code "156") (name "Net-(U14-OC2#)") (class "Default")
      (node (ref "R27") (pin "1") (pinfunction "1_1") (pintype "unspecified"))
      (node (ref "U14") (pin "5") (pinfunction "OC2#_5") (pintype "output"))
    )
    (net (code "157") (name "Net-(U15-EN1#†)") (class "Default")
      (node (ref "R29") (pin "2") (pinfunction "2_2") (pintype "unspecified"))
      (node (ref "U15") (pin "3") (pinfunction "EN1#†_3") (pintype "input"))
      (node (ref "U15") (pin "4") (pinfunction "EN2#†_4") (pintype "input"))
    )
    (net (code "158") (name "Net-(U15-OC1#)") (class "Default")
      (node (ref "R30") (pin "1") (pinfunction "1_1") (pintype "unspecified"))
      (node (ref "U15") (pin "8") (pinfunction "OC1#_8") (pintype "output"))
    )
    (net (code "159") (name "Net-(U15-OC2#)") (class "Default")
      (node (ref "R31") (pin "1") (pinfunction "1_1") (pintype "unspecified"))
      (node (ref "U15") (pin "5") (pinfunction "OC2#_5") (pintype "output"))
    )
    (net (code "160") (name "Net-(U16-HOLD#(IO3))") (class "Default")
      (node (ref "R41") (pin "1") (pinfunction "1_1") (pintype "unspecified"))
      (node (ref "U16") (pin "7") (pinfunction "HOLD#(IO3)_7") (pintype "unspecified"))
    )
    (net (code "161") (name "Net-(U16-WP#(IO2))") (class "Default")
      (node (ref "R42") (pin "1") (pinfunction "1_1") (pintype "unspecified"))
      (node (ref "U16") (pin "3") (pinfunction "WP#(IO2)_3") (pintype "unspecified"))
    )
    (net (code "162") (name "Net-(U17-FB)") (class "Default")
      (node (ref "R38") (pin "1") (pinfunction "1_1") (pintype "unspecified"))
      (node (ref "R39") (pin "1") (pinfunction "1_1") (pintype "input"))
      (node (ref "U17") (pin "1") (pinfunction "FB_1") (pintype "unspecified"))
    )
    (net (code "163") (name "Net-(U17-SW)") (class "Default")
      (node (ref "L4") (pin "1") (pinfunction "1_1") (pintype "unspecified"))
      (node (ref "U17") (pin "4") (pinfunction "SW_4") (pintype "unspecified"))
    )
    (net (code "164") (name "Net-(U18-CLK+)") (class "Default")
      (node (ref "C122") (pin "2") (pinfunction "2_2") (pintype "unspecified"))
      (node (ref "R49") (pin "2") (pinfunction "2_2") (pintype "unspecified"))
      (node (ref "U18") (pin "15") (pinfunction "CLK+_15") (pintype "unspecified"))
    )
    (net (code "165") (name "Net-(U18-CLK-)") (class "Default")
      (node (ref "C123") (pin "2") (pinfunction "2_2") (pintype "unspecified"))
      (node (ref "R50") (pin "2") (pinfunction "2_2") (pintype "unspecified"))
      (node (ref "U18") (pin "14") (pinfunction "CLK-_14") (pintype "unspecified"))
    )
    (net (code "166") (name "Net-(U18-CT_HPD)") (class "Default")
      (node (ref "C115") (pin "1") (pinfunction "1_1") (pintype "unspecified"))
      (node (ref "U18") (pin "11") (pinfunction "CT_HPD_11") (pintype "unspecified"))
    )
    (net (code "167") (name "Net-(U18-D0+)") (class "Default")
      (node (ref "C120") (pin "2") (pinfunction "2_2") (pintype "unspecified"))
      (node (ref "R47") (pin "2") (pinfunction "2_2") (pintype "unspecified"))
      (node (ref "U18") (pin "17") (pinfunction "D0+_17") (pintype "unspecified"))
    )
    (net (code "168") (name "Net-(U18-D0-)") (class "Default")
      (node (ref "C121") (pin "2") (pinfunction "2_2") (pintype "unspecified"))
      (node (ref "R48") (pin "2") (pinfunction "2_2") (pintype "unspecified"))
      (node (ref "U18") (pin "16") (pinfunction "D0-_16") (pintype "unspecified"))
    )
    (net (code "169") (name "Net-(U18-D1+)") (class "Default")
      (node (ref "C118") (pin "2") (pinfunction "2_2") (pintype "unspecified"))
      (node (ref "R45") (pin "2") (pinfunction "2_2") (pintype "unspecified"))
      (node (ref "U18") (pin "20") (pinfunction "D1+_20") (pintype "unspecified"))
    )
    (net (code "170") (name "Net-(U18-D1-)") (class "Default")
      (node (ref "C119") (pin "2") (pinfunction "2_2") (pintype "unspecified"))
      (node (ref "R46") (pin "2") (pinfunction "2_2") (pintype "unspecified"))
      (node (ref "U18") (pin "19") (pinfunction "D1-_19") (pintype "unspecified"))
    )
    (net (code "171") (name "Net-(U18-D2+)") (class "Default")
      (node (ref "C116") (pin "2") (pinfunction "2_2") (pintype "unspecified"))
      (node (ref "R43") (pin "2") (pinfunction "2_2") (pintype "unspecified"))
      (node (ref "U18") (pin "22") (pinfunction "D2+_22") (pintype "unspecified"))
    )
    (net (code "172") (name "Net-(U18-D2-)") (class "Default")
      (node (ref "C117") (pin "2") (pinfunction "2_2") (pintype "unspecified"))
      (node (ref "R44") (pin "2") (pinfunction "2_2") (pintype "unspecified"))
      (node (ref "U18") (pin "21") (pinfunction "D2-_21") (pintype "unspecified"))
    )
    (net (code "173") (name "Net-(X1-GND)") (class "Default")
      (node (ref "C52") (pin "1") (pinfunction "1_1") (pintype "unspecified"))
      (node (ref "X1") (pin "2") (pinfunction "GND_2") (pintype "unspecified"))
    )
    (net (code "174") (name "POWEXT") (class "Default")
      (node (ref "U8") (pin "6") (pinfunction "POW_EXT_SWR_6") (pintype "unspecified"))
      (node (ref "U9") (pin "5") (pinfunction "EN_5") (pintype "unspecified"))
    )
    (net (code "175") (name "S0_STATE_EN") (class "Default")
      (node (ref "Q1") (pin "1") (pinfunction "G_1") (pintype "unspecified"))
      (node (ref "R51") (pin "1") (pinfunction "1_1") (pintype "unspecified"))
    )
    (net (code "176") (name "SATA0_RX_N") (class "Default")
      (node (ref "C17") (pin "2") (pinfunction "2_2") (pintype "unspecified"))
    )
    (net (code "177") (name "SATA0_RX_P") (class "Default")
      (node (ref "C16") (pin "2") (pinfunction "2_2") (pintype "unspecified"))
    )
    (net (code "178") (name "SATA0_TX_N") (class "Default")
      (node (ref "C18") (pin "2") (pinfunction "2_2") (pintype "unspecified"))
    )
    (net (code "179") (name "SATA0_TX_P") (class "Default")
      (node (ref "C19") (pin "2") (pinfunction "2_2") (pintype "unspecified"))
    )
    (net (code "180") (name "SATA1_RX_N") (class "Default")
      (node (ref "C21") (pin "2") (pinfunction "2_2") (pintype "unspecified"))
    )
    (net (code "181") (name "SATA1_RX_P") (class "Default")
      (node (ref "C20") (pin "2") (pinfunction "2_2") (pintype "unspecified"))
    )
    (net (code "182") (name "SATA1_TX_N") (class "Default")
      (node (ref "C22") (pin "2") (pinfunction "2_2") (pintype "unspecified"))
    )
    (net (code "183") (name "SATA1_TX_P") (class "Default")
      (node (ref "C23") (pin "2") (pinfunction "2_2") (pintype "unspecified"))
    )
    (net (code "184") (name "USB1N") (class "Default")
      (node (ref "D1") (pin "3") (pinfunction "3_3") (pintype "input"))
    )
    (net (code "185") (name "USB1P") (class "Default")
      (node (ref "D1") (pin "1") (pinfunction "1_1") (pintype "input"))
    )
    (net (code "186") (name "USB2N") (class "Default")
      (node (ref "D3") (pin "3") (pinfunction "3_3") (pintype "input"))
    )
    (net (code "187") (name "USB2P") (class "Default")
      (node (ref "D3") (pin "1") (pinfunction "1_1") (pintype "input"))
    )
    (net (code "188") (name "USB3DN1") (class "Default")
      (node (ref "D6") (pin "6") (pinfunction "6_6") (pintype "input"))
      (node (ref "U10") (pin "41") (pinfunction "U2DP1_41") (pintype "unspecified"))
    )
    (net (code "189") (name "USB3DN2") (class "Default")
      (node (ref "D7") (pin "6") (pinfunction "6_6") (pintype "input"))
      (node (ref "U10") (pin "50") (pinfunction "U2DP2_50") (pintype "unspecified"))
    )
    (net (code "190") (name "USB3DP1") (class "Default")
      (node (ref "D6") (pin "4") (pinfunction "4_4") (pintype "input"))
      (node (ref "U10") (pin "42") (pinfunction "U2DM1_42") (pintype "unspecified"))
    )
    (net (code "191") (name "USB3DP2") (class "Default")
      (node (ref "D7") (pin "4") (pinfunction "4_4") (pintype "input"))
      (node (ref "U10") (pin "51") (pinfunction "U2DM2_51") (pintype "unspecified"))
    )
    (net (code "192") (name "USB3EN1") (class "Default")
      (node (ref "U10") (pin "27") (pinfunction "PPON1_27") (pintype "unspecified"))
      (node (ref "U13") (pin "3") (pinfunction "EN1/EN1#_3") (pintype "unspecified"))
    )
    (net (code "193") (name "USB3EN2") (class "Default")
      (node (ref "U10") (pin "25") (pinfunction "PPON2_25") (pintype "unspecified"))
      (node (ref "U13") (pin "4") (pinfunction "EN2/EN2#_4") (pintype "unspecified"))
    )
    (net (code "194") (name "USB3FLT1") (class "Default")
      (node (ref "U10") (pin "26") (pinfunction "OCI1B_26") (pintype "unspecified"))
      (node (ref "U13") (pin "8") (pinfunction "FLT1#_8") (pintype "unspecified"))
    )
    (net (code "195") (name "USB3FLT2") (class "Default")
      (node (ref "U10") (pin "24") (pinfunction "OCI2B_24") (pintype "unspecified"))
      (node (ref "U13") (pin "5") (pinfunction "FLT2#_5") (pintype "unspecified"))
    )
    (net (code "196") (name "USB3N") (class "Default")
      (node (ref "D4") (pin "3") (pinfunction "3_3") (pintype "input"))
    )
    (net (code "197") (name "USB3P") (class "Default")
      (node (ref "D4") (pin "1") (pinfunction "1_1") (pintype "input"))
    )
    (net (code "198") (name "USB3RXN1") (class "Default")
      (node (ref "D2") (pin "6") (pinfunction "6_6") (pintype "input"))
      (node (ref "U10") (pin "39") (pinfunction "U3RXDN1_39") (pintype "unspecified"))
      (node (ref "U11") (pin "5") (pinfunction "STDA_SSRX-_5") (pintype "unspecified"))
    )
    (net (code "199") (name "USB3RXN2") (class "Default")
      (node (ref "D8") (pin "6") (pinfunction "6_6") (pintype "input"))
      (node (ref "U10") (pin "48") (pinfunction "U3RXDN2_48") (pintype "unspecified"))
      (node (ref "U12") (pin "5") (pinfunction "STDA_SSRX-_5") (pintype "unspecified"))
    )
    (net (code "200") (name "USB3RXP1") (class "Default")
      (node (ref "D2") (pin "4") (pinfunction "4_4") (pintype "input"))
      (node (ref "U10") (pin "38") (pinfunction "U3RXDP1_38") (pintype "unspecified"))
      (node (ref "U11") (pin "6") (pinfunction "STDA_SSRX+_6") (pintype "unspecified"))
    )
    (net (code "201") (name "USB3RXP2") (class "Default")
      (node (ref "D8") (pin "4") (pinfunction "4_4") (pintype "input"))
      (node (ref "U10") (pin "47") (pinfunction "U3RXDP2_47") (pintype "unspecified"))
      (node (ref "U12") (pin "6") (pinfunction "STDA_SSRX+_6") (pintype "unspecified"))
    )
    (net (code "202") (name "USB3TXN1") (class "Default")
      (node (ref "C105") (pin "2") (pinfunction "2_2") (pintype "unspecified"))
      (node (ref "D2") (pin "3") (pinfunction "3_3") (pintype "input"))
      (node (ref "U11") (pin "8") (pinfunction "STDA_SSTX-_8") (pintype "unspecified"))
    )
    (net (code "203") (name "USB3TXN2") (class "Default")
      (node (ref "C108") (pin "2") (pinfunction "2_2") (pintype "unspecified"))
      (node (ref "D8") (pin "3") (pinfunction "3_3") (pintype "input"))
      (node (ref "U12") (pin "8") (pinfunction "STDA_SSTX-_8") (pintype "unspecified"))
    )
    (net (code "204") (name "USB3TXP1") (class "Default")
      (node (ref "C106") (pin "2") (pinfunction "2_2") (pintype "unspecified"))
      (node (ref "D2") (pin "1") (pinfunction "1_1") (pintype "input"))
      (node (ref "U11") (pin "9") (pinfunction "STDA_SSTX+_9") (pintype "unspecified"))
    )
    (net (code "205") (name "USB3TXP2") (class "Default")
      (node (ref "C107") (pin "2") (pinfunction "2_2") (pintype "unspecified"))
      (node (ref "D8") (pin "1") (pinfunction "1_1") (pintype "input"))
      (node (ref "U12") (pin "9") (pinfunction "STDA_SSTX+_9") (pintype "unspecified"))
    )
    (net (code "206") (name "USB3_CLK_N") (class "Default")
      (node (ref "U10") (pin "5") (pinfunction "PECLKN_5") (pintype "unspecified"))
    )
    (net (code "207") (name "USB3_CLK_P") (class "Default")
      (node (ref "U10") (pin "4") (pinfunction "PECLKP_4") (pintype "unspecified"))
    )
    (net (code "208") (name "USB3_CLK_REQ") (class "Default")
      (node (ref "U10") (pin "13") (pinfunction "PECREQB_13") (pintype "unspecified"))
    )
    (net (code "209") (name "USB3_RST") (class "Default")
      (node (ref "U10") (pin "2") (pinfunction "PERSTB_2") (pintype "unspecified"))
    )
    (net (code "210") (name "USB3_RX_N") (class "Default")
      (node (ref "C84") (pin "1") (pinfunction "1_1") (pintype "unspecified"))
    )
    (net (code "211") (name "USB3_RX_P") (class "Default")
      (node (ref "C83") (pin "1") (pinfunction "1_1") (pintype "unspecified"))
    )
    (net (code "212") (name "USB3_TX_N") (class "Default")
      (node (ref "U10") (pin "11") (pinfunction "PERXN_11") (pintype "unspecified"))
    )
    (net (code "213") (name "USB3_TX_P") (class "Default")
      (node (ref "U10") (pin "10") (pinfunction "PERXP_10") (pintype "unspecified"))
    )
    (net (code "214") (name "USB3_WAKE#") (class "Default")
      (node (ref "U10") (pin "3") (pinfunction "PEWAKEB_3") (pintype "unspecified"))
    )
    (net (code "215") (name "USB4N") (class "Default")
      (node (ref "D5") (pin "3") (pinfunction "3_3") (pintype "input"))
    )
    (net (code "216") (name "USB4P") (class "Default")
      (node (ref "D5") (pin "1") (pinfunction "1_1") (pintype "input"))
    )
    (net (code "217") (name "USB_VBUS_P1") (class "Default")
      (node (ref "C75") (pin "2") (pinfunction "2_2") (pintype "unspecified"))
      (node (ref "C79") (pin "2") (pinfunction "2_2") (pintype "unspecified"))
      (node (ref "D1") (pin "5") (pinfunction "5_5") (pintype "input"))
      (node (ref "U14") (pin "7") (pinfunction "OUT1_7") (pintype "output"))
      (node (ref "USB1") (pin "1") (pinfunction "VBUS_1") (pintype "unspecified"))
    )
    (net (code "218") (name "USB_VBUS_P2") (class "Default")
      (node (ref "C76") (pin "2") (pinfunction "2_2") (pintype "unspecified"))
      (node (ref "C80") (pin "2") (pinfunction "2_2") (pintype "unspecified"))
      (node (ref "D3") (pin "5") (pinfunction "5_5") (pintype "input"))
      (node (ref "U14") (pin "6") (pinfunction "OUT2_6") (pintype "output"))
      (node (ref "USB1") (pin "5") (pinfunction "VBUS_5") (pintype "unspecified"))
    )
    (net (code "219") (name "USB_VBUS_P3") (class "Default")
      (node (ref "C77") (pin "1") (pinfunction "1_1") (pintype "unspecified"))
      (node (ref "C81") (pin "2") (pinfunction "2_2") (pintype "unspecified"))
      (node (ref "D4") (pin "5") (pinfunction "5_5") (pintype "input"))
      (node (ref "U15") (pin "7") (pinfunction "OUT1_7") (pintype "output"))
      (node (ref "USB2") (pin "1") (pinfunction "VBUS_1") (pintype "unspecified"))
    )
    (net (code "220") (name "USB_VBUS_P4") (class "Default")
      (node (ref "C78") (pin "2") (pinfunction "2_2") (pintype "unspecified"))
      (node (ref "C82") (pin "2") (pinfunction "2_2") (pintype "unspecified"))
      (node (ref "D5") (pin "5") (pinfunction "5_5") (pintype "input"))
      (node (ref "U15") (pin "6") (pinfunction "OUT2_6") (pintype "output"))
      (node (ref "USB2") (pin "5") (pinfunction "VBUS_5") (pintype "unspecified"))
    )
    (net (code "221") (name "VCC_ETH") (class "Default")
      (node (ref "C52") (pin "2") (pinfunction "2_2") (pintype "unspecified"))
      (node (ref "C53") (pin "1") (pinfunction "1_1") (pintype "unspecified"))
      (node (ref "C54") (pin "2") (pinfunction "2_2") (pintype "unspecified"))
      (node (ref "C55") (pin "2") (pinfunction "2_2") (pintype "unspecified"))
      (node (ref "C60") (pin "2") (pinfunction "2_2") (pintype "unspecified"))
      (node (ref "C62") (pin "2") (pinfunction "2_2") (pintype "unspecified"))
      (node (ref "C65") (pin "1") (pinfunction "1_1") (pintype "unspecified"))
      (node (ref "C66") (pin "1") (pinfunction "1_1") (pintype "unspecified"))
      (node (ref "C68") (pin "1") (pinfunction "1_1") (pintype "unspecified"))
      (node (ref "C69") (pin "1") (pinfunction "1_1") (pintype "unspecified"))
      (node (ref "C70") (pin "1") (pinfunction "1_1") (pintype "unspecified"))
      (node (ref "L2") (pin "1") (pinfunction "1_1") (pintype "unspecified"))
      (node (ref "R10") (pin "1") (pinfunction "1_1") (pintype "input"))
      (node (ref "R17") (pin "2") (pinfunction "2_2") (pintype "input"))
      (node (ref "R18") (pin "2") (pinfunction "2_2") (pintype "input"))
      (node (ref "R19") (pin "1") (pinfunction "1_1") (pintype "unspecified"))
      (node (ref "R22") (pin "2") (pinfunction "2_2") (pintype "input"))
      (node (ref "RJ1") (pin "L2") (pinfunction "LED_G+O-_L2") (pintype "unspecified"))
      (node (ref "RJ1") (pin "L4") (pinfunction "LED_Y+_L4") (pintype "unspecified"))
      (node (ref "RJ1") (pin "R5") (pinfunction "CT_R5") (pintype "unspecified"))
      (node (ref "RJ1") (pin "R6") (pinfunction "CT_R6") (pintype "unspecified"))
      (node (ref "U8") (pin "15") (pinfunction "AVDD33_15") (pintype "unspecified"))
      (node (ref "U8") (pin "19") (pinfunction "AVDD33_19") (pintype "unspecified"))
      (node (ref "U8") (pin "29") (pinfunction "DVDD33_29") (pintype "unspecified"))
      (node (ref "U8") (pin "33") (pinfunction "AVDD33_33") (pintype "unspecified"))
      (node (ref "U8") (pin "34") (pinfunction "AVDD33_XTAL_34") (pintype "unspecified"))
      (node (ref "U8") (pin "43") (pinfunction "EVDD33_43") (pintype "unspecified"))
      (node (ref "U8") (pin "46") (pinfunction "DVDD33_46") (pintype "unspecified"))
      (node (ref "X1") (pin "1") (pinfunction "ENABLE_CONTROL_1") (pintype "unspecified"))
      (node (ref "X1") (pin "4") (pinfunction "VDD_4") (pintype "unspecified"))
    )
    (net (code "222") (name "WIFI_CLKREQ_N") (class "Default")
      (node (ref "R12") (pin "2") (pinfunction "2_2") (pintype "unspecified"))
      (node (ref "U6") (pin "53") (pinfunction "53_53") (pintype "unspecified"))
    )
    (net (code "223") (name "WIFI_CLK_N") (class "Default")
      (node (ref "U6") (pin "49") (pinfunction "49_49") (pintype "unspecified"))
    )
    (net (code "224") (name "WIFI_CLK_P") (class "Default")
      (node (ref "U6") (pin "47") (pinfunction "47_47") (pintype "unspecified"))
    )
    (net (code "225") (name "WIFI_RST_N") (class "Default")
      (node (ref "C35") (pin "2") (pinfunction "2_2") (pintype "unspecified"))
      (node (ref "R9") (pin "1") (pinfunction "1_1") (pintype "unspecified"))
      (node (ref "U6") (pin "52") (pinfunction "52_52") (pintype "unspecified"))
    )
    (net (code "226") (name "WIFI_RX_N") (class "Default")
      (node (ref "U6") (pin "37") (pinfunction "37_37") (pintype "unspecified"))
    )
    (net (code "227") (name "WIFI_RX_P") (class "Default")
      (node (ref "U6") (pin "35") (pinfunction "35_35") (pintype "unspecified"))
    )
    (net (code "228") (name "WIFI_TX_N") (class "Default")
      (node (ref "C34") (pin "2") (pinfunction "2_2") (pintype "unspecified"))
    )
    (net (code "229") (name "WIFI_TX_P") (class "Default")
      (node (ref "C33") (pin "2") (pinfunction "2_2") (pintype "unspecified"))
    )
    (net (code "230") (name "WIFI_WAKE_N") (class "Default")
      (node (ref "R13") (pin "2") (pinfunction "2_2") (pintype "unspecified"))
      (node (ref "U6") (pin "55") (pinfunction "55_55") (pintype "unspecified"))
    )
    (net (code "231") (name "unconnected-(CN1-P1-Pad8)") (class "Default")
      (node (ref "CN1") (pin "8") (pinfunction "P1_8") (pintype "unspecified+no_connect"))
    )
    (net (code "232") (name "unconnected-(CN1-P2-Pad9)") (class "Default")
      (node (ref "CN1") (pin "9") (pinfunction "P2_9") (pintype "unspecified+no_connect"))
    )
    (net (code "233") (name "unconnected-(CN1-P3-Pad10)") (class "Default")
      (node (ref "CN1") (pin "10") (pinfunction "P3_10") (pintype "unspecified+no_connect"))
    )
    (net (code "234") (name "unconnected-(CN1-P5-Pad22)") (class "Default")
      (node (ref "CN1") (pin "22") (pinfunction "P5_22") (pintype "unspecified+no_connect"))
    )
    (net (code "235") (name "unconnected-(CN1-P13-Pad20)") (class "Default")
      (node (ref "CN1") (pin "20") (pinfunction "P13_20") (pintype "unspecified+no_connect"))
    )
    (net (code "236") (name "unconnected-(CN1-P14-Pad21)") (class "Default")
      (node (ref "CN1") (pin "21") (pinfunction "P14_21") (pintype "unspecified+no_connect"))
    )
    (net (code "237") (name "unconnected-(CN2-P1-Pad8)") (class "Default")
      (node (ref "CN2") (pin "8") (pinfunction "P1_8") (pintype "unspecified+no_connect"))
    )
    (net (code "238") (name "unconnected-(CN2-P2-Pad9)") (class "Default")
      (node (ref "CN2") (pin "9") (pinfunction "P2_9") (pintype "unspecified+no_connect"))
    )
    (net (code "239") (name "unconnected-(CN2-P3-Pad10)") (class "Default")
      (node (ref "CN2") (pin "10") (pinfunction "P3_10") (pintype "unspecified+no_connect"))
    )
    (net (code "240") (name "unconnected-(CN2-P5-Pad22)") (class "Default")
      (node (ref "CN2") (pin "22") (pinfunction "P5_22") (pintype "unspecified+no_connect"))
    )
    (net (code "241") (name "unconnected-(CN2-P13-Pad20)") (class "Default")
      (node (ref "CN2") (pin "20") (pinfunction "P13_20") (pintype "unspecified+no_connect"))
    )
    (net (code "242") (name "unconnected-(CN2-P14-Pad21)") (class "Default")
      (node (ref "CN2") (pin "21") (pinfunction "P14_21") (pintype "unspecified+no_connect"))
    )
    (net (code "243") (name "unconnected-(U6-Pad6)") (class "Default")
      (node (ref "U6") (pin "6") (pinfunction "6_6") (pintype "unspecified+no_connect"))
    )
    (net (code "244") (name "unconnected-(U6-Pad8)") (class "Default")
      (node (ref "U6") (pin "8") (pinfunction "8_8") (pintype "unspecified+no_connect"))
    )
    (net (code "245") (name "unconnected-(U6-Pad9)") (class "Default")
      (node (ref "U6") (pin "9") (pinfunction "9_9") (pintype "unspecified+no_connect"))
    )
    (net (code "246") (name "unconnected-(U6-Pad10)") (class "Default")
      (node (ref "U6") (pin "10") (pinfunction "10_10") (pintype "unspecified+no_connect"))
    )
    (net (code "247") (name "unconnected-(U6-Pad11)") (class "Default")
      (node (ref "U6") (pin "11") (pinfunction "11_11") (pintype "unspecified+no_connect"))
    )
    (net (code "248") (name "unconnected-(U6-Pad12)") (class "Default")
      (node (ref "U6") (pin "12") (pinfunction "12_12") (pintype "unspecified+no_connect"))
    )
    (net (code "249") (name "unconnected-(U6-Pad13)") (class "Default")
      (node (ref "U6") (pin "13") (pinfunction "13_13") (pintype "unspecified+no_connect"))
    )
    (net (code "250") (name "unconnected-(U6-Pad14)") (class "Default")
      (node (ref "U6") (pin "14") (pinfunction "14_14") (pintype "unspecified+no_connect"))
    )
    (net (code "251") (name "unconnected-(U6-Pad15)") (class "Default")
      (node (ref "U6") (pin "15") (pinfunction "15_15") (pintype "unspecified+no_connect"))
    )
    (net (code "252") (name "unconnected-(U6-Pad16)") (class "Default")
      (node (ref "U6") (pin "16") (pinfunction "16_16") (pintype "unspecified+no_connect"))
    )
    (net (code "253") (name "unconnected-(U6-Pad17)") (class "Default")
      (node (ref "U6") (pin "17") (pinfunction "17_17") (pintype "unspecified+no_connect"))
    )
    (net (code "254") (name "unconnected-(U6-Pad18)") (class "Default")
      (node (ref "U6") (pin "18") (pinfunction "18_18") (pintype "unspecified+no_connect"))
    )
    (net (code "255") (name "unconnected-(U6-Pad19)") (class "Default")
      (node (ref "U6") (pin "19") (pinfunction "19_19") (pintype "unspecified+no_connect"))
    )
    (net (code "256") (name "unconnected-(U6-Pad20)") (class "Default")
      (node (ref "U6") (pin "20") (pinfunction "20_20") (pintype "unspecified+no_connect"))
    )
    (net (code "257") (name "unconnected-(U6-Pad21)") (class "Default")
      (node (ref "U6") (pin "21") (pinfunction "21_21") (pintype "unspecified+no_connect"))
    )
    (net (code "258") (name "unconnected-(U6-Pad22)") (class "Default")
      (node (ref "U6") (pin "22") (pinfunction "22_22") (pintype "unspecified+no_connect"))
    )
    (net (code "259") (name "unconnected-(U6-Pad23)") (class "Default")
      (node (ref "U6") (pin "23") (pinfunction "23_23") (pintype "unspecified+no_connect"))
    )
    (net (code "260") (name "unconnected-(U6-Pad32)") (class "Default")
      (node (ref "U6") (pin "32") (pinfunction "32_32") (pintype "unspecified+no_connect"))
    )
    (net (code "261") (name "unconnected-(U6-Pad34)") (class "Default")
      (node (ref "U6") (pin "34") (pinfunction "34_34") (pintype "unspecified+no_connect"))
    )
    (net (code "262") (name "unconnected-(U6-Pad36)") (class "Default")
      (node (ref "U6") (pin "36") (pinfunction "36_36") (pintype "unspecified+no_connect"))
    )
    (net (code "263") (name "unconnected-(U6-Pad38)") (class "Default")
      (node (ref "U6") (pin "38") (pinfunction "38_38") (pintype "unspecified+no_connect"))
    )
    (net (code "264") (name "unconnected-(U6-Pad40)") (class "Default")
      (node (ref "U6") (pin "40") (pinfunction "40_40") (pintype "unspecified+no_connect"))
    )
    (net (code "265") (name "unconnected-(U6-Pad42)") (class "Default")
      (node (ref "U6") (pin "42") (pinfunction "42_42") (pintype "unspecified+no_connect"))
    )
    (net (code "266") (name "unconnected-(U6-Pad44)") (class "Default")
      (node (ref "U6") (pin "44") (pinfunction "44_44") (pintype "unspecified+no_connect"))
    )
    (net (code "267") (name "unconnected-(U6-Pad46)") (class "Default")
      (node (ref "U6") (pin "46") (pinfunction "46_46") (pintype "unspecified+no_connect"))
    )
    (net (code "268") (name "unconnected-(U6-Pad48)") (class "Default")
      (node (ref "U6") (pin "48") (pinfunction "48_48") (pintype "unspecified+no_connect"))
    )
    (net (code "269") (name "unconnected-(U6-Pad50)") (class "Default")
      (node (ref "U6") (pin "50") (pinfunction "50_50") (pintype "unspecified+no_connect"))
    )
    (net (code "270") (name "unconnected-(U6-Pad54)") (class "Default")
      (node (ref "U6") (pin "54") (pinfunction "54_54") (pintype "unspecified+no_connect"))
    )
    (net (code "271") (name "unconnected-(U6-Pad56)") (class "Default")
      (node (ref "U6") (pin "56") (pinfunction "56_56") (pintype "unspecified+no_connect"))
    )
    (net (code "272") (name "unconnected-(U6-Pad58)") (class "Default")
      (node (ref "U6") (pin "58") (pinfunction "58_58") (pintype "unspecified+no_connect"))
    )
    (net (code "273") (name "unconnected-(U6-Pad59)") (class "Default")
      (node (ref "U6") (pin "59") (pinfunction "59_59") (pintype "unspecified+no_connect"))
    )
    (net (code "274") (name "unconnected-(U6-Pad60)") (class "Default")
      (node (ref "U6") (pin "60") (pinfunction "60_60") (pintype "unspecified+no_connect"))
    )
    (net (code "275") (name "unconnected-(U6-Pad61)") (class "Default")
      (node (ref "U6") (pin "61") (pinfunction "61_61") (pintype "unspecified+no_connect"))
    )
    (net (code "276") (name "unconnected-(U6-Pad62)") (class "Default")
      (node (ref "U6") (pin "62") (pinfunction "62_62") (pintype "unspecified+no_connect"))
    )
    (net (code "277") (name "unconnected-(U6-Pad64)") (class "Default")
      (node (ref "U6") (pin "64") (pinfunction "64_64") (pintype "unspecified+no_connect"))
    )
    (net (code "278") (name "unconnected-(U6-Pad65)") (class "Default")
      (node (ref "U6") (pin "65") (pinfunction "65_65") (pintype "unspecified+no_connect"))
    )
    (net (code "279") (name "unconnected-(U6-Pad66)") (class "Default")
      (node (ref "U6") (pin "66") (pinfunction "66_66") (pintype "unspecified+no_connect"))
    )
    (net (code "280") (name "unconnected-(U6-Pad67)") (class "Default")
      (node (ref "U6") (pin "67") (pinfunction "67_67") (pintype "unspecified+no_connect"))
    )
    (net (code "281") (name "unconnected-(U6-Pad68)") (class "Default")
      (node (ref "U6") (pin "68") (pinfunction "68_68") (pintype "unspecified+no_connect"))
    )
    (net (code "282") (name "unconnected-(U6-Pad70)") (class "Default")
      (node (ref "U6") (pin "70") (pinfunction "70_70") (pintype "unspecified+no_connect"))
    )
    (net (code "283") (name "unconnected-(U6-Pad71)") (class "Default")
      (node (ref "U6") (pin "71") (pinfunction "71_71") (pintype "unspecified+no_connect"))
    )
    (net (code "284") (name "unconnected-(U6-Pad73)") (class "Default")
      (node (ref "U6") (pin "73") (pinfunction "73_73") (pintype "unspecified+no_connect"))
    )
    (net (code "285") (name "unconnected-(U7-Pad6)") (class "Default")
      (node (ref "U7") (pin "6") (pinfunction "6_6") (pintype "unspecified+no_connect"))
    )
    (net (code "286") (name "unconnected-(U7-Pad8)") (class "Default")
      (node (ref "U7") (pin "8") (pinfunction "8_8") (pintype "unspecified+no_connect"))
    )
    (net (code "287") (name "unconnected-(U7-Pad10)") (class "Default")
      (node (ref "U7") (pin "10") (pinfunction "10_10") (pintype "unspecified+no_connect"))
    )
    (net (code "288") (name "unconnected-(U7-Pad12)") (class "Default")
      (node (ref "U7") (pin "12") (pinfunction "12_12") (pintype "unspecified+no_connect"))
    )
    (net (code "289") (name "unconnected-(U7-Pad14)") (class "Default")
      (node (ref "U7") (pin "14") (pinfunction "14_14") (pintype "unspecified+no_connect"))
    )
    (net (code "290") (name "unconnected-(U7-Pad16)") (class "Default")
      (node (ref "U7") (pin "16") (pinfunction "16_16") (pintype "unspecified+no_connect"))
    )
    (net (code "291") (name "unconnected-(U7-Pad18)") (class "Default")
      (node (ref "U7") (pin "18") (pinfunction "18_18") (pintype "unspecified+no_connect"))
    )
    (net (code "292") (name "unconnected-(U7-Pad20)") (class "Default")
      (node (ref "U7") (pin "20") (pinfunction "20_20") (pintype "unspecified+no_connect"))
    )
    (net (code "293") (name "unconnected-(U7-Pad22)") (class "Default")
      (node (ref "U7") (pin "22") (pinfunction "22_22") (pintype "unspecified+no_connect"))
    )
    (net (code "294") (name "unconnected-(U7-Pad24)") (class "Default")
      (node (ref "U7") (pin "24") (pinfunction "24_24") (pintype "unspecified+no_connect"))
    )
    (net (code "295") (name "unconnected-(U7-Pad26)") (class "Default")
      (node (ref "U7") (pin "26") (pinfunction "26_26") (pintype "unspecified+no_connect"))
    )
    (net (code "296") (name "unconnected-(U7-Pad28)") (class "Default")
      (node (ref "U7") (pin "28") (pinfunction "28_28") (pintype "unspecified+no_connect"))
    )
    (net (code "297") (name "unconnected-(U7-Pad30)") (class "Default")
      (node (ref "U7") (pin "30") (pinfunction "30_30") (pintype "unspecified+no_connect"))
    )
    (net (code "298") (name "unconnected-(U7-Pad32)") (class "Default")
      (node (ref "U7") (pin "32") (pinfunction "32_32") (pintype "unspecified+no_connect"))
    )
    (net (code "299") (name "unconnected-(U7-Pad34)") (class "Default")
      (node (ref "U7") (pin "34") (pinfunction "34_34") (pintype "unspecified+no_connect"))
    )
    (net (code "300") (name "unconnected-(U7-Pad36)") (class "Default")
      (node (ref "U7") (pin "36") (pinfunction "36_36") (pintype "unspecified+no_connect"))
    )
    (net (code "301") (name "unconnected-(U7-Pad38)") (class "Default")
      (node (ref "U7") (pin "38") (pinfunction "38_38") (pintype "unspecified+no_connect"))
    )
    (net (code "302") (name "unconnected-(U7-Pad40)") (class "Default")
      (node (ref "U7") (pin "40") (pinfunction "40_40") (pintype "unspecified+no_connect"))
    )
    (net (code "303") (name "unconnected-(U7-Pad42)") (class "Default")
      (node (ref "U7") (pin "42") (pinfunction "42_42") (pintype "unspecified+no_connect"))
    )
    (net (code "304") (name "unconnected-(U7-Pad44)") (class "Default")
      (node (ref "U7") (pin "44") (pinfunction "44_44") (pintype "unspecified+no_connect"))
    )
    (net (code "305") (name "unconnected-(U7-Pad46)") (class "Default")
      (node (ref "U7") (pin "46") (pinfunction "46_46") (pintype "unspecified+no_connect"))
    )
    (net (code "306") (name "unconnected-(U7-Pad48)") (class "Default")
      (node (ref "U7") (pin "48") (pinfunction "48_48") (pintype "unspecified+no_connect"))
    )
    (net (code "307") (name "unconnected-(U7-Pad56)") (class "Default")
      (node (ref "U7") (pin "56") (pinfunction "56_56") (pintype "unspecified+no_connect"))
    )
    (net (code "308") (name "unconnected-(U7-Pad58)") (class "Default")
      (node (ref "U7") (pin "58") (pinfunction "58_58") (pintype "unspecified+no_connect"))
    )
    (net (code "309") (name "unconnected-(U7-Pad67)") (class "Default")
      (node (ref "U7") (pin "67") (pinfunction "67_67") (pintype "unspecified+no_connect"))
    )
    (net (code "310") (name "unconnected-(U7-Pad68)") (class "Default")
      (node (ref "U7") (pin "68") (pinfunction "68_68") (pintype "unspecified+no_connect"))
    )
    (net (code "311") (name "unconnected-(U7-Pad69)") (class "Default")
      (node (ref "U7") (pin "69") (pinfunction "69_69") (pintype "unspecified+no_connect"))
    )
    (net (code "312") (name "unconnected-(U8-CKXTAL2-Pad9)") (class "Default")
      (node (ref "U8") (pin "9") (pinfunction "CKXTAL2_9") (pintype "unspecified+no_connect"))
    )
    (net (code "313") (name "unconnected-(U8-EECS{slash}SCL-Pad31)") (class "Default")
      (node (ref "U8") (pin "31") (pinfunction "EECS/SCL_31") (pintype "unspecified+no_connect"))
    )
    (net (code "314") (name "unconnected-(U8-EEPROM_SEL{slash}PPS_PIN-Pad32)") (class "Default")
      (node (ref "U8") (pin "32") (pinfunction "EEPROM_SEL/PPS_PIN_32") (pintype "unspecified+no_connect"))
    )
    (net (code "315") (name "unconnected-(U8-GPI-Pad3)") (class "Default")
      (node (ref "U8") (pin "3") (pinfunction "GPI_3") (pintype "unspecified+no_connect"))
    )
    (net (code "316") (name "unconnected-(U8-LED3-Pad35)") (class "Default")
      (node (ref "U8") (pin "35") (pinfunction "LED3_35") (pintype "unspecified+no_connect"))
    )
    (net (code "317") (name "unconnected-(U8-NC-Pad4)") (class "Default")
      (node (ref "U8") (pin "4") (pinfunction "NC_4") (pintype "unspecified+no_connect"))
    )
    (net (code "318") (name "unconnected-(U8-NC-Pad5)") (class "Default")
      (node (ref "U8") (pin "5") (pinfunction "NC_5") (pintype "unspecified+no_connect"))
    )
    (net (code "319") (name "unconnected-(U8-NC-Pad7)") (class "Default")
      (node (ref "U8") (pin "7") (pinfunction "NC_7") (pintype "unspecified+no_connect"))
    )
    (net (code "320") (name "unconnected-(U8-SPICSB-Pad26)") (class "Default")
      (node (ref "U8") (pin "26") (pinfunction "SPICSB_26") (pintype "unspecified+no_connect"))
    )
    (net (code "321") (name "unconnected-(U9-NC{slash}PG-Pad6)") (class "Default")
      (node (ref "U9") (pin "6") (pinfunction "NC/PG_6") (pintype "unspecified+no_connect"))
    )
    (net (code "322") (name "unconnected-(U10-OCI3B-Pad22)") (class "Default")
      (node (ref "U10") (pin "22") (pinfunction "OCI3B_22") (pintype "unspecified+no_connect"))
    )
    (net (code "323") (name "unconnected-(U10-OCI4B-Pad20)") (class "Default")
      (node (ref "U10") (pin "20") (pinfunction "OCI4B_20") (pintype "unspecified+no_connect"))
    )
    (net (code "324") (name "unconnected-(U10-PPON3-Pad23)") (class "Default")
      (node (ref "U10") (pin "23") (pinfunction "PPON3_23") (pintype "unspecified+no_connect"))
    )
    (net (code "325") (name "unconnected-(U10-PPON4-Pad21)") (class "Default")
      (node (ref "U10") (pin "21") (pinfunction "PPON4_21") (pintype "unspecified+no_connect"))
    )
    (net (code "326") (name "unconnected-(U10-U2DM3-Pad59)") (class "Default")
      (node (ref "U10") (pin "59") (pinfunction "U2DM3_59") (pintype "unspecified+no_connect"))
    )
    (net (code "327") (name "unconnected-(U10-U2DM4-Pad68)") (class "Default")
      (node (ref "U10") (pin "68") (pinfunction "U2DM4_68") (pintype "unspecified+no_connect"))
    )
    (net (code "328") (name "unconnected-(U10-U2DP3-Pad58)") (class "Default")
      (node (ref "U10") (pin "58") (pinfunction "U2DP3_58") (pintype "unspecified+no_connect"))
    )
    (net (code "329") (name "unconnected-(U10-U2DP4-Pad67)") (class "Default")
      (node (ref "U10") (pin "67") (pinfunction "U2DP4_67") (pintype "unspecified+no_connect"))
    )
    (net (code "330") (name "unconnected-(U10-U3RXDN3-Pad56)") (class "Default")
      (node (ref "U10") (pin "56") (pinfunction "U3RXDN3_56") (pintype "unspecified+no_connect"))
    )
    (net (code "331") (name "unconnected-(U10-U3RXDN4-Pad65)") (class "Default")
      (node (ref "U10") (pin "65") (pinfunction "U3RXDN4_65") (pintype "unspecified+no_connect"))
    )
    (net (code "332") (name "unconnected-(U10-U3RXDP3-Pad55)") (class "Default")
      (node (ref "U10") (pin "55") (pinfunction "U3RXDP3_55") (pintype "unspecified+no_connect"))
    )
    (net (code "333") (name "unconnected-(U10-U3RXDP4-Pad64)") (class "Default")
      (node (ref "U10") (pin "64") (pinfunction "U3RXDP4_64") (pintype "unspecified+no_connect"))
    )
    (net (code "334") (name "unconnected-(U10-U3TXDN3-Pad53)") (class "Default")
      (node (ref "U10") (pin "53") (pinfunction "U3TXDN3_53") (pintype "unspecified+no_connect"))
    )
    (net (code "335") (name "unconnected-(U10-U3TXDN4-Pad62)") (class "Default")
      (node (ref "U10") (pin "62") (pinfunction "U3TXDN4_62") (pintype "unspecified+no_connect"))
    )
    (net (code "336") (name "unconnected-(U10-U3TXDP3-Pad52)") (class "Default")
      (node (ref "U10") (pin "52") (pinfunction "U3TXDP3_52") (pintype "unspecified+no_connect"))
    )
    (net (code "337") (name "unconnected-(U10-U3TXDP4-Pad61)") (class "Default")
      (node (ref "U10") (pin "61") (pinfunction "U3TXDP4_61") (pintype "unspecified+no_connect"))
    )
    (net (code "338") (name "unconnected-(U18-LS_OE-Pad4)") (class "Default")
      (node (ref "U18") (pin "4") (pinfunction "LS_OE_4") (pintype "unspecified"))
    )
    (net (code "339") (name "unconnected-(U19-EH-Pad261)") (class "Default")
      (node (ref "U19") (pin "261") (pinfunction "EH_261") (pintype "unspecified"))
    )
    (net (code "340") (name "unconnected-(U19-EH-Pad262)") (class "Default")
      (node (ref "U19") (pin "262") (pinfunction "EH_262") (pintype "unspecified"))
    )
    (net (code "341") (name "unconnected-(U19-Pad1)") (class "Default")
      (node (ref "U19") (pin "1") (pinfunction "1_1") (pintype "unspecified"))
    )
    (net (code "342") (name "unconnected-(U19-Pad2)") (class "Default")
      (node (ref "U19") (pin "2") (pinfunction "2_2") (pintype "unspecified"))
    )
    (net (code "343") (name "unconnected-(U19-Pad3)") (class "Default")
      (node (ref "U19") (pin "3") (pinfunction "3_3") (pintype "unspecified"))
    )
    (net (code "344") (name "unconnected-(U19-Pad4)") (class "Default")
      (node (ref "U19") (pin "4") (pinfunction "4_4") (pintype "unspecified"))
    )
    (net (code "345") (name "unconnected-(U19-Pad5)") (class "Default")
      (node (ref "U19") (pin "5") (pinfunction "5_5") (pintype "unspecified"))
    )
    (net (code "346") (name "unconnected-(U19-Pad6)") (class "Default")
      (node (ref "U19") (pin "6") (pinfunction "6_6") (pintype "unspecified"))
    )
    (net (code "347") (name "unconnected-(U19-Pad7)") (class "Default")
      (node (ref "U19") (pin "7") (pinfunction "7_7") (pintype "unspecified"))
    )
    (net (code "348") (name "unconnected-(U19-Pad8)") (class "Default")
      (node (ref "U19") (pin "8") (pinfunction "8_8") (pintype "unspecified"))
    )
    (net (code "349") (name "unconnected-(U19-Pad9)") (class "Default")
      (node (ref "U19") (pin "9") (pinfunction "9_9") (pintype "unspecified"))
    )
    (net (code "350") (name "unconnected-(U19-Pad10)") (class "Default")
      (node (ref "U19") (pin "10") (pinfunction "10_10") (pintype "unspecified"))
    )
    (net (code "351") (name "unconnected-(U19-Pad11)") (class "Default")
      (node (ref "U19") (pin "11") (pinfunction "11_11") (pintype "unspecified"))
    )
    (net (code "352") (name "unconnected-(U19-Pad12)") (class "Default")
      (node (ref "U19") (pin "12") (pinfunction "12_12") (pintype "unspecified"))
    )
    (net (code "353") (name "unconnected-(U19-Pad13)") (class "Default")
      (node (ref "U19") (pin "13") (pinfunction "13_13") (pintype "unspecified"))
    )
    (net (code "354") (name "unconnected-(U19-Pad14)") (class "Default")
      (node (ref "U19") (pin "14") (pinfunction "14_14") (pintype "unspecified"))
    )
    (net (code "355") (name "unconnected-(U19-Pad15)") (class "Default")
      (node (ref "U19") (pin "15") (pinfunction "15_15") (pintype "unspecified"))
    )
    (net (code "356") (name "unconnected-(U19-Pad16)") (class "Default")
      (node (ref "U19") (pin "16") (pinfunction "16_16") (pintype "unspecified"))
    )
    (net (code "357") (name "unconnected-(U19-Pad17)") (class "Default")
      (node (ref "U19") (pin "17") (pinfunction "17_17") (pintype "unspecified"))
    )
    (net (code "358") (name "unconnected-(U19-Pad18)") (class "Default")
      (node (ref "U19") (pin "18") (pinfunction "18_18") (pintype "unspecified"))
    )
    (net (code "359") (name "unconnected-(U19-Pad19)") (class "Default")
      (node (ref "U19") (pin "19") (pinfunction "19_19") (pintype "unspecified"))
    )
    (net (code "360") (name "unconnected-(U19-Pad20)") (class "Default")
      (node (ref "U19") (pin "20") (pinfunction "20_20") (pintype "unspecified"))
    )
    (net (code "361") (name "unconnected-(U19-Pad21)") (class "Default")
      (node (ref "U19") (pin "21") (pinfunction "21_21") (pintype "unspecified"))
    )
    (net (code "362") (name "unconnected-(U19-Pad22)") (class "Default")
      (node (ref "U19") (pin "22") (pinfunction "22_22") (pintype "unspecified"))
    )
    (net (code "363") (name "unconnected-(U19-Pad23)") (class "Default")
      (node (ref "U19") (pin "23") (pinfunction "23_23") (pintype "unspecified"))
    )
    (net (code "364") (name "unconnected-(U19-Pad24)") (class "Default")
      (node (ref "U19") (pin "24") (pinfunction "24_24") (pintype "unspecified"))
    )
    (net (code "365") (name "unconnected-(U19-Pad25)") (class "Default")
      (node (ref "U19") (pin "25") (pinfunction "25_25") (pintype "unspecified"))
    )
    (net (code "366") (name "unconnected-(U19-Pad26)") (class "Default")
      (node (ref "U19") (pin "26") (pinfunction "26_26") (pintype "unspecified"))
    )
    (net (code "367") (name "unconnected-(U19-Pad27)") (class "Default")
      (node (ref "U19") (pin "27") (pinfunction "27_27") (pintype "unspecified"))
    )
    (net (code "368") (name "unconnected-(U19-Pad28)") (class "Default")
      (node (ref "U19") (pin "28") (pinfunction "28_28") (pintype "unspecified"))
    )
    (net (code "369") (name "unconnected-(U19-Pad29)") (class "Default")
      (node (ref "U19") (pin "29") (pinfunction "29_29") (pintype "unspecified"))
    )
    (net (code "370") (name "unconnected-(U19-Pad30)") (class "Default")
      (node (ref "U19") (pin "30") (pinfunction "30_30") (pintype "unspecified"))
    )
    (net (code "371") (name "unconnected-(U19-Pad31)") (class "Default")
      (node (ref "U19") (pin "31") (pinfunction "31_31") (pintype "unspecified"))
    )
    (net (code "372") (name "unconnected-(U19-Pad32)") (class "Default")
      (node (ref "U19") (pin "32") (pinfunction "32_32") (pintype "unspecified"))
    )
    (net (code "373") (name "unconnected-(U19-Pad33)") (class "Default")
      (node (ref "U19") (pin "33") (pinfunction "33_33") (pintype "unspecified"))
    )
    (net (code "374") (name "unconnected-(U19-Pad34)") (class "Default")
      (node (ref "U19") (pin "34") (pinfunction "34_34") (pintype "unspecified"))
    )
    (net (code "375") (name "unconnected-(U19-Pad35)") (class "Default")
      (node (ref "U19") (pin "35") (pinfunction "35_35") (pintype "unspecified"))
    )
    (net (code "376") (name "unconnected-(U19-Pad36)") (class "Default")
      (node (ref "U19") (pin "36") (pinfunction "36_36") (pintype "unspecified"))
    )
    (net (code "377") (name "unconnected-(U19-Pad37)") (class "Default")
      (node (ref "U19") (pin "37") (pinfunction "37_37") (pintype "unspecified"))
    )
    (net (code "378") (name "unconnected-(U19-Pad38)") (class "Default")
      (node (ref "U19") (pin "38") (pinfunction "38_38") (pintype "unspecified"))
    )
    (net (code "379") (name "unconnected-(U19-Pad39)") (class "Default")
      (node (ref "U19") (pin "39") (pinfunction "39_39") (pintype "unspecified"))
    )
    (net (code "380") (name "unconnected-(U19-Pad40)") (class "Default")
      (node (ref "U19") (pin "40") (pinfunction "40_40") (pintype "unspecified"))
    )
    (net (code "381") (name "unconnected-(U19-Pad41)") (class "Default")
      (node (ref "U19") (pin "41") (pinfunction "41_41") (pintype "unspecified"))
    )
    (net (code "382") (name "unconnected-(U19-Pad42)") (class "Default")
      (node (ref "U19") (pin "42") (pinfunction "42_42") (pintype "unspecified"))
    )
    (net (code "383") (name "unconnected-(U19-Pad43)") (class "Default")
      (node (ref "U19") (pin "43") (pinfunction "43_43") (pintype "unspecified"))
    )
    (net (code "384") (name "unconnected-(U19-Pad44)") (class "Default")
      (node (ref "U19") (pin "44") (pinfunction "44_44") (pintype "unspecified"))
    )
    (net (code "385") (name "unconnected-(U19-Pad45)") (class "Default")
      (node (ref "U19") (pin "45") (pinfunction "45_45") (pintype "unspecified"))
    )
    (net (code "386") (name "unconnected-(U19-Pad46)") (class "Default")
      (node (ref "U19") (pin "46") (pinfunction "46_46") (pintype "unspecified"))
    )
    (net (code "387") (name "unconnected-(U19-Pad47)") (class "Default")
      (node (ref "U19") (pin "47") (pinfunction "47_47") (pintype "unspecified"))
    )
    (net (code "388") (name "unconnected-(U19-Pad48)") (class "Default")
      (node (ref "U19") (pin "48") (pinfunction "48_48") (pintype "unspecified"))
    )
    (net (code "389") (name "unconnected-(U19-Pad49)") (class "Default")
      (node (ref "U19") (pin "49") (pinfunction "49_49") (pintype "unspecified"))
    )
    (net (code "390") (name "unconnected-(U19-Pad50)") (class "Default")
      (node (ref "U19") (pin "50") (pinfunction "50_50") (pintype "unspecified"))
    )
    (net (code "391") (name "unconnected-(U19-Pad51)") (class "Default")
      (node (ref "U19") (pin "51") (pinfunction "51_51") (pintype "unspecified"))
    )
    (net (code "392") (name "unconnected-(U19-Pad52)") (class "Default")
      (node (ref "U19") (pin "52") (pinfunction "52_52") (pintype "unspecified"))
    )
    (net (code "393") (name "unconnected-(U19-Pad53)") (class "Default")
      (node (ref "U19") (pin "53") (pinfunction "53_53") (pintype "unspecified"))
    )
    (net (code "394") (name "unconnected-(U19-Pad54)") (class "Default")
      (node (ref "U19") (pin "54") (pinfunction "54_54") (pintype "unspecified"))
    )
    (net (code "395") (name "unconnected-(U19-Pad55)") (class "Default")
      (node (ref "U19") (pin "55") (pinfunction "55_55") (pintype "unspecified"))
    )
    (net (code "396") (name "unconnected-(U19-Pad56)") (class "Default")
      (node (ref "U19") (pin "56") (pinfunction "56_56") (pintype "unspecified"))
    )
    (net (code "397") (name "unconnected-(U19-Pad57)") (class "Default")
      (node (ref "U19") (pin "57") (pinfunction "57_57") (pintype "unspecified"))
    )
    (net (code "398") (name "unconnected-(U19-Pad58)") (class "Default")
      (node (ref "U19") (pin "58") (pinfunction "58_58") (pintype "unspecified"))
    )
    (net (code "399") (name "unconnected-(U19-Pad59)") (class "Default")
      (node (ref "U19") (pin "59") (pinfunction "59_59") (pintype "unspecified"))
    )
    (net (code "400") (name "unconnected-(U19-Pad60)") (class "Default")
      (node (ref "U19") (pin "60") (pinfunction "60_60") (pintype "unspecified"))
    )
    (net (code "401") (name "unconnected-(U19-Pad61)") (class "Default")
      (node (ref "U19") (pin "61") (pinfunction "61_61") (pintype "unspecified"))
    )
    (net (code "402") (name "unconnected-(U19-Pad62)") (class "Default")
      (node (ref "U19") (pin "62") (pinfunction "62_62") (pintype "unspecified"))
    )
    (net (code "403") (name "unconnected-(U19-Pad63)") (class "Default")
      (node (ref "U19") (pin "63") (pinfunction "63_63") (pintype "unspecified"))
    )
    (net (code "404") (name "unconnected-(U19-Pad64)") (class "Default")
      (node (ref "U19") (pin "64") (pinfunction "64_64") (pintype "unspecified"))
    )
    (net (code "405") (name "unconnected-(U19-Pad65)") (class "Default")
      (node (ref "U19") (pin "65") (pinfunction "65_65") (pintype "unspecified"))
    )
    (net (code "406") (name "unconnected-(U19-Pad66)") (class "Default")
      (node (ref "U19") (pin "66") (pinfunction "66_66") (pintype "unspecified"))
    )
    (net (code "407") (name "unconnected-(U19-Pad67)") (class "Default")
      (node (ref "U19") (pin "67") (pinfunction "67_67") (pintype "unspecified"))
    )
    (net (code "408") (name "unconnected-(U19-Pad68)") (class "Default")
      (node (ref "U19") (pin "68") (pinfunction "68_68") (pintype "unspecified"))
    )
    (net (code "409") (name "unconnected-(U19-Pad69)") (class "Default")
      (node (ref "U19") (pin "69") (pinfunction "69_69") (pintype "unspecified"))
    )
    (net (code "410") (name "unconnected-(U19-Pad70)") (class "Default")
      (node (ref "U19") (pin "70") (pinfunction "70_70") (pintype "unspecified"))
    )
    (net (code "411") (name "unconnected-(U19-Pad71)") (class "Default")
      (node (ref "U19") (pin "71") (pinfunction "71_71") (pintype "unspecified"))
    )
    (net (code "412") (name "unconnected-(U19-Pad72)") (class "Default")
      (node (ref "U19") (pin "72") (pinfunction "72_72") (pintype "unspecified"))
    )
    (net (code "413") (name "unconnected-(U19-Pad73)") (class "Default")
      (node (ref "U19") (pin "73") (pinfunction "73_73") (pintype "unspecified"))
    )
    (net (code "414") (name "unconnected-(U19-Pad74)") (class "Default")
      (node (ref "U19") (pin "74") (pinfunction "74_74") (pintype "unspecified"))
    )
    (net (code "415") (name "unconnected-(U19-Pad75)") (class "Default")
      (node (ref "U19") (pin "75") (pinfunction "75_75") (pintype "unspecified"))
    )
    (net (code "416") (name "unconnected-(U19-Pad76)") (class "Default")
      (node (ref "U19") (pin "76") (pinfunction "76_76") (pintype "unspecified"))
    )
    (net (code "417") (name "unconnected-(U19-Pad77)") (class "Default")
      (node (ref "U19") (pin "77") (pinfunction "77_77") (pintype "unspecified"))
    )
    (net (code "418") (name "unconnected-(U19-Pad78)") (class "Default")
      (node (ref "U19") (pin "78") (pinfunction "78_78") (pintype "unspecified"))
    )
    (net (code "419") (name "unconnected-(U19-Pad79)") (class "Default")
      (node (ref "U19") (pin "79") (pinfunction "79_79") (pintype "unspecified"))
    )
    (net (code "420") (name "unconnected-(U19-Pad80)") (class "Default")
      (node (ref "U19") (pin "80") (pinfunction "80_80") (pintype "unspecified"))
    )
    (net (code "421") (name "unconnected-(U19-Pad81)") (class "Default")
      (node (ref "U19") (pin "81") (pinfunction "81_81") (pintype "unspecified"))
    )
    (net (code "422") (name "unconnected-(U19-Pad82)") (class "Default")
      (node (ref "U19") (pin "82") (pinfunction "82_82") (pintype "unspecified"))
    )
    (net (code "423") (name "unconnected-(U19-Pad83)") (class "Default")
      (node (ref "U19") (pin "83") (pinfunction "83_83") (pintype "unspecified"))
    )
    (net (code "424") (name "unconnected-(U19-Pad84)") (class "Default")
      (node (ref "U19") (pin "84") (pinfunction "84_84") (pintype "unspecified"))
    )
    (net (code "425") (name "unconnected-(U19-Pad85)") (class "Default")
      (node (ref "U19") (pin "85") (pinfunction "85_85") (pintype "unspecified"))
    )
    (net (code "426") (name "unconnected-(U19-Pad86)") (class "Default")
      (node (ref "U19") (pin "86") (pinfunction "86_86") (pintype "unspecified"))
    )
    (net (code "427") (name "unconnected-(U19-Pad87)") (class "Default")
      (node (ref "U19") (pin "87") (pinfunction "87_87") (pintype "unspecified"))
    )
    (net (code "428") (name "unconnected-(U19-Pad88)") (class "Default")
      (node (ref "U19") (pin "88") (pinfunction "88_88") (pintype "unspecified"))
    )
    (net (code "429") (name "unconnected-(U19-Pad89)") (class "Default")
      (node (ref "U19") (pin "89") (pinfunction "89_89") (pintype "unspecified"))
    )
    (net (code "430") (name "unconnected-(U19-Pad90)") (class "Default")
      (node (ref "U19") (pin "90") (pinfunction "90_90") (pintype "unspecified"))
    )
    (net (code "431") (name "unconnected-(U19-Pad91)") (class "Default")
      (node (ref "U19") (pin "91") (pinfunction "91_91") (pintype "unspecified"))
    )
    (net (code "432") (name "unconnected-(U19-Pad92)") (class "Default")
      (node (ref "U19") (pin "92") (pinfunction "92_92") (pintype "unspecified"))
    )
    (net (code "433") (name "unconnected-(U19-Pad93)") (class "Default")
      (node (ref "U19") (pin "93") (pinfunction "93_93") (pintype "unspecified"))
    )
    (net (code "434") (name "unconnected-(U19-Pad94)") (class "Default")
      (node (ref "U19") (pin "94") (pinfunction "94_94") (pintype "unspecified"))
    )
    (net (code "435") (name "unconnected-(U19-Pad95)") (class "Default")
      (node (ref "U19") (pin "95") (pinfunction "95_95") (pintype "unspecified"))
    )
    (net (code "436") (name "unconnected-(U19-Pad96)") (class "Default")
      (node (ref "U19") (pin "96") (pinfunction "96_96") (pintype "unspecified"))
    )
    (net (code "437") (name "unconnected-(U19-Pad97)") (class "Default")
      (node (ref "U19") (pin "97") (pinfunction "97_97") (pintype "unspecified"))
    )
    (net (code "438") (name "unconnected-(U19-Pad98)") (class "Default")
      (node (ref "U19") (pin "98") (pinfunction "98_98") (pintype "unspecified"))
    )
    (net (code "439") (name "unconnected-(U19-Pad99)") (class "Default")
      (node (ref "U19") (pin "99") (pinfunction "99_99") (pintype "unspecified"))
    )
    (net (code "440") (name "unconnected-(U19-Pad100)") (class "Default")
      (node (ref "U19") (pin "100") (pinfunction "100_100") (pintype "unspecified"))
    )
    (net (code "441") (name "unconnected-(U19-Pad101)") (class "Default")
      (node (ref "U19") (pin "101") (pinfunction "101_101") (pintype "unspecified"))
    )
    (net (code "442") (name "unconnected-(U19-Pad102)") (class "Default")
      (node (ref "U19") (pin "102") (pinfunction "102_102") (pintype "unspecified"))
    )
    (net (code "443") (name "unconnected-(U19-Pad103)") (class "Default")
      (node (ref "U19") (pin "103") (pinfunction "103_103") (pintype "unspecified"))
    )
    (net (code "444") (name "unconnected-(U19-Pad104)") (class "Default")
      (node (ref "U19") (pin "104") (pinfunction "104_104") (pintype "unspecified"))
    )
    (net (code "445") (name "unconnected-(U19-Pad105)") (class "Default")
      (node (ref "U19") (pin "105") (pinfunction "105_105") (pintype "unspecified"))
    )
    (net (code "446") (name "unconnected-(U19-Pad106)") (class "Default")
      (node (ref "U19") (pin "106") (pinfunction "106_106") (pintype "unspecified"))
    )
    (net (code "447") (name "unconnected-(U19-Pad107)") (class "Default")
      (node (ref "U19") (pin "107") (pinfunction "107_107") (pintype "unspecified"))
    )
    (net (code "448") (name "unconnected-(U19-Pad108)") (class "Default")
      (node (ref "U19") (pin "108") (pinfunction "108_108") (pintype "unspecified"))
    )
    (net (code "449") (name "unconnected-(U19-Pad109)") (class "Default")
      (node (ref "U19") (pin "109") (pinfunction "109_109") (pintype "unspecified"))
    )
    (net (code "450") (name "unconnected-(U19-Pad110)") (class "Default")
      (node (ref "U19") (pin "110") (pinfunction "110_110") (pintype "unspecified"))
    )
    (net (code "451") (name "unconnected-(U19-Pad111)") (class "Default")
      (node (ref "U19") (pin "111") (pinfunction "111_111") (pintype "unspecified"))
    )
    (net (code "452") (name "unconnected-(U19-Pad112)") (class "Default")
      (node (ref "U19") (pin "112") (pinfunction "112_112") (pintype "unspecified"))
    )
    (net (code "453") (name "unconnected-(U19-Pad113)") (class "Default")
      (node (ref "U19") (pin "113") (pinfunction "113_113") (pintype "unspecified"))
    )
    (net (code "454") (name "unconnected-(U19-Pad114)") (class "Default")
      (node (ref "U19") (pin "114") (pinfunction "114_114") (pintype "unspecified"))
    )
    (net (code "455") (name "unconnected-(U19-Pad115)") (class "Default")
      (node (ref "U19") (pin "115") (pinfunction "115_115") (pintype "unspecified"))
    )
    (net (code "456") (name "unconnected-(U19-Pad116)") (class "Default")
      (node (ref "U19") (pin "116") (pinfunction "116_116") (pintype "unspecified"))
    )
    (net (code "457") (name "unconnected-(U19-Pad117)") (class "Default")
      (node (ref "U19") (pin "117") (pinfunction "117_117") (pintype "unspecified"))
    )
    (net (code "458") (name "unconnected-(U19-Pad118)") (class "Default")
      (node (ref "U19") (pin "118") (pinfunction "118_118") (pintype "unspecified"))
    )
    (net (code "459") (name "unconnected-(U19-Pad119)") (class "Default")
      (node (ref "U19") (pin "119") (pinfunction "119_119") (pintype "unspecified"))
    )
    (net (code "460") (name "unconnected-(U19-Pad120)") (class "Default")
      (node (ref "U19") (pin "120") (pinfunction "120_120") (pintype "unspecified"))
    )
    (net (code "461") (name "unconnected-(U19-Pad121)") (class "Default")
      (node (ref "U19") (pin "121") (pinfunction "121_121") (pintype "unspecified"))
    )
    (net (code "462") (name "unconnected-(U19-Pad122)") (class "Default")
      (node (ref "U19") (pin "122") (pinfunction "122_122") (pintype "unspecified"))
    )
    (net (code "463") (name "unconnected-(U19-Pad123)") (class "Default")
      (node (ref "U19") (pin "123") (pinfunction "123_123") (pintype "unspecified"))
    )
    (net (code "464") (name "unconnected-(U19-Pad124)") (class "Default")
      (node (ref "U19") (pin "124") (pinfunction "124_124") (pintype "unspecified"))
    )
    (net (code "465") (name "unconnected-(U19-Pad125)") (class "Default")
      (node (ref "U19") (pin "125") (pinfunction "125_125") (pintype "unspecified"))
    )
    (net (code "466") (name "unconnected-(U19-Pad126)") (class "Default")
      (node (ref "U19") (pin "126") (pinfunction "126_126") (pintype "unspecified"))
    )
    (net (code "467") (name "unconnected-(U19-Pad127)") (class "Default")
      (node (ref "U19") (pin "127") (pinfunction "127_127") (pintype "unspecified"))
    )
    (net (code "468") (name "unconnected-(U19-Pad128)") (class "Default")
      (node (ref "U19") (pin "128") (pinfunction "128_128") (pintype "unspecified"))
    )
    (net (code "469") (name "unconnected-(U19-Pad129)") (class "Default")
      (node (ref "U19") (pin "129") (pinfunction "129_129") (pintype "unspecified"))
    )
    (net (code "470") (name "unconnected-(U19-Pad130)") (class "Default")
      (node (ref "U19") (pin "130") (pinfunction "130_130") (pintype "unspecified"))
    )
    (net (code "471") (name "unconnected-(U19-Pad131)") (class "Default")
      (node (ref "U19") (pin "131") (pinfunction "131_131") (pintype "unspecified"))
    )
    (net (code "472") (name "unconnected-(U19-Pad132)") (class "Default")
      (node (ref "U19") (pin "132") (pinfunction "132_132") (pintype "unspecified"))
    )
    (net (code "473") (name "unconnected-(U19-Pad133)") (class "Default")
      (node (ref "U19") (pin "133") (pinfunction "133_133") (pintype "unspecified"))
    )
    (net (code "474") (name "unconnected-(U19-Pad134)") (class "Default")
      (node (ref "U19") (pin "134") (pinfunction "134_134") (pintype "unspecified"))
    )
    (net (code "475") (name "unconnected-(U19-Pad135)") (class "Default")
      (node (ref "U19") (pin "135") (pinfunction "135_135") (pintype "unspecified"))
    )
    (net (code "476") (name "unconnected-(U19-Pad136)") (class "Default")
      (node (ref "U19") (pin "136") (pinfunction "136_136") (pintype "unspecified"))
    )
    (net (code "477") (name "unconnected-(U19-Pad137)") (class "Default")
      (node (ref "U19") (pin "137") (pinfunction "137_137") (pintype "unspecified"))
    )
    (net (code "478") (name "unconnected-(U19-Pad138)") (class "Default")
      (node (ref "U19") (pin "138") (pinfunction "138_138") (pintype "unspecified"))
    )
    (net (code "479") (name "unconnected-(U19-Pad139)") (class "Default")
      (node (ref "U19") (pin "139") (pinfunction "139_139") (pintype "unspecified"))
    )
    (net (code "480") (name "unconnected-(U19-Pad140)") (class "Default")
      (node (ref "U19") (pin "140") (pinfunction "140_140") (pintype "unspecified"))
    )
    (net (code "481") (name "unconnected-(U19-Pad141)") (class "Default")
      (node (ref "U19") (pin "141") (pinfunction "141_141") (pintype "unspecified"))
    )
    (net (code "482") (name "unconnected-(U19-Pad142)") (class "Default")
      (node (ref "U19") (pin "142") (pinfunction "142_142") (pintype "unspecified"))
    )
    (net (code "483") (name "unconnected-(U19-Pad143)") (class "Default")
      (node (ref "U19") (pin "143") (pinfunction "143_143") (pintype "unspecified"))
    )
    (net (code "484") (name "unconnected-(U19-Pad144)") (class "Default")
      (node (ref "U19") (pin "144") (pinfunction "144_144") (pintype "unspecified"))
    )
    (net (code "485") (name "unconnected-(U19-Pad145)") (class "Default")
      (node (ref "U19") (pin "145") (pinfunction "145_145") (pintype "unspecified"))
    )
    (net (code "486") (name "unconnected-(U19-Pad146)") (class "Default")
      (node (ref "U19") (pin "146") (pinfunction "146_146") (pintype "unspecified"))
    )
    (net (code "487") (name "unconnected-(U19-Pad147)") (class "Default")
      (node (ref "U19") (pin "147") (pinfunction "147_147") (pintype "unspecified"))
    )
    (net (code "488") (name "unconnected-(U19-Pad148)") (class "Default")
      (node (ref "U19") (pin "148") (pinfunction "148_148") (pintype "unspecified"))
    )
    (net (code "489") (name "unconnected-(U19-Pad149)") (class "Default")
      (node (ref "U19") (pin "149") (pinfunction "149_149") (pintype "unspecified"))
    )
    (net (code "490") (name "unconnected-(U19-Pad150)") (class "Default")
      (node (ref "U19") (pin "150") (pinfunction "150_150") (pintype "unspecified"))
    )
    (net (code "491") (name "unconnected-(U19-Pad151)") (class "Default")
      (node (ref "U19") (pin "151") (pinfunction "151_151") (pintype "unspecified"))
    )
    (net (code "492") (name "unconnected-(U19-Pad152)") (class "Default")
      (node (ref "U19") (pin "152") (pinfunction "152_152") (pintype "unspecified"))
    )
    (net (code "493") (name "unconnected-(U19-Pad153)") (class "Default")
      (node (ref "U19") (pin "153") (pinfunction "153_153") (pintype "unspecified"))
    )
    (net (code "494") (name "unconnected-(U19-Pad154)") (class "Default")
      (node (ref "U19") (pin "154") (pinfunction "154_154") (pintype "unspecified"))
    )
    (net (code "495") (name "unconnected-(U19-Pad155)") (class "Default")
      (node (ref "U19") (pin "155") (pinfunction "155_155") (pintype "unspecified"))
    )
    (net (code "496") (name "unconnected-(U19-Pad156)") (class "Default")
      (node (ref "U19") (pin "156") (pinfunction "156_156") (pintype "unspecified"))
    )
    (net (code "497") (name "unconnected-(U19-Pad157)") (class "Default")
      (node (ref "U19") (pin "157") (pinfunction "157_157") (pintype "unspecified"))
    )
    (net (code "498") (name "unconnected-(U19-Pad158)") (class "Default")
      (node (ref "U19") (pin "158") (pinfunction "158_158") (pintype "unspecified"))
    )
    (net (code "499") (name "unconnected-(U19-Pad159)") (class "Default")
      (node (ref "U19") (pin "159") (pinfunction "159_159") (pintype "unspecified"))
    )
    (net (code "500") (name "unconnected-(U19-Pad160)") (class "Default")
      (node (ref "U19") (pin "160") (pinfunction "160_160") (pintype "unspecified"))
    )
    (net (code "501") (name "unconnected-(U19-Pad161)") (class "Default")
      (node (ref "U19") (pin "161") (pinfunction "161_161") (pintype "unspecified"))
    )
    (net (code "502") (name "unconnected-(U19-Pad162)") (class "Default")
      (node (ref "U19") (pin "162") (pinfunction "162_162") (pintype "unspecified"))
    )
    (net (code "503") (name "unconnected-(U19-Pad163)") (class "Default")
      (node (ref "U19") (pin "163") (pinfunction "163_163") (pintype "unspecified"))
    )
    (net (code "504") (name "unconnected-(U19-Pad164)") (class "Default")
      (node (ref "U19") (pin "164") (pinfunction "164_164") (pintype "unspecified"))
    )
    (net (code "505") (name "unconnected-(U19-Pad165)") (class "Default")
      (node (ref "U19") (pin "165") (pinfunction "165_165") (pintype "unspecified"))
    )
    (net (code "506") (name "unconnected-(U19-Pad166)") (class "Default")
      (node (ref "U19") (pin "166") (pinfunction "166_166") (pintype "unspecified"))
    )
    (net (code "507") (name "unconnected-(U19-Pad167)") (class "Default")
      (node (ref "U19") (pin "167") (pinfunction "167_167") (pintype "unspecified"))
    )
    (net (code "508") (name "unconnected-(U19-Pad168)") (class "Default")
      (node (ref "U19") (pin "168") (pinfunction "168_168") (pintype "unspecified"))
    )
    (net (code "509") (name "unconnected-(U19-Pad169)") (class "Default")
      (node (ref "U19") (pin "169") (pinfunction "169_169") (pintype "unspecified"))
    )
    (net (code "510") (name "unconnected-(U19-Pad170)") (class "Default")
      (node (ref "U19") (pin "170") (pinfunction "170_170") (pintype "unspecified"))
    )
    (net (code "511") (name "unconnected-(U19-Pad171)") (class "Default")
      (node (ref "U19") (pin "171") (pinfunction "171_171") (pintype "unspecified"))
    )
    (net (code "512") (name "unconnected-(U19-Pad172)") (class "Default")
      (node (ref "U19") (pin "172") (pinfunction "172_172") (pintype "unspecified"))
    )
    (net (code "513") (name "unconnected-(U19-Pad173)") (class "Default")
      (node (ref "U19") (pin "173") (pinfunction "173_173") (pintype "unspecified"))
    )
    (net (code "514") (name "unconnected-(U19-Pad174)") (class "Default")
      (node (ref "U19") (pin "174") (pinfunction "174_174") (pintype "unspecified"))
    )
    (net (code "515") (name "unconnected-(U19-Pad175)") (class "Default")
      (node (ref "U19") (pin "175") (pinfunction "175_175") (pintype "unspecified"))
    )
    (net (code "516") (name "unconnected-(U19-Pad176)") (class "Default")
      (node (ref "U19") (pin "176") (pinfunction "176_176") (pintype "unspecified"))
    )
    (net (code "517") (name "unconnected-(U19-Pad177)") (class "Default")
      (node (ref "U19") (pin "177") (pinfunction "177_177") (pintype "unspecified"))
    )
    (net (code "518") (name "unconnected-(U19-Pad178)") (class "Default")
      (node (ref "U19") (pin "178") (pinfunction "178_178") (pintype "unspecified"))
    )
    (net (code "519") (name "unconnected-(U19-Pad179)") (class "Default")
      (node (ref "U19") (pin "179") (pinfunction "179_179") (pintype "unspecified"))
    )
    (net (code "520") (name "unconnected-(U19-Pad180)") (class "Default")
      (node (ref "U19") (pin "180") (pinfunction "180_180") (pintype "unspecified"))
    )
    (net (code "521") (name "unconnected-(U19-Pad181)") (class "Default")
      (node (ref "U19") (pin "181") (pinfunction "181_181") (pintype "unspecified"))
    )
    (net (code "522") (name "unconnected-(U19-Pad182)") (class "Default")
      (node (ref "U19") (pin "182") (pinfunction "182_182") (pintype "unspecified"))
    )
    (net (code "523") (name "unconnected-(U19-Pad183)") (class "Default")
      (node (ref "U19") (pin "183") (pinfunction "183_183") (pintype "unspecified"))
    )
    (net (code "524") (name "unconnected-(U19-Pad184)") (class "Default")
      (node (ref "U19") (pin "184") (pinfunction "184_184") (pintype "unspecified"))
    )
    (net (code "525") (name "unconnected-(U19-Pad185)") (class "Default")
      (node (ref "U19") (pin "185") (pinfunction "185_185") (pintype "unspecified"))
    )
    (net (code "526") (name "unconnected-(U19-Pad186)") (class "Default")
      (node (ref "U19") (pin "186") (pinfunction "186_186") (pintype "unspecified"))
    )
    (net (code "527") (name "unconnected-(U19-Pad187)") (class "Default")
      (node (ref "U19") (pin "187") (pinfunction "187_187") (pintype "unspecified"))
    )
    (net (code "528") (name "unconnected-(U19-Pad188)") (class "Default")
      (node (ref "U19") (pin "188") (pinfunction "188_188") (pintype "unspecified"))
    )
    (net (code "529") (name "unconnected-(U19-Pad189)") (class "Default")
      (node (ref "U19") (pin "189") (pinfunction "189_189") (pintype "unspecified"))
    )
    (net (code "530") (name "unconnected-(U19-Pad190)") (class "Default")
      (node (ref "U19") (pin "190") (pinfunction "190_190") (pintype "unspecified"))
    )
    (net (code "531") (name "unconnected-(U19-Pad191)") (class "Default")
      (node (ref "U19") (pin "191") (pinfunction "191_191") (pintype "unspecified"))
    )
    (net (code "532") (name "unconnected-(U19-Pad192)") (class "Default")
      (node (ref "U19") (pin "192") (pinfunction "192_192") (pintype "unspecified"))
    )
    (net (code "533") (name "unconnected-(U19-Pad193)") (class "Default")
      (node (ref "U19") (pin "193") (pinfunction "193_193") (pintype "unspecified"))
    )
    (net (code "534") (name "unconnected-(U19-Pad194)") (class "Default")
      (node (ref "U19") (pin "194") (pinfunction "194_194") (pintype "unspecified"))
    )
    (net (code "535") (name "unconnected-(U19-Pad195)") (class "Default")
      (node (ref "U19") (pin "195") (pinfunction "195_195") (pintype "unspecified"))
    )
    (net (code "536") (name "unconnected-(U19-Pad196)") (class "Default")
      (node (ref "U19") (pin "196") (pinfunction "196_196") (pintype "unspecified"))
    )
    (net (code "537") (name "unconnected-(U19-Pad197)") (class "Default")
      (node (ref "U19") (pin "197") (pinfunction "197_197") (pintype "unspecified"))
    )
    (net (code "538") (name "unconnected-(U19-Pad198)") (class "Default")
      (node (ref "U19") (pin "198") (pinfunction "198_198") (pintype "unspecified"))
    )
    (net (code "539") (name "unconnected-(U19-Pad199)") (class "Default")
      (node (ref "U19") (pin "199") (pinfunction "199_199") (pintype "unspecified"))
    )
    (net (code "540") (name "unconnected-(U19-Pad200)") (class "Default")
      (node (ref "U19") (pin "200") (pinfunction "200_200") (pintype "unspecified"))
    )
    (net (code "541") (name "unconnected-(U19-Pad201)") (class "Default")
      (node (ref "U19") (pin "201") (pinfunction "201_201") (pintype "unspecified"))
    )
    (net (code "542") (name "unconnected-(U19-Pad202)") (class "Default")
      (node (ref "U19") (pin "202") (pinfunction "202_202") (pintype "unspecified"))
    )
    (net (code "543") (name "unconnected-(U19-Pad203)") (class "Default")
      (node (ref "U19") (pin "203") (pinfunction "203_203") (pintype "unspecified"))
    )
    (net (code "544") (name "unconnected-(U19-Pad204)") (class "Default")
      (node (ref "U19") (pin "204") (pinfunction "204_204") (pintype "unspecified"))
    )
    (net (code "545") (name "unconnected-(U19-Pad205)") (class "Default")
      (node (ref "U19") (pin "205") (pinfunction "205_205") (pintype "unspecified"))
    )
    (net (code "546") (name "unconnected-(U19-Pad206)") (class "Default")
      (node (ref "U19") (pin "206") (pinfunction "206_206") (pintype "unspecified"))
    )
    (net (code "547") (name "unconnected-(U19-Pad207)") (class "Default")
      (node (ref "U19") (pin "207") (pinfunction "207_207") (pintype "unspecified"))
    )
    (net (code "548") (name "unconnected-(U19-Pad208)") (class "Default")
      (node (ref "U19") (pin "208") (pinfunction "208_208") (pintype "unspecified"))
    )
    (net (code "549") (name "unconnected-(U19-Pad209)") (class "Default")
      (node (ref "U19") (pin "209") (pinfunction "209_209") (pintype "unspecified"))
    )
    (net (code "550") (name "unconnected-(U19-Pad210)") (class "Default")
      (node (ref "U19") (pin "210") (pinfunction "210_210") (pintype "unspecified"))
    )
    (net (code "551") (name "unconnected-(U19-Pad211)") (class "Default")
      (node (ref "U19") (pin "211") (pinfunction "211_211") (pintype "unspecified"))
    )
    (net (code "552") (name "unconnected-(U19-Pad212)") (class "Default")
      (node (ref "U19") (pin "212") (pinfunction "212_212") (pintype "unspecified"))
    )
    (net (code "553") (name "unconnected-(U19-Pad213)") (class "Default")
      (node (ref "U19") (pin "213") (pinfunction "213_213") (pintype "unspecified"))
    )
    (net (code "554") (name "unconnected-(U19-Pad214)") (class "Default")
      (node (ref "U19") (pin "214") (pinfunction "214_214") (pintype "unspecified"))
    )
    (net (code "555") (name "unconnected-(U19-Pad215)") (class "Default")
      (node (ref "U19") (pin "215") (pinfunction "215_215") (pintype "unspecified"))
    )
    (net (code "556") (name "unconnected-(U19-Pad216)") (class "Default")
      (node (ref "U19") (pin "216") (pinfunction "216_216") (pintype "unspecified"))
    )
    (net (code "557") (name "unconnected-(U19-Pad217)") (class "Default")
      (node (ref "U19") (pin "217") (pinfunction "217_217") (pintype "unspecified"))
    )
    (net (code "558") (name "unconnected-(U19-Pad218)") (class "Default")
      (node (ref "U19") (pin "218") (pinfunction "218_218") (pintype "unspecified"))
    )
    (net (code "559") (name "unconnected-(U19-Pad219)") (class "Default")
      (node (ref "U19") (pin "219") (pinfunction "219_219") (pintype "unspecified"))
    )
    (net (code "560") (name "unconnected-(U19-Pad220)") (class "Default")
      (node (ref "U19") (pin "220") (pinfunction "220_220") (pintype "unspecified"))
    )
    (net (code "561") (name "unconnected-(U19-Pad221)") (class "Default")
      (node (ref "U19") (pin "221") (pinfunction "221_221") (pintype "unspecified"))
    )
    (net (code "562") (name "unconnected-(U19-Pad222)") (class "Default")
      (node (ref "U19") (pin "222") (pinfunction "222_222") (pintype "unspecified"))
    )
    (net (code "563") (name "unconnected-(U19-Pad223)") (class "Default")
      (node (ref "U19") (pin "223") (pinfunction "223_223") (pintype "unspecified"))
    )
    (net (code "564") (name "unconnected-(U19-Pad224)") (class "Default")
      (node (ref "U19") (pin "224") (pinfunction "224_224") (pintype "unspecified"))
    )
    (net (code "565") (name "unconnected-(U19-Pad225)") (class "Default")
      (node (ref "U19") (pin "225") (pinfunction "225_225") (pintype "unspecified"))
    )
    (net (code "566") (name "unconnected-(U19-Pad226)") (class "Default")
      (node (ref "U19") (pin "226") (pinfunction "226_226") (pintype "unspecified"))
    )
    (net (code "567") (name "unconnected-(U19-Pad227)") (class "Default")
      (node (ref "U19") (pin "227") (pinfunction "227_227") (pintype "unspecified"))
    )
    (net (code "568") (name "unconnected-(U19-Pad228)") (class "Default")
      (node (ref "U19") (pin "228") (pinfunction "228_228") (pintype "unspecified"))
    )
    (net (code "569") (name "unconnected-(U19-Pad229)") (class "Default")
      (node (ref "U19") (pin "229") (pinfunction "229_229") (pintype "unspecified"))
    )
    (net (code "570") (name "unconnected-(U19-Pad230)") (class "Default")
      (node (ref "U19") (pin "230") (pinfunction "230_230") (pintype "unspecified"))
    )
    (net (code "571") (name "unconnected-(U19-Pad231)") (class "Default")
      (node (ref "U19") (pin "231") (pinfunction "231_231") (pintype "unspecified"))
    )
    (net (code "572") (name "unconnected-(U19-Pad232)") (class "Default")
      (node (ref "U19") (pin "232") (pinfunction "232_232") (pintype "unspecified"))
    )
    (net (code "573") (name "unconnected-(U19-Pad233)") (class "Default")
      (node (ref "U19") (pin "233") (pinfunction "233_233") (pintype "unspecified"))
    )
    (net (code "574") (name "unconnected-(U19-Pad234)") (class "Default")
      (node (ref "U19") (pin "234") (pinfunction "234_234") (pintype "unspecified"))
    )
    (net (code "575") (name "unconnected-(U19-Pad235)") (class "Default")
      (node (ref "U19") (pin "235") (pinfunction "235_235") (pintype "unspecified"))
    )
    (net (code "576") (name "unconnected-(U19-Pad236)") (class "Default")
      (node (ref "U19") (pin "236") (pinfunction "236_236") (pintype "unspecified"))
    )
    (net (code "577") (name "unconnected-(U19-Pad237)") (class "Default")
      (node (ref "U19") (pin "237") (pinfunction "237_237") (pintype "unspecified"))
    )
    (net (code "578") (name "unconnected-(U19-Pad238)") (class "Default")
      (node (ref "U19") (pin "238") (pinfunction "238_238") (pintype "unspecified"))
    )
    (net (code "579") (name "unconnected-(U19-Pad239)") (class "Default")
      (node (ref "U19") (pin "239") (pinfunction "239_239") (pintype "unspecified"))
    )
    (net (code "580") (name "unconnected-(U19-Pad240)") (class "Default")
      (node (ref "U19") (pin "240") (pinfunction "240_240") (pintype "unspecified"))
    )
    (net (code "581") (name "unconnected-(U19-Pad241)") (class "Default")
      (node (ref "U19") (pin "241") (pinfunction "241_241") (pintype "unspecified"))
    )
    (net (code "582") (name "unconnected-(U19-Pad242)") (class "Default")
      (node (ref "U19") (pin "242") (pinfunction "242_242") (pintype "unspecified"))
    )
    (net (code "583") (name "unconnected-(U19-Pad243)") (class "Default")
      (node (ref "U19") (pin "243") (pinfunction "243_243") (pintype "unspecified"))
    )
    (net (code "584") (name "unconnected-(U19-Pad244)") (class "Default")
      (node (ref "U19") (pin "244") (pinfunction "244_244") (pintype "unspecified"))
    )
    (net (code "585") (name "unconnected-(U19-Pad245)") (class "Default")
      (node (ref "U19") (pin "245") (pinfunction "245_245") (pintype "unspecified"))
    )
    (net (code "586") (name "unconnected-(U19-Pad246)") (class "Default")
      (node (ref "U19") (pin "246") (pinfunction "246_246") (pintype "unspecified"))
    )
    (net (code "587") (name "unconnected-(U19-Pad247)") (class "Default")
      (node (ref "U19") (pin "247") (pinfunction "247_247") (pintype "unspecified"))
    )
    (net (code "588") (name "unconnected-(U19-Pad248)") (class "Default")
      (node (ref "U19") (pin "248") (pinfunction "248_248") (pintype "unspecified"))
    )
    (net (code "589") (name "unconnected-(U19-Pad249)") (class "Default")
      (node (ref "U19") (pin "249") (pinfunction "249_249") (pintype "unspecified"))
    )
    (net (code "590") (name "unconnected-(U19-Pad250)") (class "Default")
      (node (ref "U19") (pin "250") (pinfunction "250_250") (pintype "unspecified"))
    )
    (net (code "591") (name "unconnected-(U19-Pad251)") (class "Default")
      (node (ref "U19") (pin "251") (pinfunction "251_251") (pintype "unspecified"))
    )
    (net (code "592") (name "unconnected-(U19-Pad252)") (class "Default")
      (node (ref "U19") (pin "252") (pinfunction "252_252") (pintype "unspecified"))
    )
    (net (code "593") (name "unconnected-(U19-Pad253)") (class "Default")
      (node (ref "U19") (pin "253") (pinfunction "253_253") (pintype "unspecified"))
    )
    (net (code "594") (name "unconnected-(U19-Pad254)") (class "Default")
      (node (ref "U19") (pin "254") (pinfunction "254_254") (pintype "unspecified"))
    )
    (net (code "595") (name "unconnected-(U19-Pad255)") (class "Default")
      (node (ref "U19") (pin "255") (pinfunction "255_255") (pintype "unspecified"))
    )
    (net (code "596") (name "unconnected-(U19-Pad256)") (class "Default")
      (node (ref "U19") (pin "256") (pinfunction "256_256") (pintype "unspecified"))
    )
    (net (code "597") (name "unconnected-(U19-Pad257)") (class "Default")
      (node (ref "U19") (pin "257") (pinfunction "257_257") (pintype "unspecified"))
    )
    (net (code "598") (name "unconnected-(U19-Pad258)") (class "Default")
      (node (ref "U19") (pin "258") (pinfunction "258_258") (pintype "unspecified"))
    )
    (net (code "599") (name "unconnected-(U19-Pad259)") (class "Default")
      (node (ref "U19") (pin "259") (pinfunction "259_259") (pintype "unspecified"))
    )
    (net (code "600") (name "unconnected-(U19-Pad260)") (class "Default")
      (node (ref "U19") (pin "260") (pinfunction "260_260") (pintype "unspecified"))
    )
    (net (code "601") (name "unconnected-(USB3-Reserved_(N.C.)-Pad14)") (class "Default")
      (node (ref "USB3") (pin "14") (pinfunction "Reserved_(N.C.)_14") (pintype "unspecified+no_connect"))
    )
  )
)
